# rt1060.net
KiCad netlist of a schematic drawn in EAGLE
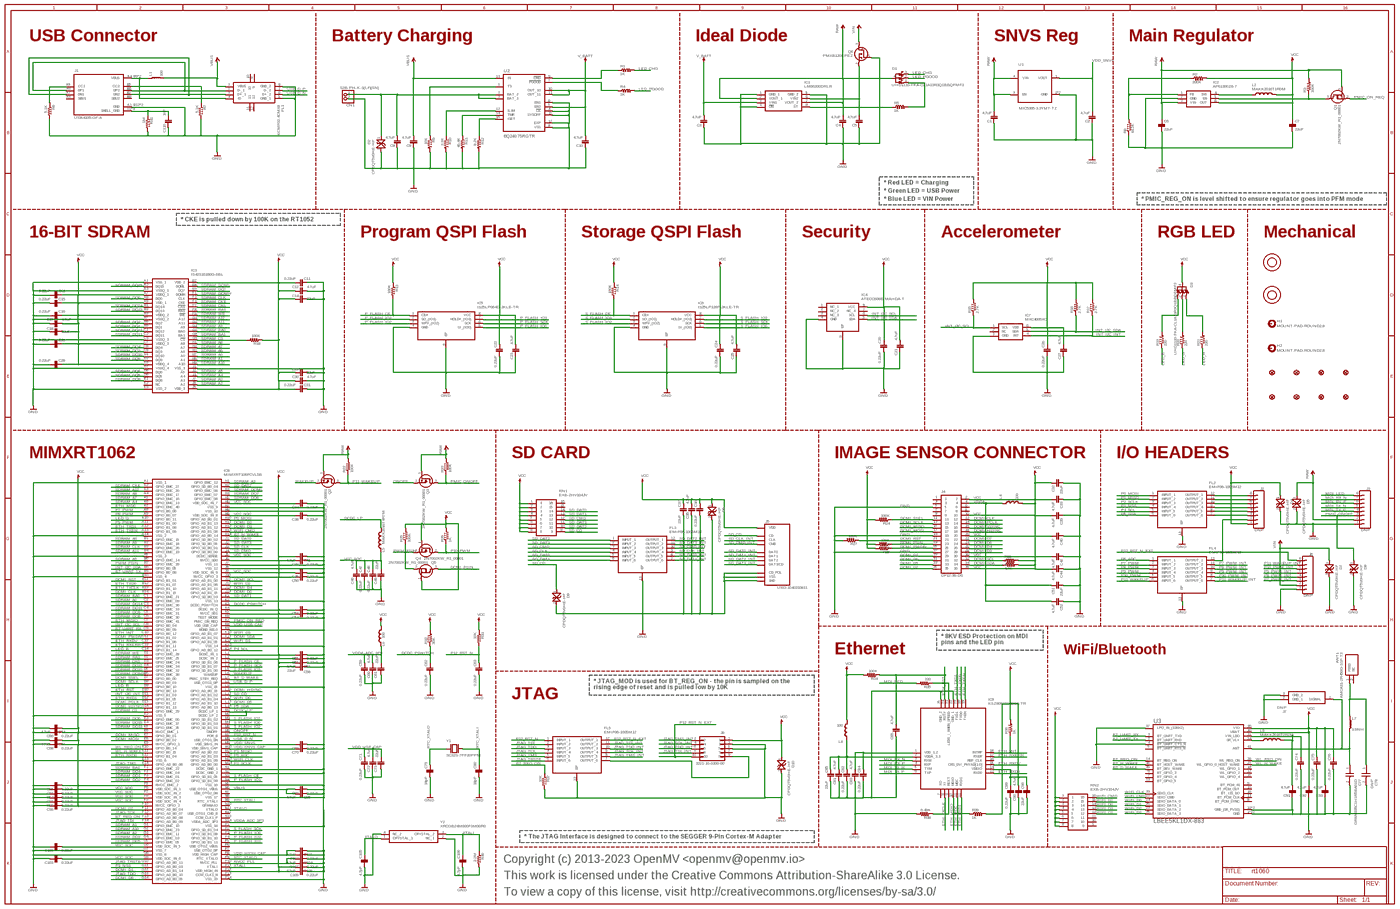
[diagram p0: schematic, sheet 1, overview]
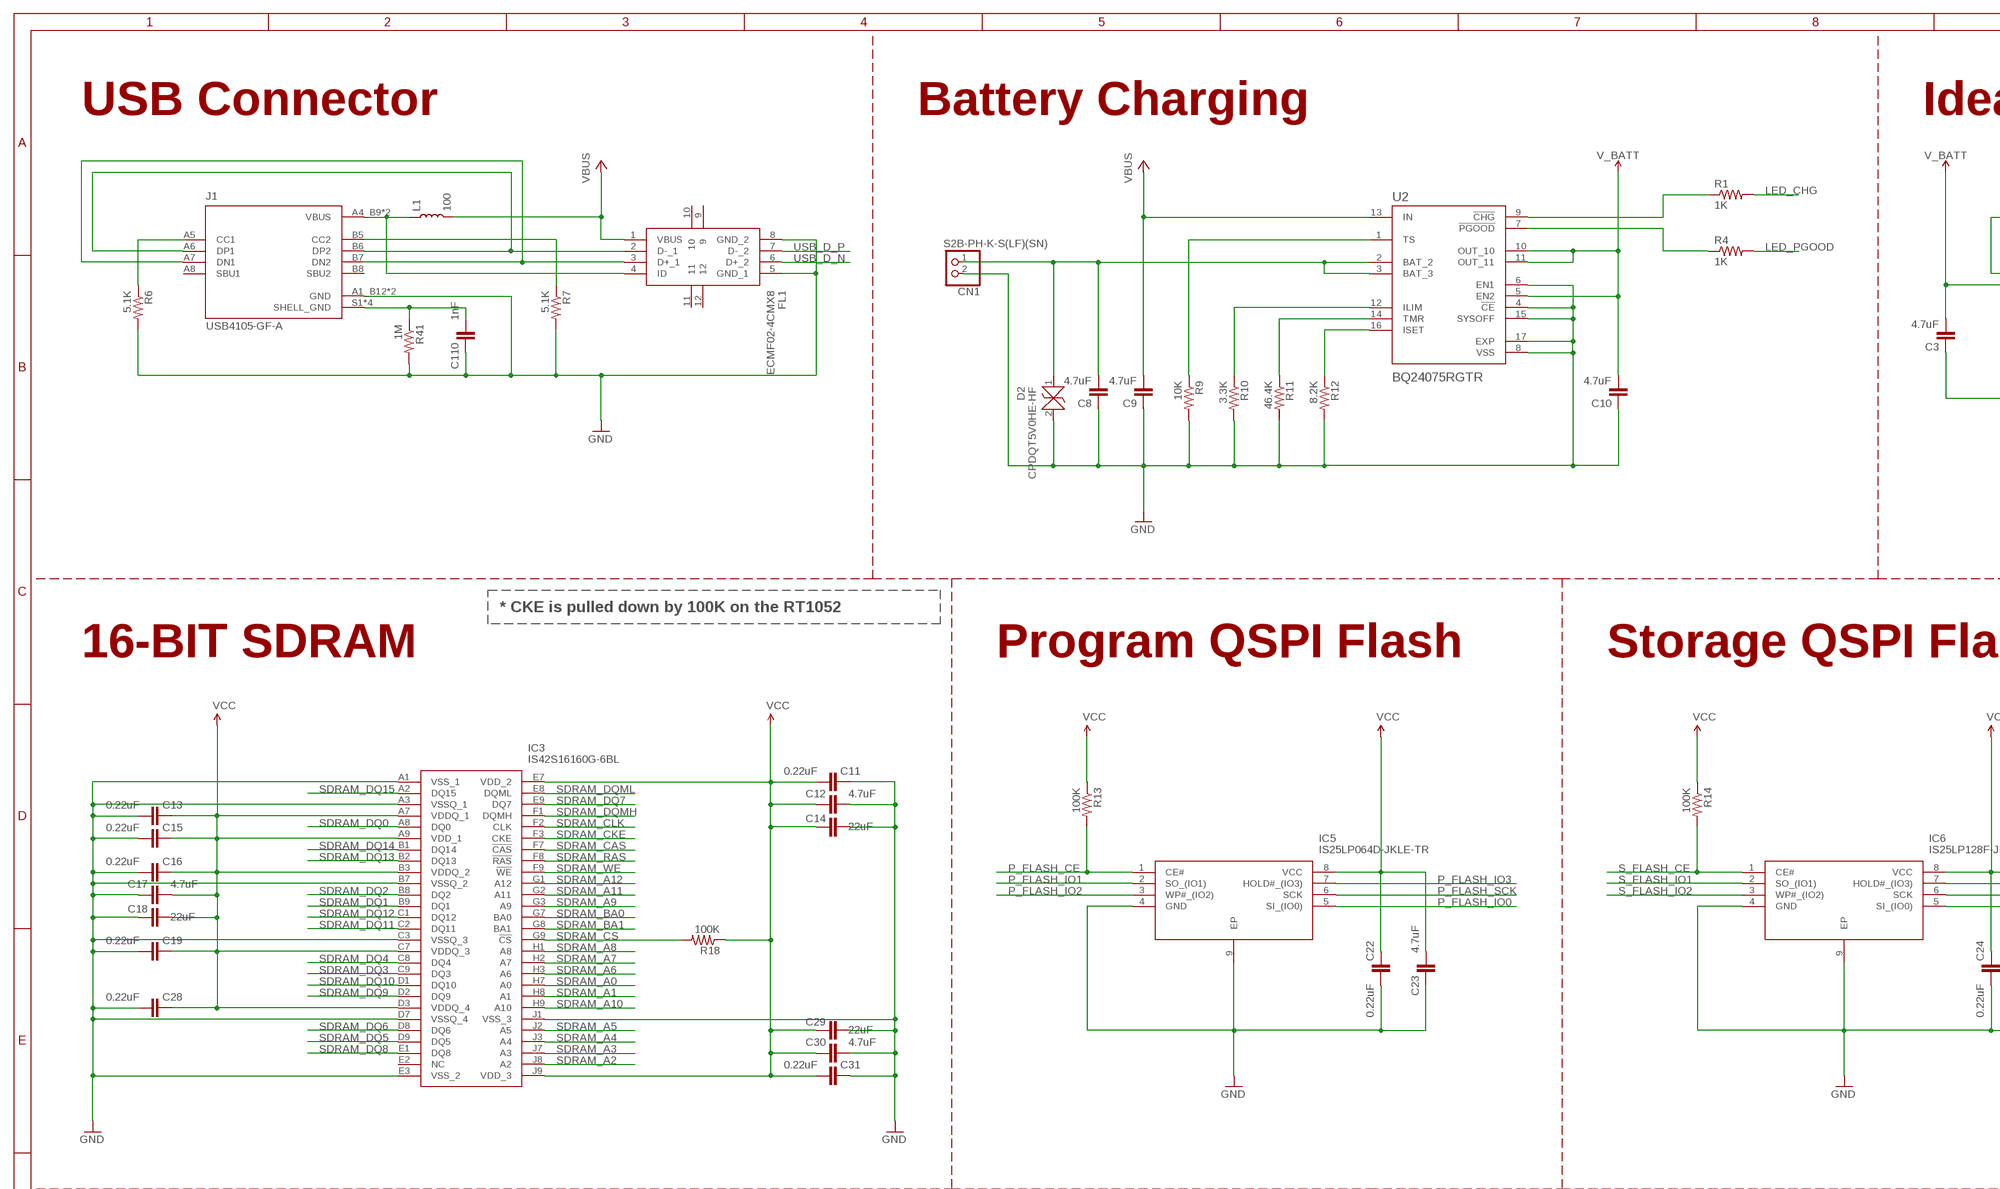
[diagram p1: schematic, sheet 1, part 1 of 4]
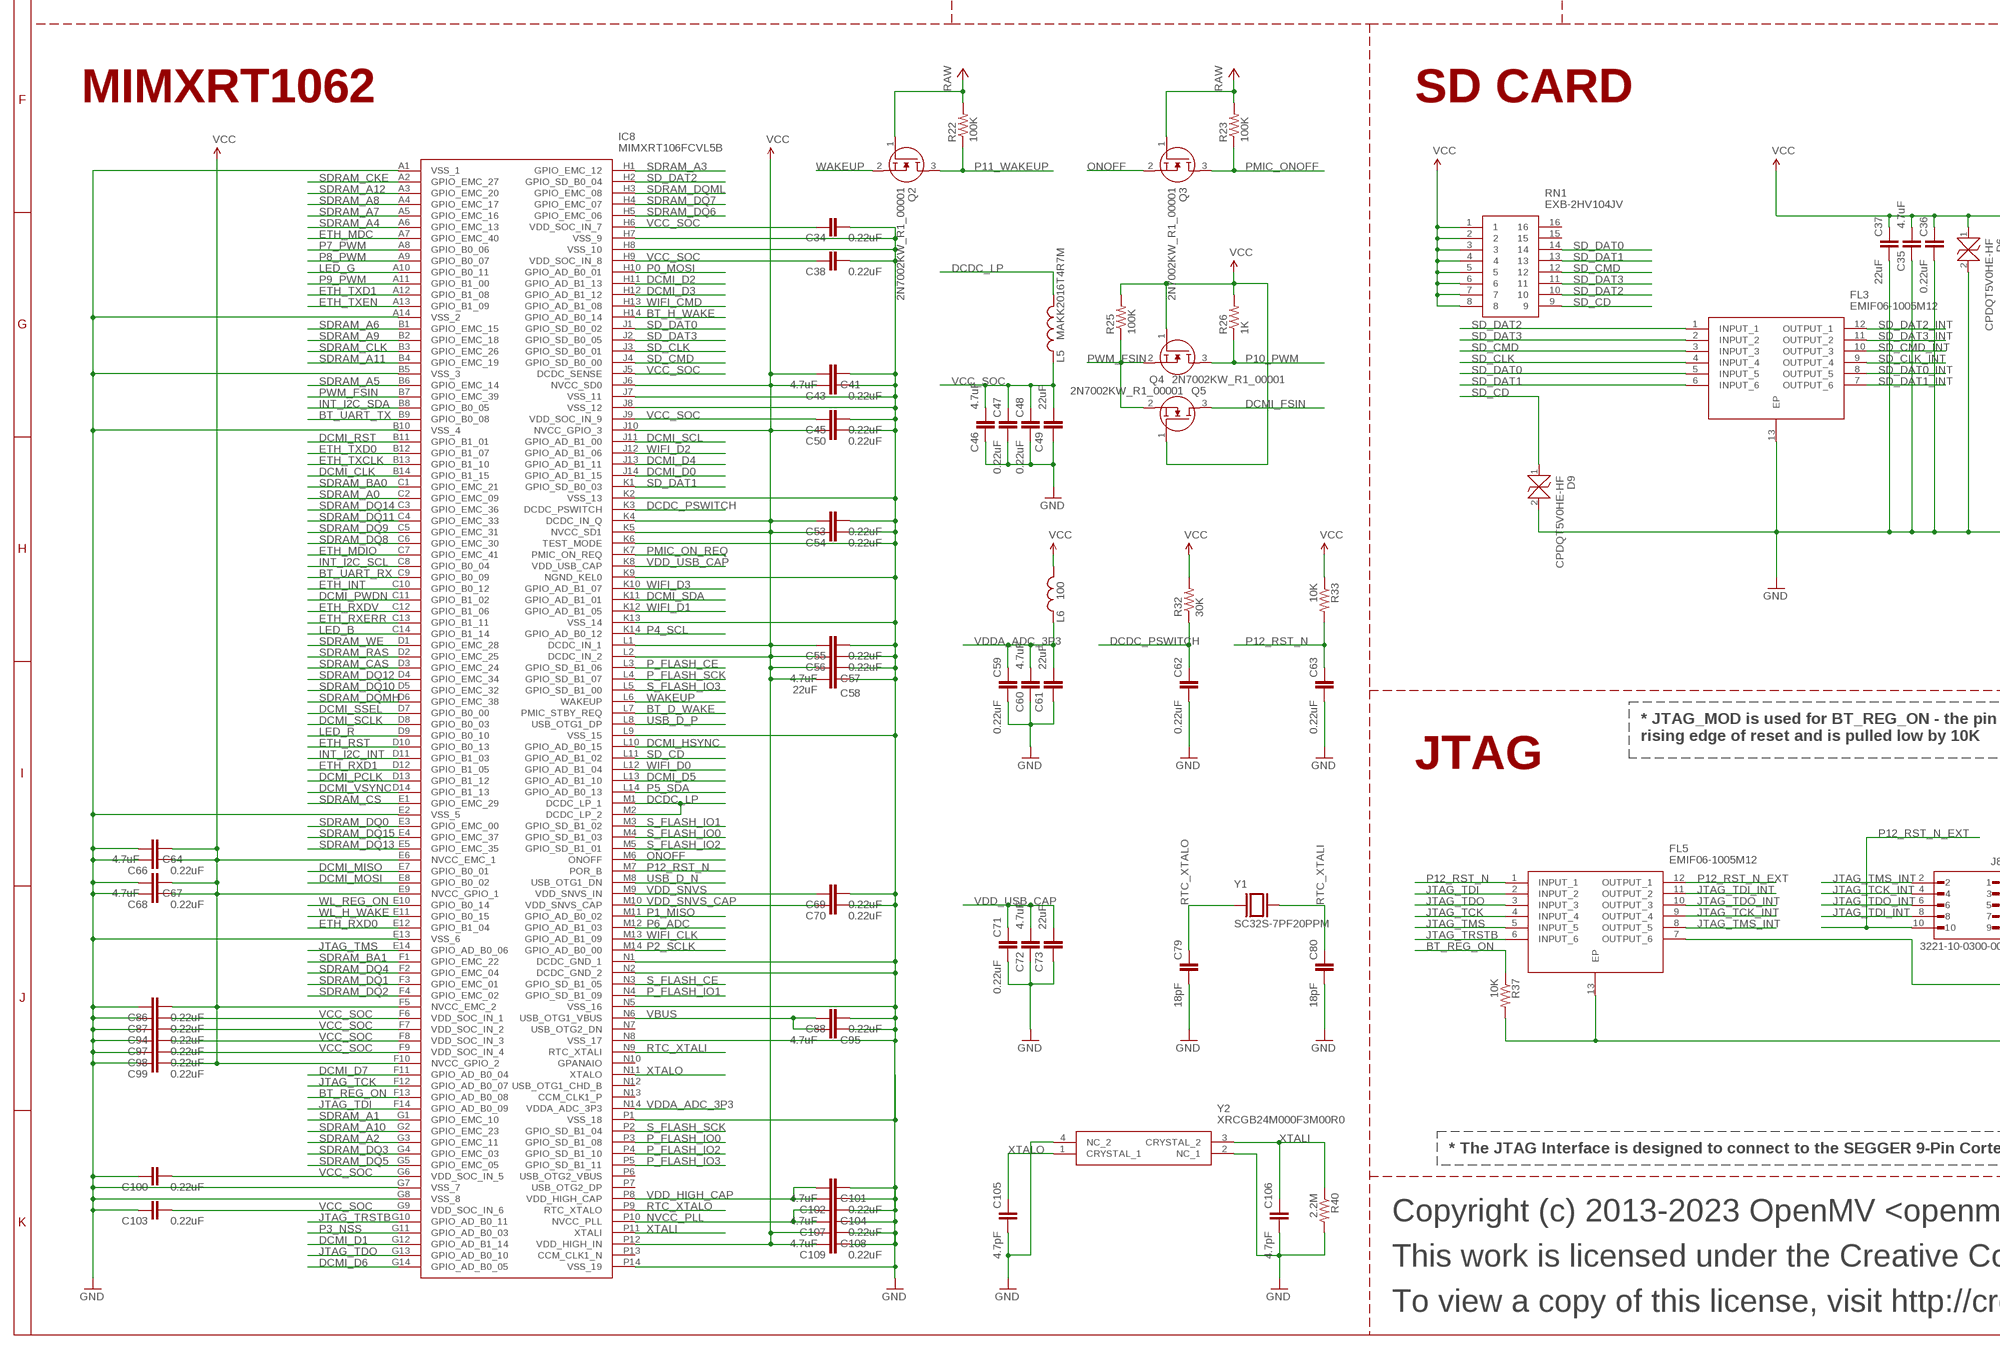
[diagram p2: schematic, sheet 1, part 2 of 4]
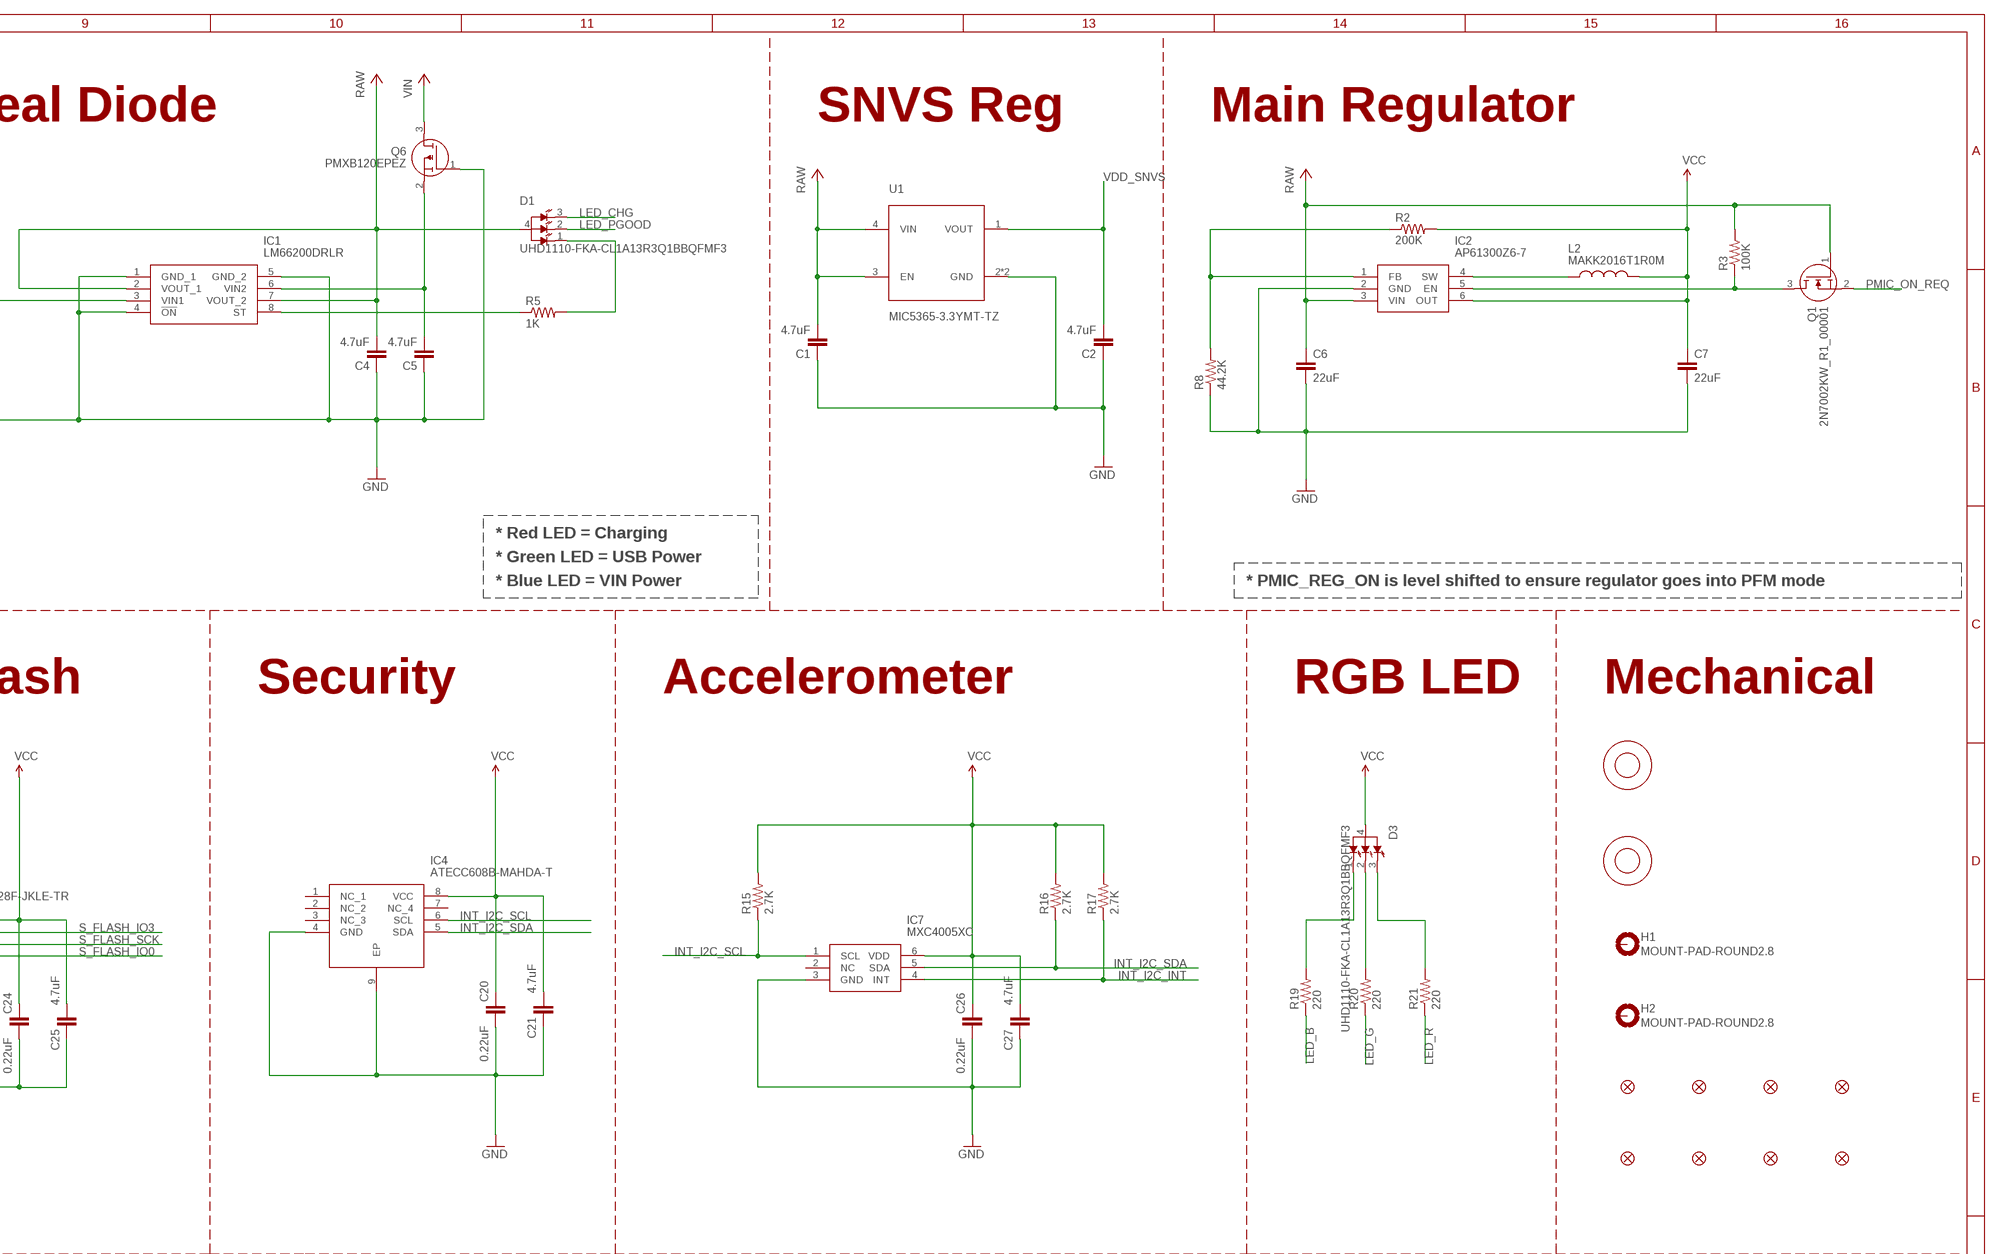
[diagram p3: schematic, sheet 1, part 3 of 4]
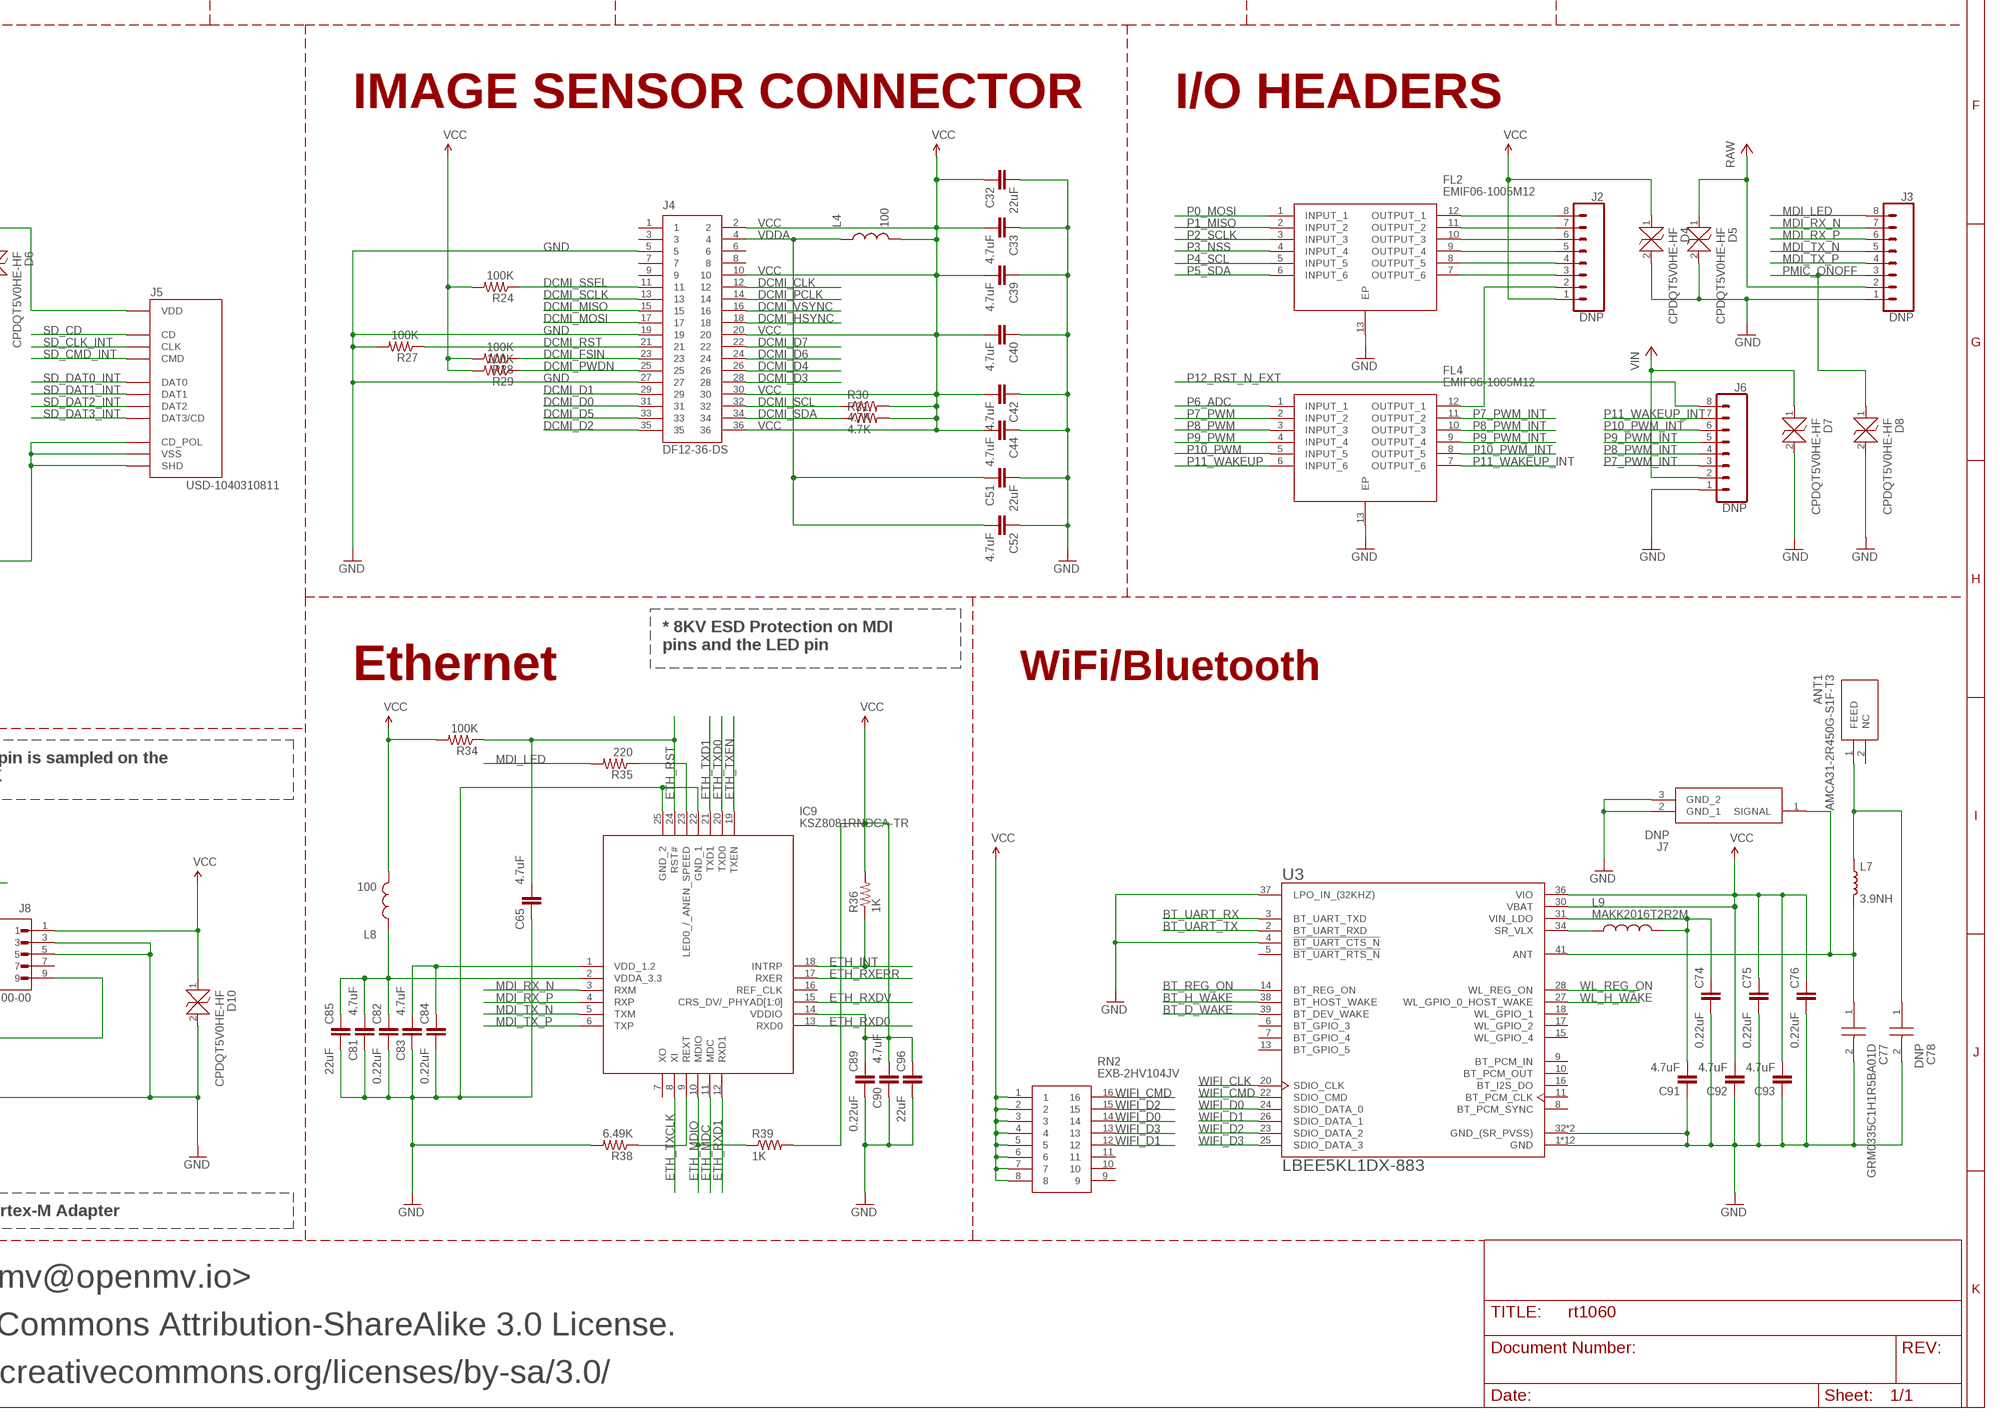
[diagram p4: schematic, sheet 1, part 4 of 4]

(export (version "E")
  (design (tool "Eeschema 10.0.6"))
  (components
    (comp (ref "ANT1")
      (value "AMCA31-2R450G-S1F-T3")
      (footprint "eagle-import:ANTC3216X140N")
      (fields (field (name "MOUSER_PART_NUMBER") "815-CA312R450GS1FT3"))
      (libsource (lib "eagle-import") (part "AMCA31-2R450G-S1F-T3"))
    )
    (comp (ref "C1")
      (value "4.7uF")
      (footprint "eagle-import:0402-CAP")
      (fields (field (name "MPN") "JMK105BBJ475MV-F"))
      (libsource (lib "eagle-import") (part "CAP0402-CAP"))
    )
    (comp (ref "C2")
      (value "4.7uF")
      (footprint "eagle-import:0402-CAP")
      (fields (field (name "MPN") "JMK105BBJ475MV-F"))
      (libsource (lib "eagle-import") (part "CAP0402-CAP"))
    )
    (comp (ref "C3")
      (value "4.7uF")
      (footprint "eagle-import:0402-CAP")
      (fields (field (name "MPN") "JMK105BBJ475MV-F"))
      (libsource (lib "eagle-import") (part "CAP0402-CAP"))
    )
    (comp (ref "C4")
      (value "4.7uF")
      (footprint "eagle-import:0402-CAP")
      (fields (field (name "MPN") "JMK105BBJ475MV-F"))
      (libsource (lib "eagle-import") (part "CAP0402-CAP"))
    )
    (comp (ref "C5")
      (value "4.7uF")
      (footprint "eagle-import:0402-CAP")
      (fields (field (name "MPN") "JMK105BBJ475MV-F"))
      (libsource (lib "eagle-import") (part "CAP0402-CAP"))
    )
    (comp (ref "C6")
      (value "22uF")
      (footprint "eagle-import:0805")
      (fields (field (name "MPN") "CL21A226MQQNNNE"))
      (libsource (lib "eagle-import") (part "22UF-0805-6.3V-20%"))
    )
    (comp (ref "C7")
      (value "22uF")
      (footprint "eagle-import:0805")
      (fields (field (name "MPN") "CL21A226MQQNNNE"))
      (libsource (lib "eagle-import") (part "22UF-0805-6.3V-20%"))
    )
    (comp (ref "C8")
      (value "4.7uF")
      (footprint "eagle-import:0402-CAP")
      (fields (field (name "MPN") "JMK105BBJ475MV-F"))
      (libsource (lib "eagle-import") (part "CAP0402-CAP"))
    )
    (comp (ref "C9")
      (value "4.7uF")
      (footprint "eagle-import:0402-CAP")
      (fields (field (name "MPN") "JMK105BBJ475MV-F"))
      (libsource (lib "eagle-import") (part "CAP0402-CAP"))
    )
    (comp (ref "C10")
      (value "4.7uF")
      (footprint "eagle-import:0402-CAP")
      (fields (field (name "MPN") "JMK105BBJ475MV-F"))
      (libsource (lib "eagle-import") (part "CAP0402-CAP"))
    )
    (comp (ref "C11")
      (value "0.22uF")
      (footprint "eagle-import:C0201")
      (fields (field (name "MPN") "GRM033R60J224ME15D"))
      (libsource (lib "eagle-import") (part "C-EUC0201"))
    )
    (comp (ref "C12")
      (value "4.7uF")
      (footprint "eagle-import:0402-CAP")
      (fields (field (name "MPN") "JMK105BBJ475MV-F"))
      (libsource (lib "eagle-import") (part "CAP0402-CAP"))
    )
    (comp (ref "C13")
      (value "0.22uF")
      (footprint "eagle-import:C0201")
      (fields (field (name "MPN") "GRM033R60J224ME15D"))
      (libsource (lib "eagle-import") (part "C-EUC0201"))
    )
    (comp (ref "C14")
      (value "22uF")
      (footprint "eagle-import:0805")
      (fields (field (name "MPN") "CL21A226MQQNNNE"))
      (libsource (lib "eagle-import") (part "22UF-0805-6.3V-20%"))
    )
    (comp (ref "C15")
      (value "0.22uF")
      (footprint "eagle-import:C0201")
      (fields (field (name "MPN") "GRM033R60J224ME15D"))
      (libsource (lib "eagle-import") (part "C-EUC0201"))
    )
    (comp (ref "C16")
      (value "0.22uF")
      (footprint "eagle-import:C0201")
      (fields (field (name "MPN") "GRM033R60J224ME15D"))
      (libsource (lib "eagle-import") (part "C-EUC0201"))
    )
    (comp (ref "C17")
      (value "4.7uF")
      (footprint "eagle-import:0402-CAP")
      (fields (field (name "MPN") "JMK105BBJ475MV-F"))
      (libsource (lib "eagle-import") (part "CAP0402-CAP"))
    )
    (comp (ref "C18")
      (value "22uF")
      (footprint "eagle-import:0805")
      (fields (field (name "MPN") "CL21A226MQQNNNE"))
      (libsource (lib "eagle-import") (part "22UF-0805-6.3V-20%"))
    )
    (comp (ref "C19")
      (value "0.22uF")
      (footprint "eagle-import:C0201")
      (fields (field (name "MPN") "GRM033R60J224ME15D"))
      (libsource (lib "eagle-import") (part "C-EUC0201"))
    )
    (comp (ref "C20")
      (value "0.22uF")
      (footprint "eagle-import:C0201")
      (fields (field (name "MPN") "GRM033R60J224ME15D"))
      (libsource (lib "eagle-import") (part "C-EUC0201"))
    )
    (comp (ref "C21")
      (value "4.7uF")
      (footprint "eagle-import:0402-CAP")
      (fields (field (name "MPN") "JMK105BBJ475MV-F"))
      (libsource (lib "eagle-import") (part "CAP0402-CAP"))
    )
    (comp (ref "C22")
      (value "0.22uF")
      (footprint "eagle-import:C0201")
      (fields (field (name "MPN") "GRM033R60J224ME15D"))
      (libsource (lib "eagle-import") (part "C-EUC0201"))
    )
    (comp (ref "C23")
      (value "4.7uF")
      (footprint "eagle-import:0402-CAP")
      (fields (field (name "MPN") "JMK105BBJ475MV-F"))
      (libsource (lib "eagle-import") (part "CAP0402-CAP"))
    )
    (comp (ref "C24")
      (value "0.22uF")
      (footprint "eagle-import:C0201")
      (fields (field (name "MPN") "GRM033R60J224ME15D"))
      (libsource (lib "eagle-import") (part "C-EUC0201"))
    )
    (comp (ref "C25")
      (value "4.7uF")
      (footprint "eagle-import:0402-CAP")
      (fields (field (name "MPN") "JMK105BBJ475MV-F"))
      (libsource (lib "eagle-import") (part "CAP0402-CAP"))
    )
    (comp (ref "C26")
      (value "0.22uF")
      (footprint "eagle-import:C0201")
      (fields (field (name "MPN") "GRM033R60J224ME15D"))
      (libsource (lib "eagle-import") (part "C-EUC0201"))
    )
    (comp (ref "C27")
      (value "4.7uF")
      (footprint "eagle-import:0402-CAP")
      (fields (field (name "MPN") "JMK105BBJ475MV-F"))
      (libsource (lib "eagle-import") (part "CAP0402-CAP"))
    )
    (comp (ref "C28")
      (value "0.22uF")
      (footprint "eagle-import:C0201")
      (fields (field (name "MPN") "GRM033R60J224ME15D"))
      (libsource (lib "eagle-import") (part "C-EUC0201"))
    )
    (comp (ref "C29")
      (value "22uF")
      (footprint "eagle-import:0805")
      (fields (field (name "MPN") "CL21A226MQQNNNE"))
      (libsource (lib "eagle-import") (part "22UF-0805-6.3V-20%"))
    )
    (comp (ref "C30")
      (value "4.7uF")
      (footprint "eagle-import:0402-CAP")
      (fields (field (name "MPN") "JMK105BBJ475MV-F"))
      (libsource (lib "eagle-import") (part "CAP0402-CAP"))
    )
    (comp (ref "C31")
      (value "0.22uF")
      (footprint "eagle-import:C0201")
      (fields (field (name "MPN") "GRM033R60J224ME15D"))
      (libsource (lib "eagle-import") (part "C-EUC0201"))
    )
    (comp (ref "C32")
      (value "22uF")
      (footprint "eagle-import:0805")
      (fields (field (name "MPN") "CL21A226MQQNNNE"))
      (libsource (lib "eagle-import") (part "22UF-0805-6.3V-20%"))
    )
    (comp (ref "C33")
      (value "4.7uF")
      (footprint "eagle-import:0402-CAP")
      (fields (field (name "MPN") "JMK105BBJ475MV-F"))
      (libsource (lib "eagle-import") (part "CAP0402-CAP"))
    )
    (comp (ref "C34")
      (value "0.22uF")
      (footprint "eagle-import:C0201")
      (fields (field (name "MPN") "GRM033R60J224ME15D"))
      (libsource (lib "eagle-import") (part "C-EUC0201"))
    )
    (comp (ref "C35")
      (value "4.7uF")
      (footprint "eagle-import:0402-CAP")
      (fields (field (name "MPN") "JMK105BBJ475MV-F"))
      (libsource (lib "eagle-import") (part "CAP0402-CAP"))
    )
    (comp (ref "C36")
      (value "0.22uF")
      (footprint "eagle-import:C0201")
      (fields (field (name "MPN") "GRM033R60J224ME15D"))
      (libsource (lib "eagle-import") (part "C-EUC0201"))
    )
    (comp (ref "C37")
      (value "22uF")
      (footprint "eagle-import:0805")
      (fields (field (name "MPN") "CL21A226MQQNNNE"))
      (libsource (lib "eagle-import") (part "22UF-0805-6.3V-20%"))
    )
    (comp (ref "C38")
      (value "0.22uF")
      (footprint "eagle-import:C0201")
      (fields (field (name "MPN") "GRM033R60J224ME15D"))
      (libsource (lib "eagle-import") (part "C-EUC0201"))
    )
    (comp (ref "C39")
      (value "4.7uF")
      (footprint "eagle-import:0402-CAP")
      (fields (field (name "MPN") "JMK105BBJ475MV-F"))
      (libsource (lib "eagle-import") (part "CAP0402-CAP"))
    )
    (comp (ref "C40")
      (value "4.7uF")
      (footprint "eagle-import:0402-CAP")
      (fields (field (name "MPN") "JMK105BBJ475MV-F"))
      (libsource (lib "eagle-import") (part "CAP0402-CAP"))
    )
    (comp (ref "C41")
      (value "4.7uF")
      (footprint "eagle-import:0402-CAP")
      (fields (field (name "MPN") "JMK105BBJ475MV-F"))
      (libsource (lib "eagle-import") (part "CAP0402-CAP"))
    )
    (comp (ref "C42")
      (value "4.7uF")
      (footprint "eagle-import:0402-CAP")
      (fields (field (name "MPN") "JMK105BBJ475MV-F"))
      (libsource (lib "eagle-import") (part "CAP0402-CAP"))
    )
    (comp (ref "C43")
      (value "0.22uF")
      (footprint "eagle-import:C0201")
      (fields (field (name "MPN") "GRM033R60J224ME15D"))
      (libsource (lib "eagle-import") (part "C-EUC0201"))
    )
    (comp (ref "C44")
      (value "4.7uF")
      (footprint "eagle-import:0402-CAP")
      (fields (field (name "MPN") "JMK105BBJ475MV-F"))
      (libsource (lib "eagle-import") (part "CAP0402-CAP"))
    )
    (comp (ref "C45")
      (value "0.22uF")
      (footprint "eagle-import:C0201")
      (fields (field (name "MPN") "GRM033R60J224ME15D"))
      (libsource (lib "eagle-import") (part "C-EUC0201"))
    )
    (comp (ref "C46")
      (value "4.7uF")
      (footprint "eagle-import:0402-CAP")
      (fields (field (name "MPN") "JMK105BBJ475MV-F"))
      (libsource (lib "eagle-import") (part "CAP0402-CAP"))
    )
    (comp (ref "C47")
      (value "0.22uF")
      (footprint "eagle-import:C0201")
      (fields (field (name "MPN") "GRM033R60J224ME15D"))
      (libsource (lib "eagle-import") (part "C-EUC0201"))
    )
    (comp (ref "C48")
      (value "0.22uF")
      (footprint "eagle-import:C0201")
      (fields (field (name "MPN") "GRM033R60J224ME15D"))
      (libsource (lib "eagle-import") (part "C-EUC0201"))
    )
    (comp (ref "C49")
      (value "22uF")
      (footprint "eagle-import:0805")
      (fields (field (name "MPN") "CL21A226MQQNNNE"))
      (libsource (lib "eagle-import") (part "22UF-0805-6.3V-20%"))
    )
    (comp (ref "C50")
      (value "0.22uF")
      (footprint "eagle-import:C0201")
      (fields (field (name "MPN") "GRM033R60J224ME15D"))
      (libsource (lib "eagle-import") (part "C-EUC0201"))
    )
    (comp (ref "C51")
      (value "22uF")
      (footprint "eagle-import:0805")
      (fields (field (name "MPN") "CL21A226MQQNNNE"))
      (libsource (lib "eagle-import") (part "22UF-0805-6.3V-20%"))
    )
    (comp (ref "C52")
      (value "4.7uF")
      (footprint "eagle-import:0402-CAP")
      (fields (field (name "MPN") "JMK105BBJ475MV-F"))
      (libsource (lib "eagle-import") (part "CAP0402-CAP"))
    )
    (comp (ref "C53")
      (value "0.22uF")
      (footprint "eagle-import:C0201")
      (fields (field (name "MPN") "GRM033R60J224ME15D"))
      (libsource (lib "eagle-import") (part "C-EUC0201"))
    )
    (comp (ref "C54")
      (value "0.22uF")
      (footprint "eagle-import:C0201")
      (fields (field (name "MPN") "GRM033R60J224ME15D"))
      (libsource (lib "eagle-import") (part "C-EUC0201"))
    )
    (comp (ref "C55")
      (value "0.22uF")
      (footprint "eagle-import:C0201")
      (fields (field (name "MPN") "GRM033R60J224ME15D"))
      (libsource (lib "eagle-import") (part "C-EUC0201"))
    )
    (comp (ref "C56")
      (value "0.22uF")
      (footprint "eagle-import:C0201")
      (fields (field (name "MPN") "GRM033R60J224ME15D"))
      (libsource (lib "eagle-import") (part "C-EUC0201"))
    )
    (comp (ref "C57")
      (value "4.7uF")
      (footprint "eagle-import:0402-CAP")
      (fields (field (name "MPN") "JMK105BBJ475MV-F"))
      (libsource (lib "eagle-import") (part "CAP0402-CAP"))
    )
    (comp (ref "C58")
      (value "22uF")
      (footprint "eagle-import:0805")
      (fields (field (name "MPN") "CL21A226MQQNNNE"))
      (libsource (lib "eagle-import") (part "22UF-0805-6.3V-20%"))
    )
    (comp (ref "C59")
      (value "0.22uF")
      (footprint "eagle-import:C0201")
      (fields (field (name "MPN") "GRM033R60J224ME15D"))
      (libsource (lib "eagle-import") (part "C-EUC0201"))
    )
    (comp (ref "C60")
      (value "4.7uF")
      (footprint "eagle-import:0402-CAP")
      (fields (field (name "MPN") "JMK105BBJ475MV-F"))
      (libsource (lib "eagle-import") (part "CAP0402-CAP"))
    )
    (comp (ref "C61")
      (value "22uF")
      (footprint "eagle-import:0805")
      (fields (field (name "MPN") "CL21A226MQQNNNE"))
      (libsource (lib "eagle-import") (part "22UF-0805-6.3V-20%"))
    )
    (comp (ref "C62")
      (value "0.22uF")
      (footprint "eagle-import:C0201")
      (fields (field (name "MPN") "GRM033R60J224ME15D"))
      (libsource (lib "eagle-import") (part "C-EUC0201"))
    )
    (comp (ref "C63")
      (value "0.22uF")
      (footprint "eagle-import:C0201")
      (fields (field (name "MPN") "GRM033R60J224ME15D"))
      (libsource (lib "eagle-import") (part "C-EUC0201"))
    )
    (comp (ref "C64")
      (value "4.7uF")
      (footprint "eagle-import:0402-CAP")
      (fields (field (name "MPN") "JMK105BBJ475MV-F"))
      (libsource (lib "eagle-import") (part "CAP0402-CAP"))
    )
    (comp (ref "C65")
      (value "4.7uF")
      (footprint "eagle-import:0402-CAP")
      (fields (field (name "MPN") "JMK105BBJ475MV-F"))
      (libsource (lib "eagle-import") (part "CAP0402-CAP"))
    )
    (comp (ref "C66")
      (value "0.22uF")
      (footprint "eagle-import:C0201")
      (fields (field (name "MPN") "GRM033R60J224ME15D"))
      (libsource (lib "eagle-import") (part "C-EUC0201"))
    )
    (comp (ref "C67")
      (value "4.7uF")
      (footprint "eagle-import:0402-CAP")
      (fields (field (name "MPN") "JMK105BBJ475MV-F"))
      (libsource (lib "eagle-import") (part "CAP0402-CAP"))
    )
    (comp (ref "C68")
      (value "0.22uF")
      (footprint "eagle-import:C0201")
      (fields (field (name "MPN") "GRM033R60J224ME15D"))
      (libsource (lib "eagle-import") (part "C-EUC0201"))
    )
    (comp (ref "C69")
      (value "0.22uF")
      (footprint "eagle-import:C0201")
      (fields (field (name "MPN") "GRM033R60J224ME15D"))
      (libsource (lib "eagle-import") (part "C-EUC0201"))
    )
    (comp (ref "C70")
      (value "0.22uF")
      (footprint "eagle-import:C0201")
      (fields (field (name "MPN") "GRM033R60J224ME15D"))
      (libsource (lib "eagle-import") (part "C-EUC0201"))
    )
    (comp (ref "C71")
      (value "0.22uF")
      (footprint "eagle-import:C0201")
      (fields (field (name "MPN") "GRM033R60J224ME15D"))
      (libsource (lib "eagle-import") (part "C-EUC0201"))
    )
    (comp (ref "C72")
      (value "4.7uF")
      (footprint "eagle-import:0402-CAP")
      (fields (field (name "MPN") "JMK105BBJ475MV-F"))
      (libsource (lib "eagle-import") (part "CAP0402-CAP"))
    )
    (comp (ref "C73")
      (value "22uF")
      (footprint "eagle-import:0805")
      (fields (field (name "MPN") "CL21A226MQQNNNE"))
      (libsource (lib "eagle-import") (part "22UF-0805-6.3V-20%"))
    )
    (comp (ref "C74")
      (value "0.22uF")
      (footprint "eagle-import:C0201")
      (fields (field (name "MPN") "GRM033R60J224ME15D"))
      (libsource (lib "eagle-import") (part "C-EUC0201"))
    )
    (comp (ref "C75")
      (value "0.22uF")
      (footprint "eagle-import:C0201")
      (fields (field (name "MPN") "GRM033R60J224ME15D"))
      (libsource (lib "eagle-import") (part "C-EUC0201"))
    )
    (comp (ref "C76")
      (value "0.22uF")
      (footprint "eagle-import:C0201")
      (fields (field (name "MPN") "GRM033R60J224ME15D"))
      (libsource (lib "eagle-import") (part "C-EUC0201"))
    )
    (comp (ref "C77")
      (value "GRM0335C1H1R5BA01D")
      (footprint "eagle-import:CAPC0603X33N")
      (fields (field (name "MOUSER_PART_NUMBER") "81-GRM0335C1H1R5BA1D"))
      (libsource (lib "eagle-import") (part "GRM0335C1H1R5BA01D"))
    )
    (comp (ref "C78")
      (value "DNP")
      (footprint "eagle-import:CAPC0603X33N")
      (fields
        (field (name "MANUFACTURER_PART_NUMBER") "GRM0335C1H1R5BA01D")
        (field (name "MOUSER_PART_NUMBER") "81-GRM0335C1H1R5BA1D")
      )
      (libsource (lib "eagle-import") (part "GRM0335C1H1R5BA01D"))
    )
    (comp (ref "C79")
      (value "18pF")
      (footprint "eagle-import:C0201")
      (fields (field (name "MPN") "GRM0335C1E180JA01D"))
      (libsource (lib "eagle-import") (part "C-EUC0201"))
    )
    (comp (ref "C80")
      (value "18pF")
      (footprint "eagle-import:C0201")
      (fields (field (name "MPN") "GRM0335C1E180JA01D"))
      (libsource (lib "eagle-import") (part "C-EUC0201"))
    )
    (comp (ref "C81")
      (value "4.7uF")
      (footprint "eagle-import:0402-CAP")
      (fields (field (name "MPN") "JMK105BBJ475MV-F"))
      (libsource (lib "eagle-import") (part "CAP0402-CAP"))
    )
    (comp (ref "C82")
      (value "0.22uF")
      (footprint "eagle-import:C0201")
      (fields (field (name "MPN") "GRM033R60J224ME15D"))
      (libsource (lib "eagle-import") (part "C-EUC0201"))
    )
    (comp (ref "C83")
      (value "4.7uF")
      (footprint "eagle-import:0402-CAP")
      (fields (field (name "MPN") "JMK105BBJ475MV-F"))
      (libsource (lib "eagle-import") (part "CAP0402-CAP"))
    )
    (comp (ref "C84")
      (value "0.22uF")
      (footprint "eagle-import:C0201")
      (fields (field (name "MPN") "GRM033R60J224ME15D"))
      (libsource (lib "eagle-import") (part "C-EUC0201"))
    )
    (comp (ref "C85")
      (value "22uF")
      (footprint "eagle-import:0805")
      (fields (field (name "MPN") "CL21A226MQQNNNE"))
      (libsource (lib "eagle-import") (part "22UF-0805-6.3V-20%"))
    )
    (comp (ref "C86")
      (value "0.22uF")
      (footprint "eagle-import:C0201")
      (fields (field (name "MPN") "GRM033R60J224ME15D"))
      (libsource (lib "eagle-import") (part "C-EUC0201"))
    )
    (comp (ref "C87")
      (value "0.22uF")
      (footprint "eagle-import:C0201")
      (fields (field (name "MPN") "GRM033R60J224ME15D"))
      (libsource (lib "eagle-import") (part "C-EUC0201"))
    )
    (comp (ref "C88")
      (value "0.22uF")
      (footprint "eagle-import:C0201")
      (fields (field (name "MPN") "GRM033R60J224ME15D"))
      (libsource (lib "eagle-import") (part "C-EUC0201"))
    )
    (comp (ref "C89")
      (value "0.22uF")
      (footprint "eagle-import:C0201")
      (fields (field (name "MPN") "GRM033R60J224ME15D"))
      (libsource (lib "eagle-import") (part "C-EUC0201"))
    )
    (comp (ref "C90")
      (value "4.7uF")
      (footprint "eagle-import:0402-CAP")
      (fields (field (name "MPN") "JMK105BBJ475MV-F"))
      (libsource (lib "eagle-import") (part "CAP0402-CAP"))
    )
    (comp (ref "C91")
      (value "4.7uF")
      (footprint "eagle-import:0402-CAP")
      (fields (field (name "MPN") "JMK105BBJ475MV-F"))
      (libsource (lib "eagle-import") (part "CAP0402-CAP"))
    )
    (comp (ref "C92")
      (value "4.7uF")
      (footprint "eagle-import:0402-CAP")
      (fields (field (name "MPN") "JMK105BBJ475MV-F"))
      (libsource (lib "eagle-import") (part "CAP0402-CAP"))
    )
    (comp (ref "C93")
      (value "4.7uF")
      (footprint "eagle-import:0402-CAP")
      (fields (field (name "MPN") "JMK105BBJ475MV-F"))
      (libsource (lib "eagle-import") (part "CAP0402-CAP"))
    )
    (comp (ref "C94")
      (value "0.22uF")
      (footprint "eagle-import:C0201")
      (fields (field (name "MPN") "GRM033R60J224ME15D"))
      (libsource (lib "eagle-import") (part "C-EUC0201"))
    )
    (comp (ref "C95")
      (value "4.7uF")
      (footprint "eagle-import:0402-CAP")
      (fields (field (name "MPN") "JMK105BBJ475MV-F"))
      (libsource (lib "eagle-import") (part "CAP0402-CAP"))
    )
    (comp (ref "C96")
      (value "22uF")
      (footprint "eagle-import:0805")
      (fields (field (name "MPN") "CL21A226MQQNNNE"))
      (libsource (lib "eagle-import") (part "22UF-0805-6.3V-20%"))
    )
    (comp (ref "C97")
      (value "0.22uF")
      (footprint "eagle-import:C0201")
      (fields (field (name "MPN") "GRM033R60J224ME15D"))
      (libsource (lib "eagle-import") (part "C-EUC0201"))
    )
    (comp (ref "C98")
      (value "0.22uF")
      (footprint "eagle-import:C0201")
      (fields (field (name "MPN") "GRM033R60J224ME15D"))
      (libsource (lib "eagle-import") (part "C-EUC0201"))
    )
    (comp (ref "C99")
      (value "0.22uF")
      (footprint "eagle-import:C0201")
      (fields (field (name "MPN") "GRM033R60J224ME15D"))
      (libsource (lib "eagle-import") (part "C-EUC0201"))
    )
    (comp (ref "C100")
      (value "0.22uF")
      (footprint "eagle-import:C0201")
      (fields (field (name "MPN") "GRM033R60J224ME15D"))
      (libsource (lib "eagle-import") (part "C-EUC0201"))
    )
    (comp (ref "C101")
      (value "4.7uF")
      (footprint "eagle-import:0402-CAP")
      (fields (field (name "MPN") "JMK105BBJ475MV-F"))
      (libsource (lib "eagle-import") (part "CAP0402-CAP"))
    )
    (comp (ref "C102")
      (value "0.22uF")
      (footprint "eagle-import:C0201")
      (fields (field (name "MPN") "GRM033R60J224ME15D"))
      (libsource (lib "eagle-import") (part "C-EUC0201"))
    )
    (comp (ref "C103")
      (value "0.22uF")
      (footprint "eagle-import:C0201")
      (fields (field (name "MPN") "GRM033R60J224ME15D"))
      (libsource (lib "eagle-import") (part "C-EUC0201"))
    )
    (comp (ref "C104")
      (value "4.7uF")
      (footprint "eagle-import:0402-CAP")
      (fields (field (name "MPN") "JMK105BBJ475MV-F"))
      (libsource (lib "eagle-import") (part "CAP0402-CAP"))
    )
    (comp (ref "C105")
      (value "4.7pF")
      (footprint "eagle-import:C0201")
      (fields (field (name "MPN") "GRM0335C1E4R7CA01D"))
      (libsource (lib "eagle-import") (part "C-EUC0201"))
    )
    (comp (ref "C106")
      (value "4.7pF")
      (footprint "eagle-import:C0201")
      (fields (field (name "MPN") "GRM0335C1E4R7CA01D"))
      (libsource (lib "eagle-import") (part "C-EUC0201"))
    )
    (comp (ref "C107")
      (value "0.22uF")
      (footprint "eagle-import:C0201")
      (fields (field (name "MPN") "GRM033R60J224ME15D"))
      (libsource (lib "eagle-import") (part "C-EUC0201"))
    )
    (comp (ref "C108")
      (value "4.7uF")
      (footprint "eagle-import:0402-CAP")
      (fields (field (name "MPN") "JMK105BBJ475MV-F"))
      (libsource (lib "eagle-import") (part "CAP0402-CAP"))
    )
    (comp (ref "C109")
      (value "0.22uF")
      (footprint "eagle-import:C0201")
      (fields (field (name "MPN") "GRM033R60J224ME15D"))
      (libsource (lib "eagle-import") (part "C-EUC0201"))
    )
    (comp (ref "C110")
      (value "1nF")
      (footprint "eagle-import:0402-CAP")
      (fields (field (name "MPN") "VJ0402Y102JXACW1BC"))
      (libsource (lib "eagle-import") (part "CAP0402-CAP"))
    )
    (comp (ref "CN1")
      (value "S2B-PH-K-S(LF)(SN)")
      (footprint "eagle-import:JST-PH-2-THM-RA")
      (libsource (lib "eagle-import") (part "JST_2PIN-THM-RA"))
    )
    (comp (ref "D1")
      (value "UHD1110-FKA-CL1A13R3Q1BBQFMF3")
      (footprint "eagle-import:LED_UHD1110-FKA-CL1A13R3Q1BBQFMF3")
      (fields (field (name "MF") "Cree Inc.") (field (name "MPN") "UHD1110-FKA-CL1A13r3q1BBQFMF3"))
      (libsource (lib "eagle-import") (part "UHD1110-FKA-CL1A13R3Q1BBQFMF3"))
    )
    (comp (ref "D2")
      (value "CPDQT5V0HE-HF")
      (footprint "eagle-import:CPDQT5V0HEHF")
      (libsource (lib "eagle-import") (part "CPDQT5V0HE-HF"))
    )
    (comp (ref "D3")
      (value "UHD1110-FKA-CL1A13R3Q1BBQFMF3")
      (footprint "eagle-import:LED_UHD1110-FKA-CL1A13R3Q1BBQFMF3")
      (fields (field (name "MF") "Cree Inc.") (field (name "MPN") "UHD1110-FKA-CL1A13r3q1BBQFMF3"))
      (libsource (lib "eagle-import") (part "UHD1110-FKA-CL1A13R3Q1BBQFMF3"))
    )
    (comp (ref "D4")
      (value "CPDQT5V0HE-HF")
      (footprint "eagle-import:CPDQT5V0HEHF")
      (libsource (lib "eagle-import") (part "CPDQT5V0HE-HF"))
    )
    (comp (ref "D5")
      (value "CPDQT5V0HE-HF")
      (footprint "eagle-import:CPDQT5V0HEHF")
      (libsource (lib "eagle-import") (part "CPDQT5V0HE-HF"))
    )
    (comp (ref "D6")
      (value "CPDQT5V0HE-HF")
      (footprint "eagle-import:CPDQT5V0HEHF")
      (libsource (lib "eagle-import") (part "CPDQT5V0HE-HF"))
    )
    (comp (ref "D7")
      (value "CPDQT5V0HE-HF")
      (footprint "eagle-import:CPDQT5V0HEHF")
      (libsource (lib "eagle-import") (part "CPDQT5V0HE-HF"))
    )
    (comp (ref "D8")
      (value "CPDQT5V0HE-HF")
      (footprint "eagle-import:CPDQT5V0HEHF")
      (libsource (lib "eagle-import") (part "CPDQT5V0HE-HF"))
    )
    (comp (ref "D9")
      (value "CPDQT5V0HE-HF")
      (footprint "eagle-import:CPDQT5V0HEHF")
      (libsource (lib "eagle-import") (part "CPDQT5V0HE-HF"))
    )
    (comp (ref "D10")
      (value "CPDQT5V0HE-HF")
      (footprint "eagle-import:CPDQT5V0HEHF")
      (libsource (lib "eagle-import") (part "CPDQT5V0HE-HF"))
    )
    (comp (ref "FD1")
      (value "FIDUCIAL1X2")
      (footprint "eagle-import:FIDUCIAL-1X2")
      (libsource (lib "eagle-import") (part "FIDUCIAL1X2"))
    )
    (comp (ref "FD2")
      (value "FIDUCIAL1X2")
      (footprint "eagle-import:FIDUCIAL-1X2")
      (libsource (lib "eagle-import") (part "FIDUCIAL1X2"))
    )
    (comp (ref "FD3")
      (value "FIDUCIAL1X2")
      (footprint "eagle-import:FIDUCIAL-1X2")
      (libsource (lib "eagle-import") (part "FIDUCIAL1X2"))
    )
    (comp (ref "FD4")
      (value "FIDUCIAL1X2")
      (footprint "eagle-import:FIDUCIAL-1X2")
      (libsource (lib "eagle-import") (part "FIDUCIAL1X2"))
    )
    (comp (ref "FD5")
      (value "FIDUCIAL1X2")
      (footprint "eagle-import:FIDUCIAL-1X2")
      (libsource (lib "eagle-import") (part "FIDUCIAL1X2"))
    )
    (comp (ref "FD6")
      (value "FIDUCIAL1X2")
      (footprint "eagle-import:FIDUCIAL-1X2")
      (libsource (lib "eagle-import") (part "FIDUCIAL1X2"))
    )
    (comp (ref "FD7")
      (value "FIDUCIAL1X2")
      (footprint "eagle-import:FIDUCIAL-1X2")
      (libsource (lib "eagle-import") (part "FIDUCIAL1X2"))
    )
    (comp (ref "FD8")
      (value "FIDUCIAL1X2")
      (footprint "eagle-import:FIDUCIAL-1X2")
      (libsource (lib "eagle-import") (part "FIDUCIAL1X2"))
    )
    (comp (ref "FL1")
      (value "ECMF02-4CMX8")
      (footprint "eagle-import:ECMF024CMX8")
      (fields (field (name "MOUSER_PART_NUMBER") "511-ECMF02-4CMX8"))
      (libsource (lib "eagle-import") (part "ECMF02-4CMX8"))
    )
    (comp (ref "FL2")
      (value "EMIF06-1005M12")
      (footprint "eagle-import:SON40P150X250X65-13N")
      (fields (field (name "MOUSER_PART_NUMBER") "511-EMIF06-1005M12"))
      (libsource (lib "eagle-import") (part "EMIF06-1005M12"))
    )
    (comp (ref "FL3")
      (value "EMIF06-1005M12")
      (footprint "eagle-import:SON40P150X250X65-13N")
      (fields (field (name "MOUSER_PART_NUMBER") "511-EMIF06-1005M12"))
      (libsource (lib "eagle-import") (part "EMIF06-1005M12"))
    )
    (comp (ref "FL4")
      (value "EMIF06-1005M12")
      (footprint "eagle-import:SON40P150X250X65-13N")
      (fields (field (name "MOUSER_PART_NUMBER") "511-EMIF06-1005M12"))
      (libsource (lib "eagle-import") (part "EMIF06-1005M12"))
    )
    (comp (ref "FL5")
      (value "EMIF06-1005M12")
      (footprint "eagle-import:SON40P150X250X65-13N")
      (fields (field (name "MOUSER_PART_NUMBER") "511-EMIF06-1005M12"))
      (libsource (lib "eagle-import") (part "EMIF06-1005M12"))
    )
    (comp (ref "H1")
      (value "MOUNT-PAD-ROUND2.8")
      (footprint "eagle-import:2,8-PAD")
      (libsource (lib "eagle-import") (part "MOUNT-PAD-ROUND2.8"))
    )
    (comp (ref "H2")
      (value "MOUNT-PAD-ROUND2.8")
      (footprint "eagle-import:2,8-PAD")
      (libsource (lib "eagle-import") (part "MOUNT-PAD-ROUND2.8"))
    )
    (comp (ref "IC1")
      (value "LM66200DRLR")
      (footprint "eagle-import:SOTFL50P160X60-8N")
      (fields (field (name "MOUSER_PART_NUMBER") "595-LM66200DRLR"))
      (libsource (lib "eagle-import") (part "LM66200DRLR"))
    )
    (comp (ref "IC2")
      (value "AP61300Z6-7")
      (footprint "eagle-import:SOTFL50P162X60-6N")
      (fields (field (name "MOUSER_PART_NUMBER") "621-AP61300Z6-7"))
      (libsource (lib "eagle-import") (part "AP61300Z6-7"))
    )
    (comp (ref "IC3")
      (value "IS42S16160G-6BL")
      (footprint "eagle-import:BGA54C80P9X9_800X800X120")
      (fields (field (name "MOUSER_PART_NUMBER") "870-IS42S16160G-6BL"))
      (libsource (lib "eagle-import") (part "IS42S16160G-6BL"))
    )
    (comp (ref "IC4")
      (value "ATECC608B-MAHDA-T")
      (footprint "eagle-import:SON50P300X200X60-9N")
      (fields (field (name "MOUSER_PART_NUMBER") "579-TECC608B-MAHDA-T"))
      (libsource (lib "eagle-import") (part "ATECC608B-MAHDA-T"))
    )
    (comp (ref "IC5")
      (value "IS25LP064D-JKLE-TR")
      (footprint "eagle-import:SON127P500X595X80-9N")
      (fields (field (name "MOUSER_PART_NUMBER") "870-5LP064D-JKLE-TR"))
      (libsource (lib "eagle-import") (part "IS25LP064D-JKLE-TR"))
    )
    (comp (ref "IC6")
      (value "IS25LP128F-JKLE-TR")
      (footprint "eagle-import:SON127P500X595X80-9N")
      (fields (field (name "MOUSER_PART_NUMBER") "870-IS25LP128FJKLETR"))
      (libsource (lib "eagle-import") (part "IS25LP128F-JKLE-TR"))
    )
    (comp (ref "IC7")
      (value "MXC4005XC")
      (footprint "eagle-import:MXC4005XC")
      (fields (field (name "MOUSER_PART_NUMBER") "438-MXC4005XC"))
      (libsource (lib "eagle-import") (part "MXC4005XC"))
    )
    (comp (ref "IC8")
      (value "MIMXRT106FCVL5B")
      (footprint "eagle-import:BGA196C65P14X14_1000X1000X143")
      (fields
        (field (name "MANUFACTURER_PART_NUMBER") "MIMXRT1052DVL6B")
        (field (name "MOUSER_PART_NUMBER") "771-MIMXRT1052DVL6B")
      )
      (libsource (lib "eagle-import") (part "MIMXRT1052DVL6B"))
    )
    (comp (ref "IC9")
      (value "KSZ8081RNDCA-TR")
      (footprint "eagle-import:QFN50P400X400X90-25N")
      (fields (field (name "MOUSER_PART_NUMBER") "998-KSZ8081RNDCATR"))
      (libsource (lib "eagle-import") (part "KSZ8081RNDCA-TR"))
    )
    (comp (ref "J1")
      (value "USB4105-GF-A")
      (footprint "eagle-import:GCT_USB4105-GF-A")
      (fields (field (name "MF") "GCT"))
      (libsource (lib "eagle-import") (part "USB4105-GF-A"))
    )
    (comp (ref "J2")
      (value "DNP")
      (footprint "eagle-import:1X08")
      (libsource (lib "eagle-import") (part "CONN_08{dblquote}"))
    )
    (comp (ref "J3")
      (value "DNP")
      (footprint "eagle-import:1X08")
      (libsource (lib "eagle-import") (part "CONN_08{dblquote}"))
    )
    (comp (ref "J4")
      (value "DF12-36-DS")
      (footprint "eagle-import:DF12-36-DS")
      (fields (field (name "MPN") "DF12NB-36DS-0.5V(51)"))
      (libsource (lib "eagle-import") (part "DF12-36-DS"))
    )
    (comp (ref "J5")
      (value "USD-1040310811")
      (footprint "eagle-import:1040310811")
      (fields (field (name "MPN") "104031-0811"))
      (libsource (lib "eagle-import") (part "USD-1040310811"))
    )
    (comp (ref "J6")
      (value "DNP")
      (footprint "eagle-import:1X08")
      (libsource (lib "eagle-import") (part "CONN_08{dblquote}"))
    )
    (comp (ref "J7")
      (value "DNP")
      (footprint "eagle-import:23370191")
      (fields
        (field (name "MANUFACTURER_PART_NUMBER") "2337019-1")
        (field (name "MOUSER_PART_NUMBER") "571-2337019-1")
      )
      (libsource (lib "eagle-import") (part "2337019-1"))
    )
    (comp (ref "J8")
      (value "3221-10-0300-00")
      (footprint "eagle-import:CNC_3221-10-0300-00")
      (fields (field (name "MF") "CNC Tech"))
      (libsource (lib "eagle-import") (part "3221-10-0300-00"))
    )
    (comp (ref "L1")
      (value "100")
      (footprint "eagle-import:0603")
      (fields (field (name "MPN") "MFBM1V1608-101-R"))
      (libsource (lib "eagle-import") (part "INDUCTOR-0603-33NH"))
    )
    (comp (ref "L2")
      (value "MAKK2016T1R0M")
      (footprint "eagle-import:INDC2016X100N")
      (fields (field (name "MF") "Taiyo Yuden"))
      (libsource (lib "eagle-import") (part "MAKK2016T1R0M"))
    )
    (comp (ref "L4")
      (value "100")
      (footprint "eagle-import:C0402")
      (fields (field (name "MPN") "MFBM1V1005-101-R"))
      (libsource (lib "eagle-import") (part "INDUCTOR0402"))
    )
    (comp (ref "L5")
      (value "MAKK2016T4R7M")
      (footprint "eagle-import:INDC2016X100N")
      (fields (field (name "MF") "Taiyo Yuden"))
      (libsource (lib "eagle-import") (part "MAKK2016T4R7M"))
    )
    (comp (ref "L6")
      (value "100")
      (footprint "eagle-import:C0402")
      (fields (field (name "MPN") "MFBM1V1005-101-R"))
      (libsource (lib "eagle-import") (part "INDUCTOR0402"))
    )
    (comp (ref "L7")
      (value "3.9NH")
      (footprint "eagle-import:0402")
      (fields (field (name "MPN") "L-07C3N9SV6T"))
      (libsource (lib "eagle-import") (part "INDUCTOR-0402-3.9NH"))
    )
    (comp (ref "L8")
      (value "100")
      (footprint "eagle-import:C0402")
      (fields (field (name "MPN") "MFBM1V1005-101-R"))
      (libsource (lib "eagle-import") (part "INDUCTOR0402"))
    )
    (comp (ref "L9")
      (value "MAKK2016T2R2M")
      (footprint "eagle-import:INDC2016X100N")
      (fields (field (name "MF") "Taiyo Yuden"))
      (libsource (lib "eagle-import") (part "MAKK2016T2R2M"))
    )
    (comp (ref "M1")
      (value "9774030151R")
      (footprint "eagle-import:9774030151R")
      (libsource (lib "eagle-import") (part "9774030151R"))
    )
    (comp (ref "M2")
      (value "9774030151R")
      (footprint "eagle-import:9774030151R")
      (libsource (lib "eagle-import") (part "9774030151R"))
    )
    (comp (ref "Q1")
      (value "2N7002KW_R1_00001")
      (footprint "eagle-import:SOT65P210X110-3N")
      (fields (field (name "MOUSER_PART_NUMBER") "241-2N7002KWR100001"))
      (libsource (lib "eagle-import") (part "2N7002KW_R1_00001"))
    )
    (comp (ref "Q2")
      (value "2N7002KW_R1_00001")
      (footprint "eagle-import:SOT65P210X110-3N")
      (fields (field (name "MOUSER_PART_NUMBER") "241-2N7002KWR100001"))
      (libsource (lib "eagle-import") (part "2N7002KW_R1_00001"))
    )
    (comp (ref "Q3")
      (value "2N7002KW_R1_00001")
      (footprint "eagle-import:SOT65P210X110-3N")
      (fields (field (name "MOUSER_PART_NUMBER") "241-2N7002KWR100001"))
      (libsource (lib "eagle-import") (part "2N7002KW_R1_00001"))
    )
    (comp (ref "Q4")
      (value "2N7002KW_R1_00001")
      (footprint "eagle-import:SOT65P210X110-3N")
      (fields (field (name "MOUSER_PART_NUMBER") "241-2N7002KWR100001"))
      (libsource (lib "eagle-import") (part "2N7002KW_R1_00001"))
    )
    (comp (ref "Q5")
      (value "2N7002KW_R1_00001")
      (footprint "eagle-import:SOT65P210X110-3N")
      (fields (field (name "MOUSER_PART_NUMBER") "241-2N7002KWR100001"))
      (libsource (lib "eagle-import") (part "2N7002KW_R1_00001"))
    )
    (comp (ref "Q6")
      (value "PMXB120EPEZ")
      (footprint "eagle-import:PMXB120EPEZ")
      (fields (field (name "MOUSER_PART_NUMBER") "771-PMXB120EPEZ"))
      (libsource (lib "eagle-import") (part "PMXB120EPEZ"))
    )
    (comp (ref "R1")
      (value "1K")
      (footprint "eagle-import:0402-RES")
      (fields (field (name "MPN") "CRCW04021K00FKEDC"))
      (libsource (lib "eagle-import") (part "RESISTOR0402-RES"))
    )
    (comp (ref "R2")
      (value "200K")
      (footprint "eagle-import:0402-RES")
      (fields (field (name "MPN") "CRCW0402200KFKEDC"))
      (libsource (lib "eagle-import") (part "RESISTOR0402-RES"))
    )
    (comp (ref "R3")
      (value "100K")
      (footprint "eagle-import:0402-RES")
      (fields (field (name "MPN") "AC0402FR-07100KL"))
      (libsource (lib "eagle-import") (part "RESISTOR0402-RES"))
    )
    (comp (ref "R4")
      (value "1K")
      (footprint "eagle-import:0402-RES")
      (fields (field (name "MPN") "CRCW04021K00FKEDC"))
      (libsource (lib "eagle-import") (part "RESISTOR0402-RES"))
    )
    (comp (ref "R5")
      (value "1K")
      (footprint "eagle-import:0402-RES")
      (fields (field (name "MPN") "CRCW04021K00FKEDC"))
      (libsource (lib "eagle-import") (part "RESISTOR0402-RES"))
    )
    (comp (ref "R6")
      (value "5.1K")
      (footprint "eagle-import:0402-RES")
      (fields (field (name "MPN") "RC0402JR-075K1L"))
      (libsource (lib "eagle-import") (part "RESISTOR0402-RES"))
    )
    (comp (ref "R7")
      (value "5.1K")
      (footprint "eagle-import:0402-RES")
      (fields (field (name "MPN") "RC0402JR-075K1L"))
      (libsource (lib "eagle-import") (part "RESISTOR0402-RES"))
    )
    (comp (ref "R8")
      (value "44.2K")
      (footprint "eagle-import:0402-RES")
      (fields (field (name "MPN") "AC0402FR-0744K2L"))
      (libsource (lib "eagle-import") (part "RESISTOR0402-RES"))
    )
    (comp (ref "R9")
      (value "10K")
      (footprint "eagle-import:0402-RES")
      (fields (field (name "MPN") "AC0402FR-1310KL"))
      (libsource (lib "eagle-import") (part "RESISTOR0402-RES"))
    )
    (comp (ref "R10")
      (value "3.3K")
      (footprint "eagle-import:0402-RES")
      (fields (field (name "MPN") "CRCW04023K30FKEDC"))
      (libsource (lib "eagle-import") (part "RESISTOR0402-RES"))
    )
    (comp (ref "R11")
      (value "46.4K")
      (footprint "eagle-import:0402-RES")
      (fields (field (name "MPN") "WR04X4642FTL"))
      (libsource (lib "eagle-import") (part "RESISTOR0402-RES"))
    )
    (comp (ref "R12")
      (value "8.2K")
      (footprint "eagle-import:0402-RES")
      (fields (field (name "MPN") "RC0402JR-078K2L"))
      (libsource (lib "eagle-import") (part "RESISTOR0402-RES"))
    )
    (comp (ref "R13")
      (value "100K")
      (footprint "eagle-import:0402-RES")
      (fields (field (name "MPN") "AC0402FR-07100KL"))
      (libsource (lib "eagle-import") (part "RESISTOR0402-RES"))
    )
    (comp (ref "R14")
      (value "100K")
      (footprint "eagle-import:0402-RES")
      (fields (field (name "MPN") "AC0402FR-07100KL"))
      (libsource (lib "eagle-import") (part "RESISTOR0402-RES"))
    )
    (comp (ref "R15")
      (value "2.7K")
      (footprint "eagle-import:0402-RES")
      (fields (field (name "MPN") "AC0402JR-072K7L"))
      (libsource (lib "eagle-import") (part "RESISTOR0402-RES"))
    )
    (comp (ref "R16")
      (value "2.7K")
      (footprint "eagle-import:0402-RES")
      (fields (field (name "MPN") "AC0402JR-072K7L"))
      (libsource (lib "eagle-import") (part "RESISTOR0402-RES"))
    )
    (comp (ref "R17")
      (value "2.7K")
      (footprint "eagle-import:0402-RES")
      (fields (field (name "MPN") "AC0402JR-072K7L"))
      (libsource (lib "eagle-import") (part "RESISTOR0402-RES"))
    )
    (comp (ref "R18")
      (value "100K")
      (footprint "eagle-import:0402-RES")
      (fields (field (name "MPN") "AC0402FR-07100KL"))
      (libsource (lib "eagle-import") (part "RESISTOR0402-RES"))
    )
    (comp (ref "R19")
      (value "220")
      (footprint "eagle-import:0402-RES")
      (fields (field (name "MPN") "CRGCQ0402F220R"))
      (libsource (lib "eagle-import") (part "RESISTOR0402-RES"))
    )
    (comp (ref "R20")
      (value "220")
      (footprint "eagle-import:0402-RES")
      (fields (field (name "MPN") "CRGCQ0402F220R"))
      (libsource (lib "eagle-import") (part "RESISTOR0402-RES"))
    )
    (comp (ref "R21")
      (value "220")
      (footprint "eagle-import:0402-RES")
      (fields (field (name "MPN") "CRGCQ0402F220R"))
      (libsource (lib "eagle-import") (part "RESISTOR0402-RES"))
    )
    (comp (ref "R22")
      (value "100K")
      (footprint "eagle-import:0402-RES")
      (fields (field (name "MPN") "AC0402FR-07100KL"))
      (libsource (lib "eagle-import") (part "RESISTOR0402-RES"))
    )
    (comp (ref "R23")
      (value "100K")
      (footprint "eagle-import:0402-RES")
      (fields (field (name "MPN") "AC0402FR-07100KL"))
      (libsource (lib "eagle-import") (part "RESISTOR0402-RES"))
    )
    (comp (ref "R24")
      (value "100K")
      (footprint "eagle-import:0402-RES")
      (fields (field (name "MPN") "AC0402FR-07100KL"))
      (libsource (lib "eagle-import") (part "RESISTOR0402-RES"))
    )
    (comp (ref "R25")
      (value "100K")
      (footprint "eagle-import:0402-RES")
      (fields (field (name "MPN") "AC0402FR-07100KL"))
      (libsource (lib "eagle-import") (part "RESISTOR0402-RES"))
    )
    (comp (ref "R26")
      (value "1K")
      (footprint "eagle-import:0402-RES")
      (fields (field (name "MPN") "CRCW04021K00FKEDC"))
      (libsource (lib "eagle-import") (part "RESISTOR0402-RES"))
    )
    (comp (ref "R27")
      (value "100K")
      (footprint "eagle-import:0402-RES")
      (fields (field (name "MPN") "AC0402FR-07100KL"))
      (libsource (lib "eagle-import") (part "RESISTOR0402-RES"))
    )
    (comp (ref "R28")
      (value "100K")
      (footprint "eagle-import:0402-RES")
      (fields (field (name "MPN") "AC0402FR-07100KL"))
      (libsource (lib "eagle-import") (part "RESISTOR0402-RES"))
    )
    (comp (ref "R29")
      (value "100K")
      (footprint "eagle-import:0402-RES")
      (fields (field (name "MPN") "AC0402FR-07100KL"))
      (libsource (lib "eagle-import") (part "RESISTOR0402-RES"))
    )
    (comp (ref "R30")
      (value "4.7K")
      (footprint "eagle-import:0402-RES")
      (fields (field (name "MPN") "AC0402FR-074K7L"))
      (libsource (lib "eagle-import") (part "RESISTOR0402-RES"))
    )
    (comp (ref "R31")
      (value "4.7K")
      (footprint "eagle-import:0402-RES")
      (fields (field (name "MPN") "AC0402FR-074K7L"))
      (libsource (lib "eagle-import") (part "RESISTOR0402-RES"))
    )
    (comp (ref "R32")
      (value "30K")
      (footprint "eagle-import:0402-RES")
      (fields (field (name "MPN") "0402WGF3002TCE"))
      (libsource (lib "eagle-import") (part "RESISTOR0402-RES"))
    )
    (comp (ref "R33")
      (value "10K")
      (footprint "eagle-import:0402-RES")
      (fields (field (name "MPN") "AC0402FR-1310KL"))
      (libsource (lib "eagle-import") (part "RESISTOR0402-RES"))
    )
    (comp (ref "R34")
      (value "100K")
      (footprint "eagle-import:0402-RES")
      (fields (field (name "MPN") "AC0402FR-07100KL"))
      (libsource (lib "eagle-import") (part "RESISTOR0402-RES"))
    )
    (comp (ref "R35")
      (value "220")
      (footprint "eagle-import:0402-RES")
      (fields (field (name "MPN") "CRGCQ0402F220R"))
      (libsource (lib "eagle-import") (part "RESISTOR0402-RES"))
    )
    (comp (ref "R36")
      (value "1K")
      (footprint "eagle-import:0402-RES")
      (fields (field (name "MPN") "CRCW04021K00FKEDC"))
      (libsource (lib "eagle-import") (part "RESISTOR0402-RES"))
    )
    (comp (ref "R37")
      (value "10K")
      (footprint "eagle-import:0402-RES")
      (fields (field (name "MPN") "AC0402FR-1310KL"))
      (libsource (lib "eagle-import") (part "RESISTOR0402-RES"))
    )
    (comp (ref "R38")
      (value "6.49K")
      (footprint "eagle-import:0402-RES")
      (fields (field (name "MPN") "CR0402-FX-6491GLF"))
      (libsource (lib "eagle-import") (part "RESISTOR0402-RES"))
    )
    (comp (ref "R39")
      (value "1K")
      (footprint "eagle-import:0402-RES")
      (fields (field (name "MPN") "CRCW04021K00FKEDC"))
      (libsource (lib "eagle-import") (part "RESISTOR0402-RES"))
    )
    (comp (ref "R40")
      (value "2.2M")
      (footprint "eagle-import:0402-RES")
      (fields (field (name "MPN") "RC0402FR-072M2L"))
      (libsource (lib "eagle-import") (part "RESISTOR0402-RES"))
    )
    (comp (ref "R41")
      (value "1M")
      (footprint "eagle-import:0402-RES")
      (fields (field (name "MPN") "CRCW04021M00FKEDC"))
      (libsource (lib "eagle-import") (part "RESISTOR0402-RES"))
    )
    (comp (ref "RN1")
      (value "EXB-2HV104JV")
      (footprint "eagle-import:EXB2HV104JV")
      (fields (field (name "MOUSER_PART_NUMBER") "667-EXB-2HV104JV"))
      (libsource (lib "eagle-import") (part "EXB-2HV104JV"))
    )
    (comp (ref "RN2")
      (value "EXB-2HV104JV")
      (footprint "eagle-import:EXB2HV104JV")
      (fields (field (name "MOUSER_PART_NUMBER") "667-EXB-2HV104JV"))
      (libsource (lib "eagle-import") (part "EXB-2HV104JV"))
    )
    (comp (ref "U1")
      (value "MIC5365-3.3YMT-TZ")
      (footprint "eagle-import:VREG_MIC5365-3.3YMT-TZ")
      (libsource (lib "eagle-import") (part "MIC5365-3.3YMT-TZ"))
    )
    (comp (ref "U2")
      (value "BQ24075RGTR")
      (footprint "eagle-import:QFN50P300X300X100-17N")
      (fields (field (name "MF") "Texas Instruments"))
      (libsource (lib "eagle-import") (part "BQ24075RGTR"))
    )
    (comp (ref "U3")
      (value "LBEE5KL1DX-883")
      (footprint "eagle-import:XCVR_LBEE5KL1DX-TEMP")
      (fields (field (name "MF") "Murata Electronics") (field (name "MP") "LBEE5KL1DX-TEMP"))
      (libsource (lib "eagle-import") (part "LBEE5KL1DX-TEMP"))
    )
    (comp (ref "Y1")
      (value "SC32S-7PF20PPM")
      (footprint "eagle-import:XTAL_ABS07-32.768KHZ-7-T")
      (fields (field (name "MF") "Abracon") (field (name "MP") "ABS07-32.768KHZ-7-T"))
      (libsource (lib "eagle-import") (part "ABS07-32.768KHZ-7-T"))
    )
    (comp (ref "Y2")
      (value "XRCGB24M000F3M00R0")
      (footprint "eagle-import:XRCGB24M000F3M00R0")
      (fields (field (name "MOUSER_PART_NUMBER") "81-XRCGB24M000F3M0R0"))
      (libsource (lib "eagle-import") (part "XRCGB24M000F3M00R0"))
    )
  )
  (nets
    (net (code "1") (name "/BT_D_WAKE") (class "Default")
      (node (ref "IC8") (pin "L7") (pinfunction "PMIC_STBY_REQ_L7") (pintype "bidirectional"))
      (node (ref "U3") (pin "39") (pinfunction "BT_DEV_WAKE_39") (pintype "bidirectional"))
    )
    (net (code "2") (name "/BT_H_WAKE") (class "Default")
      (node (ref "IC8") (pin "H14") (pinfunction "GPIO_AD_B0_14_H14") (pintype "bidirectional"))
      (node (ref "U3") (pin "38") (pinfunction "BT_HOST_WAKE_38") (pintype "bidirectional"))
    )
    (net (code "3") (name "/BT_REG_ON") (class "Default")
      (node (ref "IC8") (pin "F13") (pinfunction "GPIO_AD_B0_08_F13") (pintype "bidirectional"))
      (node (ref "R37") (pin "1") (pinfunction "1_1") (pintype "passive"))
      (node (ref "U3") (pin "14") (pinfunction "BT_REG_ON_14") (pintype "input"))
    )
    (net (code "4") (name "/BT_UART_RX") (class "Default")
      (node (ref "IC8") (pin "C9") (pinfunction "GPIO_B0_09_C9") (pintype "bidirectional"))
      (node (ref "U3") (pin "3") (pinfunction "BT_UART_TXD_3") (pintype "output"))
    )
    (net (code "5") (name "/BT_UART_TX") (class "Default")
      (node (ref "IC8") (pin "B9") (pinfunction "GPIO_B0_08_B9") (pintype "bidirectional"))
      (node (ref "U3") (pin "2") (pinfunction "BT_UART_RXD_2") (pintype "input"))
    )
    (net (code "6") (name "/DCDC_LP") (class "Default")
      (node (ref "IC8") (pin "M1") (pinfunction "DCDC_LP_1_M1") (pintype "bidirectional"))
      (node (ref "IC8") (pin "M2") (pinfunction "DCDC_LP_2_M2") (pintype "bidirectional"))
      (node (ref "L5") (pin "2") (pinfunction "2_2") (pintype "passive"))
    )
    (net (code "7") (name "/DCDC_PSWITCH") (class "Default")
      (node (ref "C62") (pin "1") (pinfunction "1_1") (pintype "passive"))
      (node (ref "IC8") (pin "K3") (pinfunction "DCDC_PSWITCH_K3") (pintype "bidirectional"))
      (node (ref "R32") (pin "1") (pinfunction "1_1") (pintype "passive"))
    )
    (net (code "8") (name "/DCMI_CLK") (class "Default")
      (node (ref "IC8") (pin "B14") (pinfunction "GPIO_B1_15_B14") (pintype "bidirectional"))
      (node (ref "J4") (pin "12") (pinfunction "12_12") (pintype "bidirectional"))
    )
    (net (code "9") (name "/DCMI_D0") (class "Default")
      (node (ref "IC8") (pin "J14") (pinfunction "GPIO_AD_B1_15_J14") (pintype "bidirectional"))
      (node (ref "J4") (pin "31") (pinfunction "31_31") (pintype "bidirectional"))
    )
    (net (code "10") (name "/DCMI_D1") (class "Default")
      (node (ref "IC8") (pin "G12") (pinfunction "GPIO_AD_B1_14_G12") (pintype "bidirectional"))
      (node (ref "J4") (pin "29") (pinfunction "29_29") (pintype "bidirectional"))
    )
    (net (code "11") (name "/DCMI_D2") (class "Default")
      (node (ref "IC8") (pin "H11") (pinfunction "GPIO_AD_B1_13_H11") (pintype "bidirectional"))
      (node (ref "J4") (pin "35") (pinfunction "35_35") (pintype "bidirectional"))
    )
    (net (code "12") (name "/DCMI_D3") (class "Default")
      (node (ref "IC8") (pin "H12") (pinfunction "GPIO_AD_B1_12_H12") (pintype "bidirectional"))
      (node (ref "J4") (pin "28") (pinfunction "28_28") (pintype "bidirectional"))
    )
    (net (code "13") (name "/DCMI_D4") (class "Default")
      (node (ref "IC8") (pin "J13") (pinfunction "GPIO_AD_B1_11_J13") (pintype "bidirectional"))
      (node (ref "J4") (pin "26") (pinfunction "26_26") (pintype "bidirectional"))
    )
    (net (code "14") (name "/DCMI_D5") (class "Default")
      (node (ref "IC8") (pin "L13") (pinfunction "GPIO_AD_B1_10_L13") (pintype "bidirectional"))
      (node (ref "J4") (pin "33") (pinfunction "33_33") (pintype "bidirectional"))
    )
    (net (code "15") (name "/DCMI_D6") (class "Default")
      (node (ref "IC8") (pin "G14") (pinfunction "GPIO_AD_B0_05_G14") (pintype "bidirectional"))
      (node (ref "J4") (pin "24") (pinfunction "24_24") (pintype "bidirectional"))
    )
    (net (code "16") (name "/DCMI_D7") (class "Default")
      (node (ref "IC8") (pin "F11") (pinfunction "GPIO_AD_B0_04_F11") (pintype "bidirectional"))
      (node (ref "J4") (pin "22") (pinfunction "22_22") (pintype "bidirectional"))
    )
    (net (code "17") (name "/DCMI_FSIN") (class "Default")
      (node (ref "J4") (pin "23") (pinfunction "23_23") (pintype "bidirectional"))
      (node (ref "Q5") (pin "3") (pinfunction "D_3") (pintype "bidirectional"))
      (node (ref "R28") (pin "1") (pinfunction "1_1") (pintype "passive"))
    )
    (net (code "18") (name "/DCMI_HSYNC") (class "Default")
      (node (ref "IC8") (pin "L10") (pinfunction "GPIO_AD_B0_15_L10") (pintype "bidirectional"))
      (node (ref "J4") (pin "18") (pinfunction "18_18") (pintype "bidirectional"))
    )
    (net (code "19") (name "/DCMI_MISO") (class "Default")
      (node (ref "IC8") (pin "E7") (pinfunction "GPIO_B0_01_E7") (pintype "bidirectional"))
      (node (ref "J4") (pin "15") (pinfunction "15_15") (pintype "bidirectional"))
    )
    (net (code "20") (name "/DCMI_MOSI") (class "Default")
      (node (ref "IC8") (pin "E8") (pinfunction "GPIO_B0_02_E8") (pintype "bidirectional"))
      (node (ref "J4") (pin "17") (pinfunction "17_17") (pintype "bidirectional"))
    )
    (net (code "21") (name "/DCMI_PCLK") (class "Default")
      (node (ref "IC8") (pin "D13") (pinfunction "GPIO_B1_12_D13") (pintype "bidirectional"))
      (node (ref "J4") (pin "14") (pinfunction "14_14") (pintype "bidirectional"))
    )
    (net (code "22") (name "/DCMI_PWDN") (class "Default")
      (node (ref "IC8") (pin "C11") (pinfunction "GPIO_B1_02_C11") (pintype "bidirectional"))
      (node (ref "J4") (pin "25") (pinfunction "25_25") (pintype "bidirectional"))
      (node (ref "R29") (pin "1") (pinfunction "1_1") (pintype "passive"))
    )
    (net (code "23") (name "/DCMI_RST") (class "Default")
      (node (ref "IC8") (pin "B11") (pinfunction "GPIO_B1_01_B11") (pintype "bidirectional"))
      (node (ref "J4") (pin "21") (pinfunction "21_21") (pintype "bidirectional"))
      (node (ref "R27") (pin "1") (pinfunction "1_1") (pintype "passive"))
    )
    (net (code "24") (name "/DCMI_SCL") (class "Default")
      (node (ref "IC8") (pin "J11") (pinfunction "GPIO_AD_B1_00_J11") (pintype "bidirectional"))
      (node (ref "J4") (pin "32") (pinfunction "32_32") (pintype "bidirectional"))
      (node (ref "R30") (pin "1") (pinfunction "1_1") (pintype "passive"))
    )
    (net (code "25") (name "/DCMI_SCLK") (class "Default")
      (node (ref "IC8") (pin "D8") (pinfunction "GPIO_B0_03_D8") (pintype "bidirectional"))
      (node (ref "J4") (pin "13") (pinfunction "13_13") (pintype "bidirectional"))
    )
    (net (code "26") (name "/DCMI_SDA") (class "Default")
      (node (ref "IC8") (pin "K11") (pinfunction "GPIO_AD_B1_01_K11") (pintype "bidirectional"))
      (node (ref "J4") (pin "34") (pinfunction "34_34") (pintype "bidirectional"))
      (node (ref "R31") (pin "1") (pinfunction "1_1") (pintype "passive"))
    )
    (net (code "27") (name "/DCMI_SSEL") (class "Default")
      (node (ref "IC8") (pin "D7") (pinfunction "GPIO_B0_00_D7") (pintype "bidirectional"))
      (node (ref "J4") (pin "11") (pinfunction "11_11") (pintype "bidirectional"))
      (node (ref "R24") (pin "1") (pinfunction "1_1") (pintype "passive"))
    )
    (net (code "28") (name "/DCMI_VSYNC") (class "Default")
      (node (ref "IC8") (pin "D14") (pinfunction "GPIO_B1_13_D14") (pintype "bidirectional"))
      (node (ref "J4") (pin "16") (pinfunction "16_16") (pintype "bidirectional"))
    )
    (net (code "29") (name "/ETH_INT") (class "Default")
      (node (ref "IC8") (pin "C10") (pinfunction "GPIO_B0_12_C10") (pintype "bidirectional"))
      (node (ref "IC9") (pin "18") (pinfunction "INTRP_18") (pintype "bidirectional"))
      (node (ref "R36") (pin "1") (pinfunction "1_1") (pintype "passive"))
    )
    (net (code "30") (name "/ETH_MDC") (class "Default")
      (node (ref "IC8") (pin "A7") (pinfunction "GPIO_EMC_40_A7") (pintype "bidirectional"))
      (node (ref "IC9") (pin "11") (pinfunction "MDC_11") (pintype "bidirectional"))
    )
    (net (code "31") (name "/ETH_MDIO") (class "Default")
      (node (ref "IC8") (pin "C7") (pinfunction "GPIO_EMC_41_C7") (pintype "bidirectional"))
      (node (ref "IC9") (pin "10") (pinfunction "MDIO_10") (pintype "bidirectional"))
      (node (ref "R39") (pin "1") (pinfunction "1_1") (pintype "passive"))
    )
    (net (code "32") (name "/ETH_RST") (class "Default")
      (node (ref "C65") (pin "2") (pinfunction "2_2") (pintype "passive"))
      (node (ref "IC8") (pin "D10") (pinfunction "GPIO_B0_13_D10") (pintype "bidirectional"))
      (node (ref "IC9") (pin "24") (pinfunction "RST#_24") (pintype "bidirectional"))
      (node (ref "R34") (pin "1") (pinfunction "1_1") (pintype "passive"))
    )
    (net (code "33") (name "/ETH_RXD0") (class "Default")
      (node (ref "IC8") (pin "E12") (pinfunction "GPIO_B1_04_E12") (pintype "bidirectional"))
      (node (ref "IC9") (pin "13") (pinfunction "RXD0_13") (pintype "bidirectional"))
    )
    (net (code "34") (name "/ETH_RXD1") (class "Default")
      (node (ref "IC8") (pin "D12") (pinfunction "GPIO_B1_05_D12") (pintype "bidirectional"))
      (node (ref "IC9") (pin "12") (pinfunction "RXD1_12") (pintype "bidirectional"))
    )
    (net (code "35") (name "/ETH_RXDV") (class "Default")
      (node (ref "IC8") (pin "C12") (pinfunction "GPIO_B1_06_C12") (pintype "bidirectional"))
      (node (ref "IC9") (pin "15") (pinfunction "CRS_DV/_PHYAD[1:0]_15") (pintype "bidirectional"))
    )
    (net (code "36") (name "/ETH_RXERR") (class "Default")
      (node (ref "IC8") (pin "C13") (pinfunction "GPIO_B1_11_C13") (pintype "bidirectional"))
      (node (ref "IC9") (pin "17") (pinfunction "RXER_17") (pintype "bidirectional"))
    )
    (net (code "37") (name "/ETH_TXCLK") (class "Default")
      (node (ref "IC8") (pin "B13") (pinfunction "GPIO_B1_10_B13") (pintype "bidirectional"))
      (node (ref "IC9") (pin "8") (pinfunction "XI_8") (pintype "bidirectional"))
    )
    (net (code "38") (name "/ETH_TXD0") (class "Default")
      (node (ref "IC8") (pin "B12") (pinfunction "GPIO_B1_07_B12") (pintype "bidirectional"))
      (node (ref "IC9") (pin "20") (pinfunction "TXD0_20") (pintype "bidirectional"))
    )
    (net (code "39") (name "/ETH_TXD1") (class "Default")
      (node (ref "IC8") (pin "A12") (pinfunction "GPIO_B1_08_A12") (pintype "bidirectional"))
      (node (ref "IC9") (pin "21") (pinfunction "TXD1_21") (pintype "bidirectional"))
    )
    (net (code "40") (name "/ETH_TXEN") (class "Default")
      (node (ref "IC8") (pin "A13") (pinfunction "GPIO_B1_09_A13") (pintype "bidirectional"))
      (node (ref "IC9") (pin "19") (pinfunction "TXEN_19") (pintype "bidirectional"))
    )
    (net (code "41") (name "/INT_I2C_INT") (class "Default")
      (node (ref "IC7") (pin "4") (pinfunction "INT_4") (pintype "bidirectional"))
      (node (ref "IC8") (pin "D11") (pinfunction "GPIO_B1_03_D11") (pintype "bidirectional"))
      (node (ref "R17") (pin "1") (pinfunction "1_1") (pintype "passive"))
    )
    (net (code "42") (name "/INT_I2C_SCL") (class "Default")
      (node (ref "IC4") (pin "6") (pinfunction "SCL_6") (pintype "bidirectional"))
      (node (ref "IC7") (pin "1") (pinfunction "SCL_1") (pintype "bidirectional"))
      (node (ref "IC8") (pin "C8") (pinfunction "GPIO_B0_04_C8") (pintype "bidirectional"))
      (node (ref "R15") (pin "1") (pinfunction "1_1") (pintype "passive"))
    )
    (net (code "43") (name "/INT_I2C_SDA") (class "Default")
      (node (ref "IC4") (pin "5") (pinfunction "SDA_5") (pintype "bidirectional"))
      (node (ref "IC7") (pin "5") (pinfunction "SDA_5") (pintype "bidirectional"))
      (node (ref "IC8") (pin "B8") (pinfunction "GPIO_B0_05_B8") (pintype "bidirectional"))
      (node (ref "R16") (pin "1") (pinfunction "1_1") (pintype "passive"))
    )
    (net (code "44") (name "/JTAG_TCK") (class "Default")
      (node (ref "FL5") (pin "4") (pinfunction "INPUT_4_4") (pintype "bidirectional"))
      (node (ref "IC8") (pin "F12") (pinfunction "GPIO_AD_B0_07_F12") (pintype "bidirectional"))
    )
    (net (code "45") (name "/JTAG_TCK_INT") (class "Default")
      (node (ref "FL5") (pin "9") (pinfunction "OUTPUT_4_9") (pintype "bidirectional"))
      (node (ref "J8") (pin "4") (pinfunction "4_4") (pintype "passive"))
    )
    (net (code "46") (name "/JTAG_TDI") (class "Default")
      (node (ref "FL5") (pin "2") (pinfunction "INPUT_2_2") (pintype "bidirectional"))
      (node (ref "IC8") (pin "F14") (pinfunction "GPIO_AD_B0_09_F14") (pintype "bidirectional"))
    )
    (net (code "47") (name "/JTAG_TDI_INT") (class "Default")
      (node (ref "FL5") (pin "11") (pinfunction "OUTPUT_2_11") (pintype "bidirectional"))
      (node (ref "J8") (pin "8") (pinfunction "8_8") (pintype "passive"))
    )
    (net (code "48") (name "/JTAG_TDO") (class "Default")
      (node (ref "FL5") (pin "3") (pinfunction "INPUT_3_3") (pintype "bidirectional"))
      (node (ref "IC8") (pin "G13") (pinfunction "GPIO_AD_B0_10_G13") (pintype "bidirectional"))
    )
    (net (code "49") (name "/JTAG_TDO_INT") (class "Default")
      (node (ref "FL5") (pin "10") (pinfunction "OUTPUT_3_10") (pintype "bidirectional"))
      (node (ref "J8") (pin "6") (pinfunction "6_6") (pintype "passive"))
    )
    (net (code "50") (name "/JTAG_TMS") (class "Default")
      (node (ref "FL5") (pin "5") (pinfunction "INPUT_5_5") (pintype "bidirectional"))
      (node (ref "IC8") (pin "E14") (pinfunction "GPIO_AD_B0_06_E14") (pintype "bidirectional"))
    )
    (net (code "51") (name "/JTAG_TMS_INT") (class "Default")
      (node (ref "FL5") (pin "8") (pinfunction "OUTPUT_5_8") (pintype "bidirectional"))
      (node (ref "J8") (pin "2") (pinfunction "2_2") (pintype "passive"))
    )
    (net (code "52") (name "/JTAG_TRSTB") (class "Default")
      (node (ref "FL5") (pin "6") (pinfunction "INPUT_6_6") (pintype "bidirectional"))
      (node (ref "IC8") (pin "G10") (pinfunction "GPIO_AD_B0_11_G10") (pintype "bidirectional"))
    )
    (net (code "53") (name "/LED_B") (class "Default")
      (node (ref "IC8") (pin "C14") (pinfunction "GPIO_B1_14_C14") (pintype "bidirectional"))
      (node (ref "R19") (pin "1") (pinfunction "1_1") (pintype "passive"))
    )
    (net (code "54") (name "/LED_CHG") (class "Default")
      (node (ref "D1") (pin "3") (pinfunction "RED_3") (pintype "passive"))
      (node (ref "R1") (pin "2") (pinfunction "2_2") (pintype "passive"))
    )
    (net (code "55") (name "/LED_G") (class "Default")
      (node (ref "IC8") (pin "A10") (pinfunction "GPIO_B0_11_A10") (pintype "bidirectional"))
      (node (ref "R20") (pin "1") (pinfunction "1_1") (pintype "passive"))
    )
    (net (code "56") (name "/LED_PGOOD") (class "Default")
      (node (ref "D1") (pin "2") (pinfunction "GREEN_2") (pintype "passive"))
      (node (ref "R4") (pin "2") (pinfunction "2_2") (pintype "passive"))
    )
    (net (code "57") (name "/LED_R") (class "Default")
      (node (ref "IC8") (pin "D9") (pinfunction "GPIO_B0_10_D9") (pintype "bidirectional"))
      (node (ref "R21") (pin "1") (pinfunction "1_1") (pintype "passive"))
    )
    (net (code "58") (name "/MDI_LED") (class "Default")
      (node (ref "J3") (pin "8") (pinfunction "8_8") (pintype "passive"))
      (node (ref "R35") (pin "2") (pinfunction "2_2") (pintype "passive"))
    )
    (net (code "59") (name "/MDI_RX_N") (class "Default")
      (node (ref "IC9") (pin "3") (pinfunction "RXM_3") (pintype "bidirectional"))
      (node (ref "J3") (pin "7") (pinfunction "7_7") (pintype "passive"))
    )
    (net (code "60") (name "/MDI_RX_P") (class "Default")
      (node (ref "IC9") (pin "4") (pinfunction "RXP_4") (pintype "bidirectional"))
      (node (ref "J3") (pin "6") (pinfunction "6_6") (pintype "passive"))
    )
    (net (code "61") (name "/MDI_TX_N") (class "Default")
      (node (ref "IC9") (pin "5") (pinfunction "TXM_5") (pintype "bidirectional"))
      (node (ref "J3") (pin "5") (pinfunction "5_5") (pintype "passive"))
    )
    (net (code "62") (name "/MDI_TX_P") (class "Default")
      (node (ref "IC9") (pin "6") (pinfunction "TXP_6") (pintype "bidirectional"))
      (node (ref "J3") (pin "4") (pinfunction "4_4") (pintype "passive"))
    )
    (net (code "63") (name "/NVCC_PLL") (class "Default")
      (node (ref "C104") (pin "2") (pinfunction "2_2") (pintype "passive"))
      (node (ref "C107") (pin "1") (pinfunction "1_1") (pintype "passive"))
      (node (ref "IC8") (pin "P10") (pinfunction "NVCC_PLL_P10") (pintype "bidirectional"))
    )
    (net (code "64") (name "/ONOFF") (class "Default")
      (node (ref "IC8") (pin "M6") (pinfunction "ONOFF_M6") (pintype "bidirectional"))
      (node (ref "Q3") (pin "2") (pinfunction "S_2") (pintype "bidirectional"))
    )
    (net (code "65") (name "/P0_MOSI") (class "Default")
      (node (ref "FL2") (pin "1") (pinfunction "INPUT_1_1") (pintype "bidirectional"))
      (node (ref "IC8") (pin "H10") (pinfunction "GPIO_AD_B0_01_H10") (pintype "bidirectional"))
    )
    (net (code "66") (name "/P1_MISO") (class "Default")
      (node (ref "FL2") (pin "2") (pinfunction "INPUT_2_2") (pintype "bidirectional"))
      (node (ref "IC8") (pin "M11") (pinfunction "GPIO_AD_B0_02_M11") (pintype "bidirectional"))
    )
    (net (code "67") (name "/P2_SCLK") (class "Default")
      (node (ref "FL2") (pin "3") (pinfunction "INPUT_3_3") (pintype "bidirectional"))
      (node (ref "IC8") (pin "M14") (pinfunction "GPIO_AD_B0_00_M14") (pintype "bidirectional"))
    )
    (net (code "68") (name "/P3_NSS") (class "Default")
      (node (ref "FL2") (pin "4") (pinfunction "INPUT_4_4") (pintype "bidirectional"))
      (node (ref "IC8") (pin "G11") (pinfunction "GPIO_AD_B0_03_G11") (pintype "bidirectional"))
    )
    (net (code "69") (name "/P4_SCL") (class "Default")
      (node (ref "FL2") (pin "5") (pinfunction "INPUT_5_5") (pintype "bidirectional"))
      (node (ref "IC8") (pin "K14") (pinfunction "GPIO_AD_B0_12_K14") (pintype "bidirectional"))
    )
    (net (code "70") (name "/P5_SDA") (class "Default")
      (node (ref "FL2") (pin "6") (pinfunction "INPUT_6_6") (pintype "bidirectional"))
      (node (ref "IC8") (pin "L14") (pinfunction "GPIO_AD_B0_13_L14") (pintype "bidirectional"))
    )
    (net (code "71") (name "/P6_ADC") (class "Default")
      (node (ref "FL4") (pin "1") (pinfunction "INPUT_1_1") (pintype "bidirectional"))
      (node (ref "IC8") (pin "M12") (pinfunction "GPIO_AD_B1_03_M12") (pintype "bidirectional"))
    )
    (net (code "72") (name "/P7_PWM") (class "Default")
      (node (ref "FL4") (pin "2") (pinfunction "INPUT_2_2") (pintype "bidirectional"))
      (node (ref "IC8") (pin "A8") (pinfunction "GPIO_B0_06_A8") (pintype "bidirectional"))
    )
    (net (code "73") (name "/P7_PWM_INT") (class "Default")
      (node (ref "FL4") (pin "11") (pinfunction "OUTPUT_2_11") (pintype "bidirectional"))
      (node (ref "J6") (pin "3") (pinfunction "3_3") (pintype "passive"))
    )
    (net (code "74") (name "/P8_PWM") (class "Default")
      (node (ref "FL4") (pin "3") (pinfunction "INPUT_3_3") (pintype "bidirectional"))
      (node (ref "IC8") (pin "A9") (pinfunction "GPIO_B0_07_A9") (pintype "bidirectional"))
    )
    (net (code "75") (name "/P8_PWM_INT") (class "Default")
      (node (ref "FL4") (pin "10") (pinfunction "OUTPUT_3_10") (pintype "bidirectional"))
      (node (ref "J6") (pin "4") (pinfunction "4_4") (pintype "passive"))
    )
    (net (code "76") (name "/P9_PWM") (class "Default")
      (node (ref "FL4") (pin "4") (pinfunction "INPUT_4_4") (pintype "bidirectional"))
      (node (ref "IC8") (pin "A11") (pinfunction "GPIO_B1_00_A11") (pintype "bidirectional"))
    )
    (net (code "77") (name "/P9_PWM_INT") (class "Default")
      (node (ref "FL4") (pin "9") (pinfunction "OUTPUT_4_9") (pintype "bidirectional"))
      (node (ref "J6") (pin "5") (pinfunction "5_5") (pintype "passive"))
    )
    (net (code "78") (name "/P10_PWM") (class "Default")
      (node (ref "FL4") (pin "5") (pinfunction "INPUT_5_5") (pintype "bidirectional"))
      (node (ref "Q4") (pin "3") (pinfunction "D_3") (pintype "bidirectional"))
      (node (ref "R26") (pin "1") (pinfunction "1_1") (pintype "passive"))
    )
    (net (code "79") (name "/P10_PWM_INT") (class "Default")
      (node (ref "FL4") (pin "8") (pinfunction "OUTPUT_5_8") (pintype "bidirectional"))
      (node (ref "J6") (pin "6") (pinfunction "6_6") (pintype "passive"))
    )
    (net (code "80") (name "/P11_WAKEUP") (class "Default")
      (node (ref "FL4") (pin "6") (pinfunction "INPUT_6_6") (pintype "bidirectional"))
      (node (ref "Q2") (pin "3") (pinfunction "D_3") (pintype "bidirectional"))
      (node (ref "R22") (pin "1") (pinfunction "1_1") (pintype "passive"))
    )
    (net (code "81") (name "/P11_WAKEUP_INT") (class "Default")
      (node (ref "FL4") (pin "7") (pinfunction "OUTPUT_6_7") (pintype "bidirectional"))
      (node (ref "J6") (pin "7") (pinfunction "7_7") (pintype "passive"))
    )
    (net (code "82") (name "/P12_RST_N") (class "Default")
      (node (ref "C63") (pin "1") (pinfunction "1_1") (pintype "passive"))
      (node (ref "FL5") (pin "1") (pinfunction "INPUT_1_1") (pintype "bidirectional"))
      (node (ref "IC8") (pin "M7") (pinfunction "POR_B_M7") (pintype "bidirectional"))
      (node (ref "R33") (pin "2") (pinfunction "2_2") (pintype "passive"))
    )
    (net (code "83") (name "/P12_RST_N_EXT") (class "Default")
      (node (ref "FL5") (pin "12") (pinfunction "OUTPUT_1_12") (pintype "bidirectional"))
      (node (ref "J6") (pin "8") (pinfunction "8_8") (pintype "passive"))
      (node (ref "J8") (pin "10") (pinfunction "10_10") (pintype "passive"))
    )
    (net (code "84") (name "/PMIC_ONOFF") (class "Default")
      (node (ref "D8") (pin "1") (pinfunction "1_1") (pintype "bidirectional"))
      (node (ref "J3") (pin "3") (pinfunction "3_3") (pintype "passive"))
      (node (ref "Q3") (pin "3") (pinfunction "D_3") (pintype "bidirectional"))
      (node (ref "R23") (pin "1") (pinfunction "1_1") (pintype "passive"))
    )
    (net (code "85") (name "/PMIC_ON_REQ") (class "Default")
      (node (ref "IC8") (pin "K7") (pinfunction "PMIC_ON_REQ_K7") (pintype "bidirectional"))
      (node (ref "Q1") (pin "2") (pinfunction "S_2") (pintype "bidirectional"))
    )
    (net (code "86") (name "/PWM_FSIN") (class "Default")
      (node (ref "IC8") (pin "B7") (pinfunction "GPIO_EMC_39_B7") (pintype "bidirectional"))
      (node (ref "Q4") (pin "2") (pinfunction "S_2") (pintype "bidirectional"))
      (node (ref "Q5") (pin "2") (pinfunction "S_2") (pintype "bidirectional"))
      (node (ref "R25") (pin "1") (pinfunction "1_1") (pintype "passive"))
    )
    (net (code "87") (name "/P_FLASH_CE") (class "Default")
      (node (ref "IC5") (pin "1") (pinfunction "CE#_1") (pintype "bidirectional"))
      (node (ref "IC8") (pin "L3") (pinfunction "GPIO_SD_B1_06_L3") (pintype "bidirectional"))
      (node (ref "R13") (pin "2") (pinfunction "2_2") (pintype "passive"))
    )
    (net (code "88") (name "/P_FLASH_IO0") (class "Default")
      (node (ref "IC5") (pin "5") (pinfunction "SI_(IO0)_5") (pintype "bidirectional"))
      (node (ref "IC8") (pin "P3") (pinfunction "GPIO_SD_B1_08_P3") (pintype "bidirectional"))
    )
    (net (code "89") (name "/P_FLASH_IO1") (class "Default")
      (node (ref "IC5") (pin "2") (pinfunction "SO_(IO1)_2") (pintype "bidirectional"))
      (node (ref "IC8") (pin "N4") (pinfunction "GPIO_SD_B1_09_N4") (pintype "bidirectional"))
    )
    (net (code "90") (name "/P_FLASH_IO2") (class "Default")
      (node (ref "IC5") (pin "3") (pinfunction "WP#_(IO2)_3") (pintype "bidirectional"))
      (node (ref "IC8") (pin "P4") (pinfunction "GPIO_SD_B1_10_P4") (pintype "bidirectional"))
    )
    (net (code "91") (name "/P_FLASH_IO3") (class "Default")
      (node (ref "IC5") (pin "7") (pinfunction "HOLD#_(IO3)_7") (pintype "bidirectional"))
      (node (ref "IC8") (pin "P5") (pinfunction "GPIO_SD_B1_11_P5") (pintype "bidirectional"))
    )
    (net (code "92") (name "/P_FLASH_SCK") (class "Default")
      (node (ref "IC5") (pin "6") (pinfunction "SCK_6") (pintype "bidirectional"))
      (node (ref "IC8") (pin "L4") (pinfunction "GPIO_SD_B1_07_L4") (pintype "bidirectional"))
    )
    (net (code "93") (name "/RTC_XTALI") (class "Default")
      (node (ref "C80") (pin "1") (pinfunction "1_1") (pintype "passive"))
      (node (ref "IC8") (pin "N9") (pinfunction "RTC_XTALI_N9") (pintype "bidirectional"))
      (node (ref "Y1") (pin "2") (pinfunction "2_2") (pintype "passive"))
    )
    (net (code "94") (name "/RTC_XTALO") (class "Default")
      (node (ref "C79") (pin "1") (pinfunction "1_1") (pintype "passive"))
      (node (ref "IC8") (pin "P9") (pinfunction "RTC_XTALO_P9") (pintype "bidirectional"))
      (node (ref "Y1") (pin "1") (pinfunction "1_1") (pintype "passive"))
    )
    (net (code "95") (name "/SDRAM_A0") (class "Default")
      (node (ref "IC3") (pin "H7") (pinfunction "A0_H7") (pintype "bidirectional"))
      (node (ref "IC8") (pin "C2") (pinfunction "GPIO_EMC_09_C2") (pintype "bidirectional"))
    )
    (net (code "96") (name "/SDRAM_A1") (class "Default")
      (node (ref "IC3") (pin "H8") (pinfunction "A1_H8") (pintype "bidirectional"))
      (node (ref "IC8") (pin "G1") (pinfunction "GPIO_EMC_10_G1") (pintype "bidirectional"))
    )
    (net (code "97") (name "/SDRAM_A2") (class "Default")
      (node (ref "IC3") (pin "J8") (pinfunction "A2_J8") (pintype "bidirectional"))
      (node (ref "IC8") (pin "G3") (pinfunction "GPIO_EMC_11_G3") (pintype "bidirectional"))
    )
    (net (code "98") (name "/SDRAM_A3") (class "Default")
      (node (ref "IC3") (pin "J7") (pinfunction "A3_J7") (pintype "bidirectional"))
      (node (ref "IC8") (pin "H1") (pinfunction "GPIO_EMC_12_H1") (pintype "bidirectional"))
    )
    (net (code "99") (name "/SDRAM_A4") (class "Default")
      (node (ref "IC3") (pin "J3") (pinfunction "A4_J3") (pintype "bidirectional"))
      (node (ref "IC8") (pin "A6") (pinfunction "GPIO_EMC_13_A6") (pintype "bidirectional"))
    )
    (net (code "100") (name "/SDRAM_A5") (class "Default")
      (node (ref "IC3") (pin "J2") (pinfunction "A5_J2") (pintype "bidirectional"))
      (node (ref "IC8") (pin "B6") (pinfunction "GPIO_EMC_14_B6") (pintype "bidirectional"))
    )
    (net (code "101") (name "/SDRAM_A6") (class "Default")
      (node (ref "IC3") (pin "H3") (pinfunction "A6_H3") (pintype "bidirectional"))
      (node (ref "IC8") (pin "B1") (pinfunction "GPIO_EMC_15_B1") (pintype "bidirectional"))
    )
    (net (code "102") (name "/SDRAM_A7") (class "Default")
      (node (ref "IC3") (pin "H2") (pinfunction "A7_H2") (pintype "bidirectional"))
      (node (ref "IC8") (pin "A5") (pinfunction "GPIO_EMC_16_A5") (pintype "bidirectional"))
    )
    (net (code "103") (name "/SDRAM_A8") (class "Default")
      (node (ref "IC3") (pin "H1") (pinfunction "A8_H1") (pintype "bidirectional"))
      (node (ref "IC8") (pin "A4") (pinfunction "GPIO_EMC_17_A4") (pintype "bidirectional"))
    )
    (net (code "104") (name "/SDRAM_A9") (class "Default")
      (node (ref "IC3") (pin "G3") (pinfunction "A9_G3") (pintype "bidirectional"))
      (node (ref "IC8") (pin "B2") (pinfunction "GPIO_EMC_18_B2") (pintype "bidirectional"))
    )
    (net (code "105") (name "/SDRAM_A10") (class "Default")
      (node (ref "IC3") (pin "H9") (pinfunction "A10_H9") (pintype "bidirectional"))
      (node (ref "IC8") (pin "G2") (pinfunction "GPIO_EMC_23_G2") (pintype "bidirectional"))
    )
    (net (code "106") (name "/SDRAM_A11") (class "Default")
      (node (ref "IC3") (pin "G2") (pinfunction "A11_G2") (pintype "bidirectional"))
      (node (ref "IC8") (pin "B4") (pinfunction "GPIO_EMC_19_B4") (pintype "bidirectional"))
    )
    (net (code "107") (name "/SDRAM_A12") (class "Default")
      (node (ref "IC3") (pin "G1") (pinfunction "A12_G1") (pintype "bidirectional"))
      (node (ref "IC8") (pin "A3") (pinfunction "GPIO_EMC_20_A3") (pintype "bidirectional"))
    )
    (net (code "108") (name "/SDRAM_BA0") (class "Default")
      (node (ref "IC3") (pin "G7") (pinfunction "BA0_G7") (pintype "bidirectional"))
      (node (ref "IC8") (pin "C1") (pinfunction "GPIO_EMC_21_C1") (pintype "bidirectional"))
    )
    (net (code "109") (name "/SDRAM_BA1") (class "Default")
      (node (ref "IC3") (pin "G8") (pinfunction "BA1_G8") (pintype "bidirectional"))
      (node (ref "IC8") (pin "F1") (pinfunction "GPIO_EMC_22_F1") (pintype "bidirectional"))
    )
    (net (code "110") (name "/SDRAM_CAS") (class "Default")
      (node (ref "IC3") (pin "F7") (pinfunction "~{CAS}_F7") (pintype "bidirectional"))
      (node (ref "IC8") (pin "D3") (pinfunction "GPIO_EMC_24_D3") (pintype "bidirectional"))
    )
    (net (code "111") (name "/SDRAM_CKE") (class "Default")
      (node (ref "IC3") (pin "F3") (pinfunction "CKE_F3") (pintype "bidirectional"))
      (node (ref "IC8") (pin "A2") (pinfunction "GPIO_EMC_27_A2") (pintype "bidirectional"))
    )
    (net (code "112") (name "/SDRAM_CLK") (class "Default")
      (node (ref "IC3") (pin "F2") (pinfunction "CLK_F2") (pintype "bidirectional"))
      (node (ref "IC8") (pin "B3") (pinfunction "GPIO_EMC_26_B3") (pintype "bidirectional"))
    )
    (net (code "113") (name "/SDRAM_CS") (class "Default")
      (node (ref "IC3") (pin "G9") (pinfunction "~{CS}_G9") (pintype "bidirectional"))
      (node (ref "IC8") (pin "E1") (pinfunction "GPIO_EMC_29_E1") (pintype "bidirectional"))
      (node (ref "R18") (pin "2") (pinfunction "2_2") (pintype "passive"))
    )
    (net (code "114") (name "/SDRAM_DQ0") (class "Default")
      (node (ref "IC3") (pin "A8") (pinfunction "DQ0_A8") (pintype "bidirectional"))
      (node (ref "IC8") (pin "E3") (pinfunction "GPIO_EMC_00_E3") (pintype "bidirectional"))
    )
    (net (code "115") (name "/SDRAM_DQ1") (class "Default")
      (node (ref "IC3") (pin "B9") (pinfunction "DQ1_B9") (pintype "bidirectional"))
      (node (ref "IC8") (pin "F3") (pinfunction "GPIO_EMC_01_F3") (pintype "bidirectional"))
    )
    (net (code "116") (name "/SDRAM_DQ2") (class "Default")
      (node (ref "IC3") (pin "B8") (pinfunction "DQ2_B8") (pintype "bidirectional"))
      (node (ref "IC8") (pin "F4") (pinfunction "GPIO_EMC_02_F4") (pintype "bidirectional"))
    )
    (net (code "117") (name "/SDRAM_DQ3") (class "Default")
      (node (ref "IC3") (pin "C9") (pinfunction "DQ3_C9") (pintype "bidirectional"))
      (node (ref "IC8") (pin "G4") (pinfunction "GPIO_EMC_03_G4") (pintype "bidirectional"))
    )
    (net (code "118") (name "/SDRAM_DQ4") (class "Default")
      (node (ref "IC3") (pin "C8") (pinfunction "DQ4_C8") (pintype "bidirectional"))
      (node (ref "IC8") (pin "F2") (pinfunction "GPIO_EMC_04_F2") (pintype "bidirectional"))
    )
    (net (code "119") (name "/SDRAM_DQ5") (class "Default")
      (node (ref "IC3") (pin "D9") (pinfunction "DQ5_D9") (pintype "bidirectional"))
      (node (ref "IC8") (pin "G5") (pinfunction "GPIO_EMC_05_G5") (pintype "bidirectional"))
    )
    (net (code "120") (name "/SDRAM_DQ6") (class "Default")
      (node (ref "IC3") (pin "D8") (pinfunction "DQ6_D8") (pintype "bidirectional"))
      (node (ref "IC8") (pin "H5") (pinfunction "GPIO_EMC_06_H5") (pintype "bidirectional"))
    )
    (net (code "121") (name "/SDRAM_DQ7") (class "Default")
      (node (ref "IC3") (pin "E9") (pinfunction "DQ7_E9") (pintype "bidirectional"))
      (node (ref "IC8") (pin "H4") (pinfunction "GPIO_EMC_07_H4") (pintype "bidirectional"))
    )
    (net (code "122") (name "/SDRAM_DQ8") (class "Default")
      (node (ref "IC3") (pin "E1") (pinfunction "DQ8_E1") (pintype "bidirectional"))
      (node (ref "IC8") (pin "C6") (pinfunction "GPIO_EMC_30_C6") (pintype "bidirectional"))
    )
    (net (code "123") (name "/SDRAM_DQ9") (class "Default")
      (node (ref "IC3") (pin "D2") (pinfunction "DQ9_D2") (pintype "bidirectional"))
      (node (ref "IC8") (pin "C5") (pinfunction "GPIO_EMC_31_C5") (pintype "bidirectional"))
    )
    (net (code "124") (name "/SDRAM_DQ10") (class "Default")
      (node (ref "IC3") (pin "D1") (pinfunction "DQ10_D1") (pintype "bidirectional"))
      (node (ref "IC8") (pin "D5") (pinfunction "GPIO_EMC_32_D5") (pintype "bidirectional"))
    )
    (net (code "125") (name "/SDRAM_DQ11") (class "Default")
      (node (ref "IC3") (pin "C2") (pinfunction "DQ11_C2") (pintype "bidirectional"))
      (node (ref "IC8") (pin "C4") (pinfunction "GPIO_EMC_33_C4") (pintype "bidirectional"))
    )
    (net (code "126") (name "/SDRAM_DQ12") (class "Default")
      (node (ref "IC3") (pin "C1") (pinfunction "DQ12_C1") (pintype "bidirectional"))
      (node (ref "IC8") (pin "D4") (pinfunction "GPIO_EMC_34_D4") (pintype "bidirectional"))
    )
    (net (code "127") (name "/SDRAM_DQ13") (class "Default")
      (node (ref "IC3") (pin "B2") (pinfunction "DQ13_B2") (pintype "bidirectional"))
      (node (ref "IC8") (pin "E5") (pinfunction "GPIO_EMC_35_E5") (pintype "bidirectional"))
    )
    (net (code "128") (name "/SDRAM_DQ14") (class "Default")
      (node (ref "IC3") (pin "B1") (pinfunction "DQ14_B1") (pintype "bidirectional"))
      (node (ref "IC8") (pin "C3") (pinfunction "GPIO_EMC_36_C3") (pintype "bidirectional"))
    )
    (net (code "129") (name "/SDRAM_DQ15") (class "Default")
      (node (ref "IC3") (pin "A2") (pinfunction "DQ15_A2") (pintype "bidirectional"))
      (node (ref "IC8") (pin "E4") (pinfunction "GPIO_EMC_37_E4") (pintype "bidirectional"))
    )
    (net (code "130") (name "/SDRAM_DQMH") (class "Default")
      (node (ref "IC3") (pin "F1") (pinfunction "DQMH_F1") (pintype "bidirectional"))
      (node (ref "IC8") (pin "D6") (pinfunction "GPIO_EMC_38_D6") (pintype "bidirectional"))
    )
    (net (code "131") (name "/SDRAM_DQML") (class "Default")
      (node (ref "IC3") (pin "E8") (pinfunction "DQML_E8") (pintype "bidirectional"))
      (node (ref "IC8") (pin "H3") (pinfunction "GPIO_EMC_08_H3") (pintype "bidirectional"))
    )
    (net (code "132") (name "/SDRAM_RAS") (class "Default")
      (node (ref "IC3") (pin "F8") (pinfunction "~{RAS}_F8") (pintype "bidirectional"))
      (node (ref "IC8") (pin "D2") (pinfunction "GPIO_EMC_25_D2") (pintype "bidirectional"))
    )
    (net (code "133") (name "/SDRAM_WE") (class "Default")
      (node (ref "IC3") (pin "F9") (pinfunction "~{WE}_F9") (pintype "bidirectional"))
      (node (ref "IC8") (pin "D1") (pinfunction "GPIO_EMC_28_D1") (pintype "bidirectional"))
    )
    (net (code "134") (name "/SD_CD") (class "Default")
      (node (ref "D9") (pin "1") (pinfunction "1_1") (pintype "bidirectional"))
      (node (ref "IC8") (pin "L11") (pinfunction "GPIO_AD_B1_02_L11") (pintype "bidirectional"))
      (node (ref "J5") (pin "CD$1") (pinfunction "CD_CD$1") (pintype "power_in"))
      (node (ref "RN1") (pin "9") (pinfunction "9_9") (pintype "bidirectional"))
    )
    (net (code "135") (name "/SD_CLK") (class "Default")
      (node (ref "FL3") (pin "4") (pinfunction "INPUT_4_4") (pintype "bidirectional"))
      (node (ref "IC8") (pin "J3") (pinfunction "GPIO_SD_B0_01_J3") (pintype "bidirectional"))
    )
    (net (code "136") (name "/SD_CLK_INT") (class "Default")
      (node (ref "FL3") (pin "9") (pinfunction "OUTPUT_4_9") (pintype "bidirectional"))
      (node (ref "J5") (pin "P$5") (pinfunction "CLK_P$5") (pintype "bidirectional"))
    )
    (net (code "137") (name "/SD_CMD") (class "Default")
      (node (ref "FL3") (pin "3") (pinfunction "INPUT_3_3") (pintype "bidirectional"))
      (node (ref "IC8") (pin "J4") (pinfunction "GPIO_SD_B0_00_J4") (pintype "bidirectional"))
      (node (ref "RN1") (pin "12") (pinfunction "12_12") (pintype "bidirectional"))
    )
    (net (code "138") (name "/SD_CMD_INT") (class "Default")
      (node (ref "FL3") (pin "10") (pinfunction "OUTPUT_3_10") (pintype "bidirectional"))
      (node (ref "J5") (pin "P$3") (pinfunction "CMD_P$3") (pintype "bidirectional"))
    )
    (net (code "139") (name "/SD_DAT0") (class "Default")
      (node (ref "FL3") (pin "5") (pinfunction "INPUT_5_5") (pintype "bidirectional"))
      (node (ref "IC8") (pin "J1") (pinfunction "GPIO_SD_B0_02_J1") (pintype "bidirectional"))
      (node (ref "RN1") (pin "14") (pinfunction "14_14") (pintype "bidirectional"))
    )
    (net (code "140") (name "/SD_DAT0_INT") (class "Default")
      (node (ref "FL3") (pin "8") (pinfunction "OUTPUT_5_8") (pintype "bidirectional"))
      (node (ref "J5") (pin "P$7") (pinfunction "DAT0_P$7") (pintype "bidirectional"))
    )
    (net (code "141") (name "/SD_DAT1") (class "Default")
      (node (ref "FL3") (pin "6") (pinfunction "INPUT_6_6") (pintype "bidirectional"))
      (node (ref "IC8") (pin "K1") (pinfunction "GPIO_SD_B0_03_K1") (pintype "bidirectional"))
      (node (ref "RN1") (pin "13") (pinfunction "13_13") (pintype "bidirectional"))
    )
    (net (code "142") (name "/SD_DAT1_INT") (class "Default")
      (node (ref "FL3") (pin "7") (pinfunction "OUTPUT_6_7") (pintype "bidirectional"))
      (node (ref "J5") (pin "P$8") (pinfunction "DAT1_P$8") (pintype "bidirectional"))
    )
    (net (code "143") (name "/SD_DAT2") (class "Default")
      (node (ref "FL3") (pin "1") (pinfunction "INPUT_1_1") (pintype "bidirectional"))
      (node (ref "IC8") (pin "H2") (pinfunction "GPIO_SD_B0_04_H2") (pintype "bidirectional"))
      (node (ref "RN1") (pin "10") (pinfunction "10_10") (pintype "bidirectional"))
    )
    (net (code "144") (name "/SD_DAT2_INT") (class "Default")
      (node (ref "FL3") (pin "12") (pinfunction "OUTPUT_1_12") (pintype "bidirectional"))
      (node (ref "J5") (pin "P$1") (pinfunction "DAT2_P$1") (pintype "bidirectional"))
    )
    (net (code "145") (name "/SD_DAT3") (class "Default")
      (node (ref "FL3") (pin "2") (pinfunction "INPUT_2_2") (pintype "bidirectional"))
      (node (ref "IC8") (pin "J2") (pinfunction "GPIO_SD_B0_05_J2") (pintype "bidirectional"))
      (node (ref "RN1") (pin "11") (pinfunction "11_11") (pintype "bidirectional"))
    )
    (net (code "146") (name "/SD_DAT3_INT") (class "Default")
      (node (ref "FL3") (pin "11") (pinfunction "OUTPUT_2_11") (pintype "bidirectional"))
      (node (ref "J5") (pin "P$2") (pinfunction "DAT3/CD_P$2") (pintype "bidirectional"))
    )
    (net (code "147") (name "/S_FLASH_CE") (class "Default")
      (node (ref "IC6") (pin "1") (pinfunction "CE#_1") (pintype "bidirectional"))
      (node (ref "IC8") (pin "N3") (pinfunction "GPIO_SD_B1_05_N3") (pintype "bidirectional"))
      (node (ref "R14") (pin "2") (pinfunction "2_2") (pintype "passive"))
    )
    (net (code "148") (name "/S_FLASH_IO0") (class "Default")
      (node (ref "IC6") (pin "5") (pinfunction "SI_(IO0)_5") (pintype "bidirectional"))
      (node (ref "IC8") (pin "M4") (pinfunction "GPIO_SD_B1_03_M4") (pintype "bidirectional"))
    )
    (net (code "149") (name "/S_FLASH_IO1") (class "Default")
      (node (ref "IC6") (pin "2") (pinfunction "SO_(IO1)_2") (pintype "bidirectional"))
      (node (ref "IC8") (pin "M3") (pinfunction "GPIO_SD_B1_02_M3") (pintype "bidirectional"))
    )
    (net (code "150") (name "/S_FLASH_IO2") (class "Default")
      (node (ref "IC6") (pin "3") (pinfunction "WP#_(IO2)_3") (pintype "bidirectional"))
      (node (ref "IC8") (pin "M5") (pinfunction "GPIO_SD_B1_01_M5") (pintype "bidirectional"))
    )
    (net (code "151") (name "/S_FLASH_IO3") (class "Default")
      (node (ref "IC6") (pin "7") (pinfunction "HOLD#_(IO3)_7") (pintype "bidirectional"))
      (node (ref "IC8") (pin "L5") (pinfunction "GPIO_SD_B1_00_L5") (pintype "bidirectional"))
    )
    (net (code "152") (name "/S_FLASH_SCK") (class "Default")
      (node (ref "IC6") (pin "6") (pinfunction "SCK_6") (pintype "bidirectional"))
      (node (ref "IC8") (pin "P2") (pinfunction "GPIO_SD_B1_04_P2") (pintype "bidirectional"))
    )
    (net (code "153") (name "/USB_D_N") (class "Default")
      (node (ref "FL1") (pin "6") (pinfunction "D+_2_6") (pintype "bidirectional"))
      (node (ref "IC8") (pin "M8") (pinfunction "USB_OTG1_DN_M8") (pintype "bidirectional"))
    )
    (net (code "154") (name "/USB_D_P") (class "Default")
      (node (ref "FL1") (pin "7") (pinfunction "D-_2_7") (pintype "bidirectional"))
      (node (ref "IC8") (pin "L8") (pinfunction "USB_OTG1_DP_L8") (pintype "bidirectional"))
    )
    (net (code "155") (name "/VCC_SOC") (class "Default")
      (node (ref "C100") (pin "2") (pinfunction "2_2") (pintype "passive"))
      (node (ref "C103") (pin "2") (pinfunction "2_2") (pintype "passive"))
      (node (ref "C34") (pin "1") (pinfunction "1_1") (pintype "passive"))
      (node (ref "C38") (pin "1") (pinfunction "1_1") (pintype "passive"))
      (node (ref "C45") (pin "1") (pinfunction "1_1") (pintype "passive"))
      (node (ref "C46") (pin "2") (pinfunction "2_2") (pintype "passive"))
      (node (ref "C47") (pin "1") (pinfunction "1_1") (pintype "passive"))
      (node (ref "C48") (pin "1") (pinfunction "1_1") (pintype "passive"))
      (node (ref "C49") (pin "2") (pinfunction "2_2") (pintype "passive"))
      (node (ref "C87") (pin "2") (pinfunction "2_2") (pintype "passive"))
      (node (ref "C94") (pin "2") (pinfunction "2_2") (pintype "passive"))
      (node (ref "C97") (pin "2") (pinfunction "2_2") (pintype "passive"))
      (node (ref "C98") (pin "2") (pinfunction "2_2") (pintype "passive"))
      (node (ref "IC8") (pin "F6") (pinfunction "VDD_SOC_IN_1_F6") (pintype "bidirectional"))
      (node (ref "IC8") (pin "F7") (pinfunction "VDD_SOC_IN_2_F7") (pintype "bidirectional"))
      (node (ref "IC8") (pin "F8") (pinfunction "VDD_SOC_IN_3_F8") (pintype "bidirectional"))
      (node (ref "IC8") (pin "F9") (pinfunction "VDD_SOC_IN_4_F9") (pintype "bidirectional"))
      (node (ref "IC8") (pin "G6") (pinfunction "VDD_SOC_IN_5_G6") (pintype "bidirectional"))
      (node (ref "IC8") (pin "G9") (pinfunction "VDD_SOC_IN_6_G9") (pintype "bidirectional"))
      (node (ref "IC8") (pin "H6") (pinfunction "VDD_SOC_IN_7_H6") (pintype "bidirectional"))
      (node (ref "IC8") (pin "H9") (pinfunction "VDD_SOC_IN_8_H9") (pintype "bidirectional"))
      (node (ref "IC8") (pin "J5") (pinfunction "DCDC_SENSE_J5") (pintype "bidirectional"))
      (node (ref "IC8") (pin "J9") (pinfunction "VDD_SOC_IN_9_J9") (pintype "bidirectional"))
      (node (ref "L5") (pin "1") (pinfunction "1_1") (pintype "passive"))
    )
    (net (code "156") (name "/VDDA") (class "Default")
      (node (ref "C51") (pin "1") (pinfunction "1_1") (pintype "passive"))
      (node (ref "C52") (pin "2") (pinfunction "2_2") (pintype "passive"))
      (node (ref "J4") (pin "4") (pinfunction "4_4") (pintype "bidirectional"))
      (node (ref "L4") (pin "1") (pinfunction "1_1") (pintype "passive"))
    )
    (net (code "157") (name "/VDDA_ADC_3P3") (class "Default")
      (node (ref "C59") (pin "1") (pinfunction "1_1") (pintype "passive"))
      (node (ref "C60") (pin "2") (pinfunction "2_2") (pintype "passive"))
      (node (ref "C61") (pin "2") (pinfunction "2_2") (pintype "passive"))
      (node (ref "IC8") (pin "N14") (pinfunction "VDDA_ADC_3P3_N14") (pintype "bidirectional"))
      (node (ref "L6") (pin "1") (pinfunction "1_1") (pintype "passive"))
    )
    (net (code "158") (name "/VDD_HIGH_CAP") (class "Default")
      (node (ref "C101") (pin "2") (pinfunction "2_2") (pintype "passive"))
      (node (ref "C102") (pin "1") (pinfunction "1_1") (pintype "passive"))
      (node (ref "IC8") (pin "P8") (pinfunction "VDD_HIGH_CAP_P8") (pintype "bidirectional"))
    )
    (net (code "159") (name "/VDD_SNVS") (class "Default")
      (node (ref "C2") (pin "2") (pinfunction "2_2") (pintype "passive"))
      (node (ref "C69") (pin "1") (pinfunction "1_1") (pintype "passive"))
      (node (ref "IC8") (pin "M9") (pinfunction "VDD_SNVS_IN_M9") (pintype "bidirectional"))
      (node (ref "U1") (pin "1") (pinfunction "VOUT_1") (pintype "bidirectional"))
    )
    (net (code "160") (name "/VDD_SNVS_CAP") (class "Default")
      (node (ref "C70") (pin "1") (pinfunction "1_1") (pintype "passive"))
      (node (ref "IC8") (pin "M10") (pinfunction "VDD_SNVS_CAP_M10") (pintype "bidirectional"))
    )
    (net (code "161") (name "/VDD_USB_CAP") (class "Default")
      (node (ref "C71") (pin "1") (pinfunction "1_1") (pintype "passive"))
      (node (ref "C72") (pin "2") (pinfunction "2_2") (pintype "passive"))
      (node (ref "C73") (pin "2") (pinfunction "2_2") (pintype "passive"))
      (node (ref "IC8") (pin "K8") (pinfunction "VDD_USB_CAP_K8") (pintype "bidirectional"))
    )
    (net (code "162") (name "/WAKEUP") (class "Default")
      (node (ref "IC8") (pin "L6") (pinfunction "WAKEUP_L6") (pintype "bidirectional"))
      (node (ref "Q2") (pin "2") (pinfunction "S_2") (pintype "bidirectional"))
    )
    (net (code "163") (name "/WIFI_CLK") (class "Default")
      (node (ref "IC8") (pin "M13") (pinfunction "GPIO_AD_B1_09_M13") (pintype "bidirectional"))
      (node (ref "U3") (pin "20") (pinfunction "SDIO_CLK_20") (pintype "input"))
    )
    (net (code "164") (name "/WIFI_CMD") (class "Default")
      (node (ref "IC8") (pin "H13") (pinfunction "GPIO_AD_B1_08_H13") (pintype "bidirectional"))
      (node (ref "RN2") (pin "16") (pinfunction "16_16") (pintype "bidirectional"))
      (node (ref "U3") (pin "22") (pinfunction "SDIO_CMD_22") (pintype "bidirectional"))
    )
    (net (code "165") (name "/WIFI_D0") (class "Default")
      (node (ref "IC8") (pin "L12") (pinfunction "GPIO_AD_B1_04_L12") (pintype "bidirectional"))
      (node (ref "RN2") (pin "14") (pinfunction "14_14") (pintype "bidirectional"))
      (node (ref "U3") (pin "24") (pinfunction "SDIO_DATA_0_24") (pintype "bidirectional"))
    )
    (net (code "166") (name "/WIFI_D1") (class "Default")
      (node (ref "IC8") (pin "K12") (pinfunction "GPIO_AD_B1_05_K12") (pintype "bidirectional"))
      (node (ref "RN2") (pin "12") (pinfunction "12_12") (pintype "bidirectional"))
      (node (ref "U3") (pin "26") (pinfunction "SDIO_DATA_1_26") (pintype "bidirectional"))
    )
    (net (code "167") (name "/WIFI_D2") (class "Default")
      (node (ref "IC8") (pin "J12") (pinfunction "GPIO_AD_B1_06_J12") (pintype "bidirectional"))
      (node (ref "RN2") (pin "15") (pinfunction "15_15") (pintype "bidirectional"))
      (node (ref "U3") (pin "23") (pinfunction "SDIO_DATA_2_23") (pintype "bidirectional"))
    )
    (net (code "168") (name "/WIFI_D3") (class "Default")
      (node (ref "IC8") (pin "K10") (pinfunction "GPIO_AD_B1_07_K10") (pintype "bidirectional"))
      (node (ref "RN2") (pin "13") (pinfunction "13_13") (pintype "bidirectional"))
      (node (ref "U3") (pin "25") (pinfunction "SDIO_DATA_3_25") (pintype "bidirectional"))
    )
    (net (code "169") (name "/WL_H_WAKE") (class "Default")
      (node (ref "IC8") (pin "E11") (pinfunction "GPIO_B0_15_E11") (pintype "bidirectional"))
      (node (ref "U3") (pin "27") (pinfunction "WL_GPIO_0_HOST_WAKE_27") (pintype "bidirectional"))
    )
    (net (code "170") (name "/WL_REG_ON") (class "Default")
      (node (ref "IC8") (pin "E10") (pinfunction "GPIO_B0_14_E10") (pintype "bidirectional"))
      (node (ref "U3") (pin "28") (pinfunction "WL_REG_ON_28") (pintype "input"))
    )
    (net (code "171") (name "/XTALI") (class "Default")
      (node (ref "C106") (pin "1") (pinfunction "1_1") (pintype "passive"))
      (node (ref "IC8") (pin "P11") (pinfunction "XTALI_P11") (pintype "bidirectional"))
      (node (ref "R40") (pin "1") (pinfunction "1_1") (pintype "passive"))
      (node (ref "Y2") (pin "3") (pinfunction "CRYSTAL_2_3") (pintype "bidirectional"))
    )
    (net (code "172") (name "/XTALO") (class "Default")
      (node (ref "C105") (pin "1") (pinfunction "1_1") (pintype "passive"))
      (node (ref "IC8") (pin "N11") (pinfunction "XTALO_N11") (pintype "bidirectional"))
      (node (ref "Y2") (pin "1") (pinfunction "CRYSTAL_1_1") (pintype "bidirectional"))
    )
    (net (code "173") (name "GND") (class "Default")
      (node (ref "C1") (pin "1") (pinfunction "1_1") (pintype "passive"))
      (node (ref "C10") (pin "1") (pinfunction "1_1") (pintype "passive"))
      (node (ref "C100") (pin "1") (pinfunction "1_1") (pintype "passive"))
      (node (ref "C101") (pin "1") (pinfunction "1_1") (pintype "passive"))
      (node (ref "C102") (pin "2") (pinfunction "2_2") (pintype "passive"))
      (node (ref "C103") (pin "1") (pinfunction "1_1") (pintype "passive"))
      (node (ref "C104") (pin "1") (pinfunction "1_1") (pintype "passive"))
      (node (ref "C105") (pin "2") (pinfunction "2_2") (pintype "passive"))
      (node (ref "C106") (pin "2") (pinfunction "2_2") (pintype "passive"))
      (node (ref "C107") (pin "2") (pinfunction "2_2") (pintype "passive"))
      (node (ref "C108") (pin "1") (pinfunction "1_1") (pintype "passive"))
      (node (ref "C109") (pin "2") (pinfunction "2_2") (pintype "passive"))
      (node (ref "C11") (pin "1") (pinfunction "1_1") (pintype "passive"))
      (node (ref "C110") (pin "1") (pinfunction "1_1") (pintype "passive"))
      (node (ref "C12") (pin "2") (pinfunction "2_2") (pintype "passive"))
      (node (ref "C13") (pin "2") (pinfunction "2_2") (pintype "passive"))
      (node (ref "C14") (pin "2") (pinfunction "2_2") (pintype "passive"))
      (node (ref "C15") (pin "2") (pinfunction "2_2") (pintype "passive"))
      (node (ref "C16") (pin "2") (pinfunction "2_2") (pintype "passive"))
      (node (ref "C17") (pin "1") (pinfunction "1_1") (pintype "passive"))
      (node (ref "C18") (pin "1") (pinfunction "1_1") (pintype "passive"))
      (node (ref "C19") (pin "2") (pinfunction "2_2") (pintype "passive"))
      (node (ref "C2") (pin "1") (pinfunction "1_1") (pintype "passive"))
      (node (ref "C20") (pin "2") (pinfunction "2_2") (pintype "passive"))
      (node (ref "C21") (pin "1") (pinfunction "1_1") (pintype "passive"))
      (node (ref "C22") (pin "2") (pinfunction "2_2") (pintype "passive"))
      (node (ref "C23") (pin "1") (pinfunction "1_1") (pintype "passive"))
      (node (ref "C24") (pin "2") (pinfunction "2_2") (pintype "passive"))
      (node (ref "C25") (pin "1") (pinfunction "1_1") (pintype "passive"))
      (node (ref "C26") (pin "2") (pinfunction "2_2") (pintype "passive"))
      (node (ref "C27") (pin "1") (pinfunction "1_1") (pintype "passive"))
      (node (ref "C28") (pin "2") (pinfunction "2_2") (pintype "passive"))
      (node (ref "C29") (pin "2") (pinfunction "2_2") (pintype "passive"))
      (node (ref "C3") (pin "1") (pinfunction "1_1") (pintype "passive"))
      (node (ref "C30") (pin "2") (pinfunction "2_2") (pintype "passive"))
      (node (ref "C31") (pin "1") (pinfunction "1_1") (pintype "passive"))
      (node (ref "C32") (pin "2") (pinfunction "2_2") (pintype "passive"))
      (node (ref "C33") (pin "1") (pinfunction "1_1") (pintype "passive"))
      (node (ref "C34") (pin "2") (pinfunction "2_2") (pintype "passive"))
      (node (ref "C35") (pin "1") (pinfunction "1_1") (pintype "passive"))
      (node (ref "C36") (pin "2") (pinfunction "2_2") (pintype "passive"))
      (node (ref "C37") (pin "2") (pinfunction "2_2") (pintype "passive"))
      (node (ref "C38") (pin "2") (pinfunction "2_2") (pintype "passive"))
      (node (ref "C39") (pin "1") (pinfunction "1_1") (pintype "passive"))
      (node (ref "C4") (pin "1") (pinfunction "1_1") (pintype "passive"))
      (node (ref "C40") (pin "1") (pinfunction "1_1") (pintype "passive"))
      (node (ref "C41") (pin "1") (pinfunction "1_1") (pintype "passive"))
      (node (ref "C42") (pin "1") (pinfunction "1_1") (pintype "passive"))
      (node (ref "C43") (pin "2") (pinfunction "2_2") (pintype "passive"))
      (node (ref "C44") (pin "1") (pinfunction "1_1") (pintype "passive"))
      (node (ref "C45") (pin "2") (pinfunction "2_2") (pintype "passive"))
      (node (ref "C46") (pin "1") (pinfunction "1_1") (pintype "passive"))
      (node (ref "C47") (pin "2") (pinfunction "2_2") (pintype "passive"))
      (node (ref "C48") (pin "2") (pinfunction "2_2") (pintype "passive"))
      (node (ref "C49") (pin "1") (pinfunction "1_1") (pintype "passive"))
      (node (ref "C5") (pin "1") (pinfunction "1_1") (pintype "passive"))
      (node (ref "C50") (pin "2") (pinfunction "2_2") (pintype "passive"))
      (node (ref "C51") (pin "2") (pinfunction "2_2") (pintype "passive"))
      (node (ref "C52") (pin "1") (pinfunction "1_1") (pintype "passive"))
      (node (ref "C53") (pin "2") (pinfunction "2_2") (pintype "passive"))
      (node (ref "C54") (pin "2") (pinfunction "2_2") (pintype "passive"))
      (node (ref "C55") (pin "2") (pinfunction "2_2") (pintype "passive"))
      (node (ref "C56") (pin "2") (pinfunction "2_2") (pintype "passive"))
      (node (ref "C57") (pin "1") (pinfunction "1_1") (pintype "passive"))
      (node (ref "C58") (pin "1") (pinfunction "1_1") (pintype "passive"))
      (node (ref "C59") (pin "2") (pinfunction "2_2") (pintype "passive"))
      (node (ref "C6") (pin "2") (pinfunction "2_2") (pintype "passive"))
      (node (ref "C60") (pin "1") (pinfunction "1_1") (pintype "passive"))
      (node (ref "C61") (pin "1") (pinfunction "1_1") (pintype "passive"))
      (node (ref "C62") (pin "2") (pinfunction "2_2") (pintype "passive"))
      (node (ref "C63") (pin "2") (pinfunction "2_2") (pintype "passive"))
      (node (ref "C64") (pin "2") (pinfunction "2_2") (pintype "passive"))
      (node (ref "C65") (pin "1") (pinfunction "1_1") (pintype "passive"))
      (node (ref "C66") (pin "1") (pinfunction "1_1") (pintype "passive"))
      (node (ref "C67") (pin "2") (pinfunction "2_2") (pintype "passive"))
      (node (ref "C68") (pin "1") (pinfunction "1_1") (pintype "passive"))
      (node (ref "C69") (pin "2") (pinfunction "2_2") (pintype "passive"))
      (node (ref "C7") (pin "2") (pinfunction "2_2") (pintype "passive"))
      (node (ref "C70") (pin "2") (pinfunction "2_2") (pintype "passive"))
      (node (ref "C71") (pin "2") (pinfunction "2_2") (pintype "passive"))
      (node (ref "C72") (pin "1") (pinfunction "1_1") (pintype "passive"))
      (node (ref "C73") (pin "1") (pinfunction "1_1") (pintype "passive"))
      (node (ref "C74") (pin "2") (pinfunction "2_2") (pintype "passive"))
      (node (ref "C75") (pin "2") (pinfunction "2_2") (pintype "passive"))
      (node (ref "C76") (pin "2") (pinfunction "2_2") (pintype "passive"))
      (node (ref "C77") (pin "2") (pinfunction "2_2") (pintype "bidirectional"))
      (node (ref "C78") (pin "2") (pinfunction "2_2") (pintype "bidirectional"))
      (node (ref "C79") (pin "2") (pinfunction "2_2") (pintype "passive"))
      (node (ref "C8") (pin "1") (pinfunction "1_1") (pintype "passive"))
      (node (ref "C80") (pin "2") (pinfunction "2_2") (pintype "passive"))
      (node (ref "C81") (pin "1") (pinfunction "1_1") (pintype "passive"))
      (node (ref "C82") (pin "2") (pinfunction "2_2") (pintype "passive"))
      (node (ref "C83") (pin "1") (pinfunction "1_1") (pintype "passive"))
      (node (ref "C84") (pin "2") (pinfunction "2_2") (pintype "passive"))
      (node (ref "C85") (pin "2") (pinfunction "2_2") (pintype "passive"))
      (node (ref "C86") (pin "1") (pinfunction "1_1") (pintype "passive"))
      (node (ref "C87") (pin "1") (pinfunction "1_1") (pintype "passive"))
      (node (ref "C88") (pin "2") (pinfunction "2_2") (pintype "passive"))
      (node (ref "C89") (pin "2") (pinfunction "2_2") (pintype "passive"))
      (node (ref "C9") (pin "1") (pinfunction "1_1") (pintype "passive"))
      (node (ref "C90") (pin "1") (pinfunction "1_1") (pintype "passive"))
      (node (ref "C91") (pin "1") (pinfunction "1_1") (pintype "passive"))
      (node (ref "C92") (pin "1") (pinfunction "1_1") (pintype "passive"))
      (node (ref "C93") (pin "1") (pinfunction "1_1") (pintype "passive"))
      (node (ref "C94") (pin "1") (pinfunction "1_1") (pintype "passive"))
      (node (ref "C95") (pin "1") (pinfunction "1_1") (pintype "passive"))
      (node (ref "C96") (pin "2") (pinfunction "2_2") (pintype "passive"))
      (node (ref "C97") (pin "1") (pinfunction "1_1") (pintype "passive"))
      (node (ref "C98") (pin "1") (pinfunction "1_1") (pintype "passive"))
      (node (ref "C99") (pin "1") (pinfunction "1_1") (pintype "passive"))
      (node (ref "CN1") (pin "2") (pinfunction "1_2") (pintype "passive"))
      (node (ref "D10") (pin "2") (pinfunction "2_2") (pintype "bidirectional"))
      (node (ref "D2") (pin "2") (pinfunction "2_2") (pintype "bidirectional"))
      (node (ref "D4") (pin "2") (pinfunction "2_2") (pintype "bidirectional"))
      (node (ref "D5") (pin "2") (pinfunction "2_2") (pintype "bidirectional"))
      (node (ref "D6") (pin "2") (pinfunction "2_2") (pintype "bidirectional"))
      (node (ref "D7") (pin "2") (pinfunction "2_2") (pintype "bidirectional"))
      (node (ref "D8") (pin "2") (pinfunction "2_2") (pintype "bidirectional"))
      (node (ref "D9") (pin "2") (pinfunction "2_2") (pintype "bidirectional"))
      (node (ref "FL1") (pin "5") (pinfunction "GND_1_5") (pintype "bidirectional"))
      (node (ref "FL1") (pin "8") (pinfunction "GND_2_8") (pintype "bidirectional"))
      (node (ref "FL2") (pin "13") (pinfunction "EP_13") (pintype "bidirectional"))
      (node (ref "FL3") (pin "13") (pinfunction "EP_13") (pintype "bidirectional"))
      (node (ref "FL4") (pin "13") (pinfunction "EP_13") (pintype "bidirectional"))
      (node (ref "FL5") (pin "13") (pinfunction "EP_13") (pintype "bidirectional"))
      (node (ref "IC1") (pin "1") (pinfunction "GND_1_1") (pintype "bidirectional"))
      (node (ref "IC1") (pin "4") (pinfunction "~{ON}_4") (pintype "bidirectional"))
      (node (ref "IC1") (pin "5") (pinfunction "GND_2_5") (pintype "bidirectional"))
      (node (ref "IC2") (pin "2") (pinfunction "GND_2") (pintype "bidirectional"))
      (node (ref "IC3") (pin "A1") (pinfunction "VSS_1_A1") (pintype "bidirectional"))
      (node (ref "IC3") (pin "A3") (pinfunction "VSSQ_1_A3") (pintype "bidirectional"))
      (node (ref "IC3") (pin "B7") (pinfunction "VSSQ_2_B7") (pintype "bidirectional"))
      (node (ref "IC3") (pin "C3") (pinfunction "VSSQ_3_C3") (pintype "bidirectional"))
      (node (ref "IC3") (pin "D7") (pinfunction "VSSQ_4_D7") (pintype "bidirectional"))
      (node (ref "IC3") (pin "E3") (pinfunction "VSS_2_E3") (pintype "bidirectional"))
      (node (ref "IC3") (pin "J1") (pinfunction "VSS_3_J1") (pintype "bidirectional"))
      (node (ref "IC4") (pin "4") (pinfunction "GND_4") (pintype "bidirectional"))
      (node (ref "IC4") (pin "9") (pinfunction "EP_9") (pintype "bidirectional"))
      (node (ref "IC5") (pin "4") (pinfunction "GND_4") (pintype "bidirectional"))
      (node (ref "IC5") (pin "9") (pinfunction "EP_9") (pintype "bidirectional"))
      (node (ref "IC6") (pin "4") (pinfunction "GND_4") (pintype "bidirectional"))
      (node (ref "IC6") (pin "9") (pinfunction "EP_9") (pintype "bidirectional"))
      (node (ref "IC7") (pin "3") (pinfunction "GND_3") (pintype "bidirectional"))
      (node (ref "IC8") (pin "A1") (pinfunction "VSS_1_A1") (pintype "bidirectional"))
      (node (ref "IC8") (pin "A14") (pinfunction "VSS_2_A14") (pintype "bidirectional"))
      (node (ref "IC8") (pin "B10") (pinfunction "VSS_4_B10") (pintype "bidirectional"))
      (node (ref "IC8") (pin "B5") (pinfunction "VSS_3_B5") (pintype "bidirectional"))
      (node (ref "IC8") (pin "E13") (pinfunction "VSS_6_E13") (pintype "bidirectional"))
      (node (ref "IC8") (pin "E2") (pinfunction "VSS_5_E2") (pintype "bidirectional"))
      (node (ref "IC8") (pin "G7") (pinfunction "VSS_7_G7") (pintype "bidirectional"))
      (node (ref "IC8") (pin "G8") (pinfunction "VSS_8_G8") (pintype "bidirectional"))
      (node (ref "IC8") (pin "H7") (pinfunction "VSS_9_H7") (pintype "bidirectional"))
      (node (ref "IC8") (pin "H8") (pinfunction "VSS_10_H8") (pintype "bidirectional"))
      (node (ref "IC8") (pin "J7") (pinfunction "VSS_11_J7") (pintype "bidirectional"))
      (node (ref "IC8") (pin "J8") (pinfunction "VSS_12_J8") (pintype "bidirectional"))
      (node (ref "IC8") (pin "K13") (pinfunction "VSS_14_K13") (pintype "bidirectional"))
      (node (ref "IC8") (pin "K2") (pinfunction "VSS_13_K2") (pintype "bidirectional"))
      (node (ref "IC8") (pin "K6") (pinfunction "TEST_MODE_K6") (pintype "bidirectional"))
      (node (ref "IC8") (pin "K9") (pinfunction "NGND_KEL0_K9") (pintype "bidirectional"))
      (node (ref "IC8") (pin "L9") (pinfunction "VSS_15_L9") (pintype "bidirectional"))
      (node (ref "IC8") (pin "N1") (pinfunction "DCDC_GND_1_N1") (pintype "bidirectional"))
      (node (ref "IC8") (pin "N2") (pinfunction "DCDC_GND_2_N2") (pintype "bidirectional"))
      (node (ref "IC8") (pin "N5") (pinfunction "VSS_16_N5") (pintype "bidirectional"))
      (node (ref "IC8") (pin "N8") (pinfunction "VSS_17_N8") (pintype "bidirectional"))
      (node (ref "IC8") (pin "P1") (pinfunction "VSS_18_P1") (pintype "bidirectional"))
      (node (ref "IC8") (pin "P14") (pinfunction "VSS_19_P14") (pintype "bidirectional"))
      (node (ref "IC9") (pin "22") (pinfunction "GND_1_22") (pintype "bidirectional"))
      (node (ref "IC9") (pin "25") (pinfunction "GND_2_25") (pintype "bidirectional"))
      (node (ref "J1") (pin "A1_B12") (pinfunction "GND_A1_B12") (pintype "power_in"))
      (node (ref "J1") (pin "B1_A12") (pinfunction "GND_B1_A12") (pintype "power_in"))
      (node (ref "J3") (pin "1") (pinfunction "1_1") (pintype "passive"))
      (node (ref "J4") (pin "19") (pinfunction "19_19") (pintype "bidirectional"))
      (node (ref "J4") (pin "27") (pinfunction "27_27") (pintype "bidirectional"))
      (node (ref "J4") (pin "5") (pinfunction "5_5") (pintype "bidirectional"))
      (node (ref "J5") (pin "CD$2") (pinfunction "CD_POL_CD$2") (pintype "power_in"))
      (node (ref "J5") (pin "G$1") (pinfunction "SHD_G$1") (pintype "power_in"))
      (node (ref "J5") (pin "G$2") (pinfunction "SHD_G$2") (pintype "power_in"))
      (node (ref "J5") (pin "G$3") (pinfunction "SHD_G$3") (pintype "power_in"))
      (node (ref "J5") (pin "G$4") (pinfunction "SHD_G$4") (pintype "power_in"))
      (node (ref "J5") (pin "P$6") (pinfunction "VSS_P$6") (pintype "power_in"))
      (node (ref "J6") (pin "1") (pinfunction "1_1") (pintype "passive"))
      (node (ref "J7") (pin "2") (pinfunction "GND_1_2") (pintype "bidirectional"))
      (node (ref "J7") (pin "3") (pinfunction "GND_2_3") (pintype "bidirectional"))
      (node (ref "J8") (pin "3") (pinfunction "3_3") (pintype "passive"))
      (node (ref "J8") (pin "5") (pinfunction "5_5") (pintype "passive"))
      (node (ref "Q6") (pin "1") (pinfunction "G_1") (pintype "bidirectional"))
      (node (ref "R10") (pin "2") (pinfunction "2_2") (pintype "passive"))
      (node (ref "R11") (pin "2") (pinfunction "2_2") (pintype "passive"))
      (node (ref "R12") (pin "2") (pinfunction "2_2") (pintype "passive"))
      (node (ref "R27") (pin "2") (pinfunction "2_2") (pintype "passive"))
      (node (ref "R37") (pin "2") (pinfunction "2_2") (pintype "passive"))
      (node (ref "R38") (pin "2") (pinfunction "2_2") (pintype "passive"))
      (node (ref "R40") (pin "2") (pinfunction "2_2") (pintype "passive"))
      (node (ref "R41") (pin "2") (pinfunction "2_2") (pintype "passive"))
      (node (ref "R6") (pin "2") (pinfunction "2_2") (pintype "passive"))
      (node (ref "R7") (pin "2") (pinfunction "2_2") (pintype "passive"))
      (node (ref "R8") (pin "1") (pinfunction "1_1") (pintype "passive"))
      (node (ref "R9") (pin "2") (pinfunction "2_2") (pintype "passive"))
      (node (ref "U1") (pin "2") (pinfunction "GND_2") (pintype "bidirectional"))
      (node (ref "U1") (pin "EP") (pinfunction "GND_EP") (pintype "bidirectional"))
      (node (ref "U2") (pin "15") (pinfunction "SYSOFF_15") (pintype "input"))
      (node (ref "U2") (pin "17") (pinfunction "EXP_17") (pintype "power_in"))
      (node (ref "U2") (pin "4") (pinfunction "~{CE}_4") (pintype "input"))
      (node (ref "U2") (pin "6") (pinfunction "EN1_6") (pintype "input"))
      (node (ref "U2") (pin "8") (pinfunction "VSS_8") (pintype "power_in"))
      (node (ref "U3") (pin "1") (pinfunction "GND_1") (pintype "power_in"))
      (node (ref "U3") (pin "12") (pinfunction "GND_12") (pintype "power_in"))
      (node (ref "U3") (pin "19") (pinfunction "GND_19") (pintype "power_in"))
      (node (ref "U3") (pin "21") (pinfunction "GND_21") (pintype "power_in"))
      (node (ref "U3") (pin "29") (pinfunction "GND_29") (pintype "power_in"))
      (node (ref "U3") (pin "32") (pinfunction "GND_(SR_PVSS)_32") (pintype "power_in"))
      (node (ref "U3") (pin "33") (pinfunction "GND_(SR_PVSS)_33") (pintype "power_in"))
      (node (ref "U3") (pin "35") (pinfunction "GND_35") (pintype "power_in"))
      (node (ref "U3") (pin "37") (pinfunction "LPO_IN_(32KHZ)_37") (pintype "input"))
      (node (ref "U3") (pin "4") (pinfunction "~{BT_UART_CTS_N}_4") (pintype "input"))
      (node (ref "U3") (pin "40") (pinfunction "GND_40") (pintype "power_in"))
      (node (ref "U3") (pin "42") (pinfunction "GND_42") (pintype "power_in"))
      (node (ref "U3") (pin "43") (pinfunction "GND_43") (pintype "power_in"))
      (node (ref "U3") (pin "44") (pinfunction "GND_44") (pintype "power_in"))
      (node (ref "U3") (pin "45") (pinfunction "GND_45") (pintype "power_in"))
      (node (ref "U3") (pin "46") (pinfunction "GND_46") (pintype "power_in"))
      (node (ref "Y2") (pin "2") (pinfunction "NC_1_2") (pintype "bidirectional"))
      (node (ref "Y2") (pin "4") (pinfunction "NC_2_4") (pintype "bidirectional"))
    )
    (net (code "174") (name "Net-(ANT1-FEED)") (class "Default")
      (node (ref "ANT1") (pin "1") (pinfunction "FEED_1") (pintype "input"))
      (node (ref "C78") (pin "1") (pinfunction "1_1") (pintype "bidirectional"))
      (node (ref "L7") (pin "1") (pinfunction "1_1") (pintype "passive"))
    )
    (net (code "175") (name "Net-(C110-Pad2)") (class "Default")
      (node (ref "C110") (pin "2") (pinfunction "2_2") (pintype "passive"))
      (node (ref "J1") (pin "S1") (pinfunction "SHELL_GND_S1") (pintype "power_in"))
      (node (ref "J1") (pin "S2") (pinfunction "SHELL_GND_S2") (pintype "power_in"))
      (node (ref "J1") (pin "S3") (pinfunction "SHELL_GND_S3") (pintype "power_in"))
      (node (ref "J1") (pin "S4") (pinfunction "SHELL_GND_S4") (pintype "power_in"))
      (node (ref "R41") (pin "1") (pinfunction "1_1") (pintype "passive"))
    )
    (net (code "176") (name "Net-(CN1-2)") (class "Default")
      (node (ref "C8") (pin "2") (pinfunction "2_2") (pintype "passive"))
      (node (ref "CN1") (pin "1") (pinfunction "2_1") (pintype "passive"))
      (node (ref "D2") (pin "1") (pinfunction "1_1") (pintype "bidirectional"))
      (node (ref "U2") (pin "2") (pinfunction "BAT_2_2") (pintype "bidirectional"))
      (node (ref "U2") (pin "3") (pinfunction "BAT_3_3") (pintype "bidirectional"))
    )
    (net (code "177") (name "Net-(D1-BLUE)") (class "Default")
      (node (ref "D1") (pin "1") (pinfunction "BLUE_1") (pintype "passive"))
      (node (ref "R5") (pin "2") (pinfunction "2_2") (pintype "passive"))
    )
    (net (code "178") (name "Net-(D3-BLUE)") (class "Default")
      (node (ref "D3") (pin "1") (pinfunction "BLUE_1") (pintype "passive"))
      (node (ref "R19") (pin "2") (pinfunction "2_2") (pintype "passive"))
    )
    (net (code "179") (name "Net-(D3-GREEN)") (class "Default")
      (node (ref "D3") (pin "2") (pinfunction "GREEN_2") (pintype "passive"))
      (node (ref "R20") (pin "2") (pinfunction "2_2") (pintype "passive"))
    )
    (net (code "180") (name "Net-(D3-RED)") (class "Default")
      (node (ref "D3") (pin "3") (pinfunction "RED_3") (pintype "passive"))
      (node (ref "R21") (pin "2") (pinfunction "2_2") (pintype "passive"))
    )
    (net (code "181") (name "Net-(FL1-D+_1)") (class "Default")
      (node (ref "FL1") (pin "3") (pinfunction "D+_1_3") (pintype "bidirectional"))
      (node (ref "J1") (pin "A7") (pinfunction "DN1_A7") (pintype "bidirectional"))
      (node (ref "J1") (pin "B7") (pinfunction "DN2_B7") (pintype "bidirectional"))
    )
    (net (code "182") (name "Net-(FL1-D-_1)") (class "Default")
      (node (ref "FL1") (pin "2") (pinfunction "D-_1_2") (pintype "bidirectional"))
      (node (ref "J1") (pin "A6") (pinfunction "DP1_A6") (pintype "bidirectional"))
      (node (ref "J1") (pin "B6") (pinfunction "DP2_B6") (pintype "bidirectional"))
    )
    (net (code "183") (name "Net-(FL1-ID)") (class "Default")
      (node (ref "FL1") (pin "4") (pinfunction "ID_4") (pintype "bidirectional"))
      (node (ref "J1") (pin "A4_B9") (pinfunction "VBUS_A4_B9") (pintype "power_in"))
      (node (ref "J1") (pin "B4_A9") (pinfunction "VBUS_B4_A9") (pintype "power_in"))
      (node (ref "L1") (pin "1") (pinfunction "1_1") (pintype "passive"))
    )
    (net (code "184") (name "Net-(FL2-OUTPUT_1)") (class "Default")
      (node (ref "FL2") (pin "12") (pinfunction "OUTPUT_1_12") (pintype "bidirectional"))
      (node (ref "J2") (pin "8") (pinfunction "8_8") (pintype "passive"))
    )
    (net (code "185") (name "Net-(FL2-OUTPUT_2)") (class "Default")
      (node (ref "FL2") (pin "11") (pinfunction "OUTPUT_2_11") (pintype "bidirectional"))
      (node (ref "J2") (pin "7") (pinfunction "7_7") (pintype "passive"))
    )
    (net (code "186") (name "Net-(FL2-OUTPUT_3)") (class "Default")
      (node (ref "FL2") (pin "10") (pinfunction "OUTPUT_3_10") (pintype "bidirectional"))
      (node (ref "J2") (pin "6") (pinfunction "6_6") (pintype "passive"))
    )
    (net (code "187") (name "Net-(FL2-OUTPUT_4)") (class "Default")
      (node (ref "FL2") (pin "9") (pinfunction "OUTPUT_4_9") (pintype "bidirectional"))
      (node (ref "J2") (pin "5") (pinfunction "5_5") (pintype "passive"))
    )
    (net (code "188") (name "Net-(FL2-OUTPUT_5)") (class "Default")
      (node (ref "FL2") (pin "8") (pinfunction "OUTPUT_5_8") (pintype "bidirectional"))
      (node (ref "J2") (pin "4") (pinfunction "4_4") (pintype "passive"))
    )
    (net (code "189") (name "Net-(FL2-OUTPUT_6)") (class "Default")
      (node (ref "FL2") (pin "7") (pinfunction "OUTPUT_6_7") (pintype "bidirectional"))
      (node (ref "J2") (pin "3") (pinfunction "3_3") (pintype "passive"))
    )
    (net (code "190") (name "Net-(FL4-OUTPUT_1)") (class "Default")
      (node (ref "FL4") (pin "12") (pinfunction "OUTPUT_1_12") (pintype "bidirectional"))
      (node (ref "J2") (pin "2") (pinfunction "2_2") (pintype "passive"))
    )
    (net (code "191") (name "Net-(FL5-OUTPUT_6)") (class "Default")
      (node (ref "FL5") (pin "7") (pinfunction "OUTPUT_6_7") (pintype "bidirectional"))
      (node (ref "J8") (pin "9") (pinfunction "9_9") (pintype "passive"))
    )
    (net (code "192") (name "Net-(IC1-ST)") (class "Default")
      (node (ref "IC1") (pin "8") (pinfunction "ST_8") (pintype "bidirectional"))
      (node (ref "R5") (pin "1") (pinfunction "1_1") (pintype "passive"))
    )
    (net (code "193") (name "Net-(IC1-VIN2)") (class "Default")
      (node (ref "C5") (pin "2") (pinfunction "2_2") (pintype "passive"))
      (node (ref "IC1") (pin "6") (pinfunction "VIN2_6") (pintype "bidirectional"))
      (node (ref "Q6") (pin "2") (pinfunction "S_2") (pintype "bidirectional"))
    )
    (net (code "194") (name "Net-(IC2-EN)") (class "Default")
      (node (ref "IC2") (pin "5") (pinfunction "EN_5") (pintype "bidirectional"))
      (node (ref "Q1") (pin "3") (pinfunction "D_3") (pintype "bidirectional"))
      (node (ref "R3") (pin "1") (pinfunction "1_1") (pintype "passive"))
    )
    (net (code "195") (name "Net-(IC2-FB)") (class "Default")
      (node (ref "IC2") (pin "1") (pinfunction "FB_1") (pintype "bidirectional"))
      (node (ref "R2") (pin "1") (pinfunction "1_1") (pintype "passive"))
      (node (ref "R8") (pin "2") (pinfunction "2_2") (pintype "passive"))
    )
    (net (code "196") (name "Net-(IC2-SW)") (class "Default")
      (node (ref "IC2") (pin "4") (pinfunction "SW_4") (pintype "bidirectional"))
      (node (ref "L2") (pin "1") (pinfunction "1_1") (pintype "passive"))
    )
    (net (code "197") (name "Net-(IC9-LED0_{slash}_ANEN_SPEED)") (class "Default")
      (node (ref "IC9") (pin "23") (pinfunction "LED0_/_ANEN_SPEED_23") (pintype "bidirectional"))
      (node (ref "R35") (pin "1") (pinfunction "1_1") (pintype "passive"))
    )
    (net (code "198") (name "Net-(IC9-REXT)") (class "Default")
      (node (ref "IC9") (pin "9") (pinfunction "REXT_9") (pintype "bidirectional"))
      (node (ref "R38") (pin "1") (pinfunction "1_1") (pintype "passive"))
    )
    (net (code "199") (name "Net-(IC9-VDDA_3.3)") (class "Default")
      (node (ref "C81") (pin "2") (pinfunction "2_2") (pintype "passive"))
      (node (ref "C82") (pin "1") (pinfunction "1_1") (pintype "passive"))
      (node (ref "C85") (pin "1") (pinfunction "1_1") (pintype "passive"))
      (node (ref "IC9") (pin "2") (pinfunction "VDDA_3.3_2") (pintype "bidirectional"))
      (node (ref "L8") (pin "1") (pinfunction "1_1") (pintype "passive"))
    )
    (net (code "200") (name "Net-(IC9-VDD_1.2)") (class "Default")
      (node (ref "C83") (pin "2") (pinfunction "2_2") (pintype "passive"))
      (node (ref "C84") (pin "1") (pinfunction "1_1") (pintype "passive"))
      (node (ref "IC9") (pin "1") (pinfunction "VDD_1.2_1") (pintype "bidirectional"))
    )
    (net (code "201") (name "Net-(J1-CC1)") (class "Default")
      (node (ref "J1") (pin "A5") (pinfunction "CC1_A5") (pintype "bidirectional"))
      (node (ref "R6") (pin "1") (pinfunction "1_1") (pintype "passive"))
    )
    (net (code "202") (name "Net-(J1-CC2)") (class "Default")
      (node (ref "J1") (pin "B5") (pinfunction "CC2_B5") (pintype "bidirectional"))
      (node (ref "R7") (pin "1") (pinfunction "1_1") (pintype "passive"))
    )
    (net (code "203") (name "Net-(J7-SIGNAL)") (class "Default")
      (node (ref "C77") (pin "1") (pinfunction "1_1") (pintype "bidirectional"))
      (node (ref "J7") (pin "1") (pinfunction "SIGNAL_1") (pintype "bidirectional"))
      (node (ref "L7") (pin "2") (pinfunction "2_2") (pintype "passive"))
      (node (ref "U3") (pin "41") (pinfunction "ANT_41") (pintype "passive"))
    )
    (net (code "204") (name "Net-(U2-ILIM)") (class "Default")
      (node (ref "R10") (pin "1") (pinfunction "1_1") (pintype "passive"))
      (node (ref "U2") (pin "12") (pinfunction "ILIM_12") (pintype "input"))
    )
    (net (code "205") (name "Net-(U2-ISET)") (class "Default")
      (node (ref "R12") (pin "1") (pinfunction "1_1") (pintype "passive"))
      (node (ref "U2") (pin "16") (pinfunction "ISET_16") (pintype "bidirectional"))
    )
    (net (code "206") (name "Net-(U2-TMR)") (class "Default")
      (node (ref "R11") (pin "1") (pinfunction "1_1") (pintype "passive"))
      (node (ref "U2") (pin "14") (pinfunction "TMR_14") (pintype "input"))
    )
    (net (code "207") (name "Net-(U2-TS)") (class "Default")
      (node (ref "R9") (pin "1") (pinfunction "1_1") (pintype "passive"))
      (node (ref "U2") (pin "1") (pinfunction "TS_1") (pintype "input"))
    )
    (net (code "208") (name "Net-(U2-~{CHG})") (class "Default")
      (node (ref "R1") (pin "1") (pinfunction "1_1") (pintype "passive"))
      (node (ref "U2") (pin "9") (pinfunction "~{CHG}_9") (pintype "output"))
    )
    (net (code "209") (name "Net-(U2-~{PGOOD})") (class "Default")
      (node (ref "R4") (pin "1") (pinfunction "1_1") (pintype "passive"))
      (node (ref "U2") (pin "7") (pinfunction "~{PGOOD}_7") (pintype "output"))
    )
    (net (code "210") (name "Net-(U3-SR_VLX)") (class "Default")
      (node (ref "L9") (pin "1") (pinfunction "1_1") (pintype "passive"))
      (node (ref "U3") (pin "34") (pinfunction "SR_VLX_34") (pintype "output"))
    )
    (net (code "211") (name "Net-(U3-VIN_LDO)") (class "Default")
      (node (ref "C74") (pin "1") (pinfunction "1_1") (pintype "passive"))
      (node (ref "C91") (pin "2") (pinfunction "2_2") (pintype "passive"))
      (node (ref "L9") (pin "2") (pinfunction "2_2") (pintype "passive"))
      (node (ref "U3") (pin "31") (pinfunction "VIN_LDO_31") (pintype "power_in"))
    )
    (net (code "212") (name "RAW") (class "Default")
      (node (ref "C1") (pin "2") (pinfunction "2_2") (pintype "passive"))
      (node (ref "C4") (pin "2") (pinfunction "2_2") (pintype "passive"))
      (node (ref "C6") (pin "1") (pinfunction "1_1") (pintype "passive"))
      (node (ref "D1") (pin "4") (pinfunction "ANODE_4") (pintype "passive"))
      (node (ref "D5") (pin "1") (pinfunction "1_1") (pintype "bidirectional"))
      (node (ref "IC1") (pin "2") (pinfunction "VOUT_1_2") (pintype "bidirectional"))
      (node (ref "IC1") (pin "7") (pinfunction "VOUT_2_7") (pintype "bidirectional"))
      (node (ref "IC2") (pin "3") (pinfunction "VIN_3") (pintype "bidirectional"))
      (node (ref "J3") (pin "2") (pinfunction "2_2") (pintype "passive"))
      (node (ref "Q1") (pin "1") (pinfunction "G_1") (pintype "bidirectional"))
      (node (ref "Q2") (pin "1") (pinfunction "G_1") (pintype "bidirectional"))
      (node (ref "Q3") (pin "1") (pinfunction "G_1") (pintype "bidirectional"))
      (node (ref "R22") (pin "2") (pinfunction "2_2") (pintype "passive"))
      (node (ref "R23") (pin "2") (pinfunction "2_2") (pintype "passive"))
      (node (ref "R3") (pin "2") (pinfunction "2_2") (pintype "passive"))
      (node (ref "U1") (pin "3") (pinfunction "EN_3") (pintype "bidirectional"))
      (node (ref "U1") (pin "4") (pinfunction "VIN_4") (pintype "bidirectional"))
    )
    (net (code "213") (name "VBUS") (class "Default")
      (node (ref "C88") (pin "1") (pinfunction "1_1") (pintype "passive"))
      (node (ref "C9") (pin "2") (pinfunction "2_2") (pintype "passive"))
      (node (ref "C95") (pin "2") (pinfunction "2_2") (pintype "passive"))
      (node (ref "FL1") (pin "1") (pinfunction "VBUS_1") (pintype "bidirectional"))
      (node (ref "IC8") (pin "N6") (pinfunction "USB_OTG1_VBUS_N6") (pintype "bidirectional"))
      (node (ref "L1") (pin "2") (pinfunction "2_2") (pintype "passive"))
      (node (ref "U2") (pin "13") (pinfunction "IN_13") (pintype "input"))
    )
    (net (code "214") (name "VCC") (class "Default")
      (node (ref "C108") (pin "2") (pinfunction "2_2") (pintype "passive"))
      (node (ref "C109") (pin "1") (pinfunction "1_1") (pintype "passive"))
      (node (ref "C11") (pin "2") (pinfunction "2_2") (pintype "passive"))
      (node (ref "C12") (pin "1") (pinfunction "1_1") (pintype "passive"))
      (node (ref "C13") (pin "1") (pinfunction "1_1") (pintype "passive"))
      (node (ref "C14") (pin "1") (pinfunction "1_1") (pintype "passive"))
      (node (ref "C15") (pin "1") (pinfunction "1_1") (pintype "passive"))
      (node (ref "C16") (pin "1") (pinfunction "1_1") (pintype "passive"))
      (node (ref "C17") (pin "2") (pinfunction "2_2") (pintype "passive"))
      (node (ref "C18") (pin "2") (pinfunction "2_2") (pintype "passive"))
      (node (ref "C19") (pin "1") (pinfunction "1_1") (pintype "passive"))
      (node (ref "C20") (pin "1") (pinfunction "1_1") (pintype "passive"))
      (node (ref "C21") (pin "2") (pinfunction "2_2") (pintype "passive"))
      (node (ref "C22") (pin "1") (pinfunction "1_1") (pintype "passive"))
      (node (ref "C23") (pin "2") (pinfunction "2_2") (pintype "passive"))
      (node (ref "C24") (pin "1") (pinfunction "1_1") (pintype "passive"))
      (node (ref "C25") (pin "2") (pinfunction "2_2") (pintype "passive"))
      (node (ref "C26") (pin "1") (pinfunction "1_1") (pintype "passive"))
      (node (ref "C27") (pin "2") (pinfunction "2_2") (pintype "passive"))
      (node (ref "C28") (pin "1") (pinfunction "1_1") (pintype "passive"))
      (node (ref "C29") (pin "1") (pinfunction "1_1") (pintype "passive"))
      (node (ref "C30") (pin "1") (pinfunction "1_1") (pintype "passive"))
      (node (ref "C31") (pin "2") (pinfunction "2_2") (pintype "passive"))
      (node (ref "C32") (pin "1") (pinfunction "1_1") (pintype "passive"))
      (node (ref "C33") (pin "2") (pinfunction "2_2") (pintype "passive"))
      (node (ref "C35") (pin "2") (pinfunction "2_2") (pintype "passive"))
      (node (ref "C36") (pin "1") (pinfunction "1_1") (pintype "passive"))
      (node (ref "C37") (pin "1") (pinfunction "1_1") (pintype "passive"))
      (node (ref "C39") (pin "2") (pinfunction "2_2") (pintype "passive"))
      (node (ref "C40") (pin "2") (pinfunction "2_2") (pintype "passive"))
      (node (ref "C41") (pin "2") (pinfunction "2_2") (pintype "passive"))
      (node (ref "C42") (pin "2") (pinfunction "2_2") (pintype "passive"))
      (node (ref "C43") (pin "1") (pinfunction "1_1") (pintype "passive"))
      (node (ref "C44") (pin "2") (pinfunction "2_2") (pintype "passive"))
      (node (ref "C50") (pin "1") (pinfunction "1_1") (pintype "passive"))
      (node (ref "C53") (pin "1") (pinfunction "1_1") (pintype "passive"))
      (node (ref "C54") (pin "1") (pinfunction "1_1") (pintype "passive"))
      (node (ref "C55") (pin "1") (pinfunction "1_1") (pintype "passive"))
      (node (ref "C56") (pin "1") (pinfunction "1_1") (pintype "passive"))
      (node (ref "C57") (pin "2") (pinfunction "2_2") (pintype "passive"))
      (node (ref "C58") (pin "2") (pinfunction "2_2") (pintype "passive"))
      (node (ref "C64") (pin "1") (pinfunction "1_1") (pintype "passive"))
      (node (ref "C66") (pin "2") (pinfunction "2_2") (pintype "passive"))
      (node (ref "C67") (pin "1") (pinfunction "1_1") (pintype "passive"))
      (node (ref "C68") (pin "2") (pinfunction "2_2") (pintype "passive"))
      (node (ref "C7") (pin "1") (pinfunction "1_1") (pintype "passive"))
      (node (ref "C75") (pin "1") (pinfunction "1_1") (pintype "passive"))
      (node (ref "C76") (pin "1") (pinfunction "1_1") (pintype "passive"))
      (node (ref "C86") (pin "2") (pinfunction "2_2") (pintype "passive"))
      (node (ref "C89") (pin "1") (pinfunction "1_1") (pintype "passive"))
      (node (ref "C90") (pin "2") (pinfunction "2_2") (pintype "passive"))
      (node (ref "C92") (pin "2") (pinfunction "2_2") (pintype "passive"))
      (node (ref "C93") (pin "2") (pinfunction "2_2") (pintype "passive"))
      (node (ref "C96") (pin "1") (pinfunction "1_1") (pintype "passive"))
      (node (ref "C99") (pin "2") (pinfunction "2_2") (pintype "passive"))
      (node (ref "D10") (pin "1") (pinfunction "1_1") (pintype "bidirectional"))
      (node (ref "D3") (pin "4") (pinfunction "ANODE_4") (pintype "passive"))
      (node (ref "D4") (pin "1") (pinfunction "1_1") (pintype "bidirectional"))
      (node (ref "D6") (pin "1") (pinfunction "1_1") (pintype "bidirectional"))
      (node (ref "IC2") (pin "6") (pinfunction "OUT_6") (pintype "bidirectional"))
      (node (ref "IC3") (pin "A7") (pinfunction "VDDQ_1_A7") (pintype "bidirectional"))
      (node (ref "IC3") (pin "A9") (pinfunction "VDD_1_A9") (pintype "bidirectional"))
      (node (ref "IC3") (pin "B3") (pinfunction "VDDQ_2_B3") (pintype "bidirectional"))
      (node (ref "IC3") (pin "C7") (pinfunction "VDDQ_3_C7") (pintype "bidirectional"))
      (node (ref "IC3") (pin "D3") (pinfunction "VDDQ_4_D3") (pintype "bidirectional"))
      (node (ref "IC3") (pin "E7") (pinfunction "VDD_2_E7") (pintype "bidirectional"))
      (node (ref "IC3") (pin "J9") (pinfunction "VDD_3_J9") (pintype "bidirectional"))
      (node (ref "IC4") (pin "8") (pinfunction "VCC_8") (pintype "bidirectional"))
      (node (ref "IC5") (pin "8") (pinfunction "VCC_8") (pintype "bidirectional"))
      (node (ref "IC6") (pin "8") (pinfunction "VCC_8") (pintype "bidirectional"))
      (node (ref "IC7") (pin "6") (pinfunction "VDD_6") (pintype "bidirectional"))
      (node (ref "IC8") (pin "E6") (pinfunction "NVCC_EMC_1_E6") (pintype "bidirectional"))
      (node (ref "IC8") (pin "E9") (pinfunction "NVCC_GPIO_1_E9") (pintype "bidirectional"))
      (node (ref "IC8") (pin "F10") (pinfunction "NVCC_GPIO_2_F10") (pintype "bidirectional"))
      (node (ref "IC8") (pin "F5") (pinfunction "NVCC_EMC_2_F5") (pintype "bidirectional"))
      (node (ref "IC8") (pin "J10") (pinfunction "NVCC_GPIO_3_J10") (pintype "bidirectional"))
      (node (ref "IC8") (pin "J6") (pinfunction "NVCC_SD0_J6") (pintype "bidirectional"))
      (node (ref "IC8") (pin "K4") (pinfunction "DCDC_IN_Q_K4") (pintype "bidirectional"))
      (node (ref "IC8") (pin "K5") (pinfunction "NVCC_SD1_K5") (pintype "bidirectional"))
      (node (ref "IC8") (pin "L1") (pinfunction "DCDC_IN_1_L1") (pintype "bidirectional"))
      (node (ref "IC8") (pin "L2") (pinfunction "DCDC_IN_2_L2") (pintype "bidirectional"))
      (node (ref "IC8") (pin "P12") (pinfunction "VDD_HIGH_IN_P12") (pintype "bidirectional"))
      (node (ref "IC9") (pin "14") (pinfunction "VDDIO_14") (pintype "bidirectional"))
      (node (ref "J2") (pin "1") (pinfunction "1_1") (pintype "passive"))
      (node (ref "J4") (pin "10") (pinfunction "10_10") (pintype "bidirectional"))
      (node (ref "J4") (pin "2") (pinfunction "2_2") (pintype "bidirectional"))
      (node (ref "J4") (pin "20") (pinfunction "20_20") (pintype "bidirectional"))
      (node (ref "J4") (pin "30") (pinfunction "30_30") (pintype "bidirectional"))
      (node (ref "J4") (pin "36") (pinfunction "36_36") (pintype "bidirectional"))
      (node (ref "J5") (pin "P$4") (pinfunction "VDD_P$4") (pintype "power_in"))
      (node (ref "J8") (pin "1") (pinfunction "1_1") (pintype "passive"))
      (node (ref "L2") (pin "2") (pinfunction "2_2") (pintype "passive"))
      (node (ref "L4") (pin "2") (pinfunction "2_2") (pintype "passive"))
      (node (ref "L6") (pin "2") (pinfunction "2_2") (pintype "passive"))
      (node (ref "L8") (pin "2") (pinfunction "2_2") (pintype "passive"))
      (node (ref "Q4") (pin "1") (pinfunction "G_1") (pintype "bidirectional"))
      (node (ref "Q5") (pin "1") (pinfunction "G_1") (pintype "bidirectional"))
      (node (ref "R13") (pin "1") (pinfunction "1_1") (pintype "passive"))
      (node (ref "R14") (pin "1") (pinfunction "1_1") (pintype "passive"))
      (node (ref "R15") (pin "2") (pinfunction "2_2") (pintype "passive"))
      (node (ref "R16") (pin "2") (pinfunction "2_2") (pintype "passive"))
      (node (ref "R17") (pin "2") (pinfunction "2_2") (pintype "passive"))
      (node (ref "R18") (pin "1") (pinfunction "1_1") (pintype "passive"))
      (node (ref "R2") (pin "2") (pinfunction "2_2") (pintype "passive"))
      (node (ref "R24") (pin "2") (pinfunction "2_2") (pintype "passive"))
      (node (ref "R25") (pin "2") (pinfunction "2_2") (pintype "passive"))
      (node (ref "R26") (pin "2") (pinfunction "2_2") (pintype "passive"))
      (node (ref "R28") (pin "2") (pinfunction "2_2") (pintype "passive"))
      (node (ref "R29") (pin "2") (pinfunction "2_2") (pintype "passive"))
      (node (ref "R30") (pin "2") (pinfunction "2_2") (pintype "passive"))
      (node (ref "R31") (pin "2") (pinfunction "2_2") (pintype "passive"))
      (node (ref "R32") (pin "2") (pinfunction "2_2") (pintype "passive"))
      (node (ref "R33") (pin "1") (pinfunction "1_1") (pintype "passive"))
      (node (ref "R34") (pin "2") (pinfunction "2_2") (pintype "passive"))
      (node (ref "R36") (pin "2") (pinfunction "2_2") (pintype "passive"))
      (node (ref "R39") (pin "2") (pinfunction "2_2") (pintype "passive"))
      (node (ref "RN1") (pin "1") (pinfunction "1_1") (pintype "bidirectional"))
      (node (ref "RN1") (pin "2") (pinfunction "2_2") (pintype "bidirectional"))
      (node (ref "RN1") (pin "3") (pinfunction "3_3") (pintype "bidirectional"))
      (node (ref "RN1") (pin "4") (pinfunction "4_4") (pintype "bidirectional"))
      (node (ref "RN1") (pin "5") (pinfunction "5_5") (pintype "bidirectional"))
      (node (ref "RN1") (pin "6") (pinfunction "6_6") (pintype "bidirectional"))
      (node (ref "RN1") (pin "7") (pinfunction "7_7") (pintype "bidirectional"))
      (node (ref "RN1") (pin "8") (pinfunction "8_8") (pintype "bidirectional"))
      (node (ref "RN2") (pin "1") (pinfunction "1_1") (pintype "bidirectional"))
      (node (ref "RN2") (pin "2") (pinfunction "2_2") (pintype "bidirectional"))
      (node (ref "RN2") (pin "3") (pinfunction "3_3") (pintype "bidirectional"))
      (node (ref "RN2") (pin "4") (pinfunction "4_4") (pintype "bidirectional"))
      (node (ref "RN2") (pin "5") (pinfunction "5_5") (pintype "bidirectional"))
      (node (ref "RN2") (pin "6") (pinfunction "6_6") (pintype "bidirectional"))
      (node (ref "RN2") (pin "7") (pinfunction "7_7") (pintype "bidirectional"))
      (node (ref "RN2") (pin "8") (pinfunction "8_8") (pintype "bidirectional"))
      (node (ref "U3") (pin "30") (pinfunction "VBAT_30") (pintype "power_in"))
      (node (ref "U3") (pin "36") (pinfunction "VIO_36") (pintype "power_in"))
    )
    (net (code "215") (name "VIN") (class "Default")
      (node (ref "D7") (pin "1") (pinfunction "1_1") (pintype "bidirectional"))
      (node (ref "J6") (pin "2") (pinfunction "2_2") (pintype "passive"))
      (node (ref "Q6") (pin "3") (pinfunction "D_3") (pintype "bidirectional"))
    )
    (net (code "216") (name "V_BATT") (class "Default")
      (node (ref "C10") (pin "2") (pinfunction "2_2") (pintype "passive"))
      (node (ref "C3") (pin "2") (pinfunction "2_2") (pintype "passive"))
      (node (ref "IC1") (pin "3") (pinfunction "VIN1_3") (pintype "bidirectional"))
      (node (ref "U2") (pin "10") (pinfunction "OUT_10_10") (pintype "output"))
      (node (ref "U2") (pin "11") (pinfunction "OUT_11_11") (pintype "output"))
      (node (ref "U2") (pin "5") (pinfunction "EN2_5") (pintype "input"))
    )
    (net (code "217") (name "unconnected-(ANT1-NC-Pad2)") (class "Default")
      (node (ref "ANT1") (pin "2") (pinfunction "NC_2") (pintype "no_connect"))
    )
    (net (code "218") (name "unconnected-(FL1-Pad9)") (class "Default")
      (node (ref "FL1") (pin "9") (pinfunction "9_9") (pintype "bidirectional"))
    )
    (net (code "219") (name "unconnected-(FL1-Pad10)") (class "Default")
      (node (ref "FL1") (pin "10") (pinfunction "10_10") (pintype "bidirectional"))
    )
    (net (code "220") (name "unconnected-(FL1-Pad11)") (class "Default")
      (node (ref "FL1") (pin "11") (pinfunction "11_11") (pintype "bidirectional"))
    )
    (net (code "221") (name "unconnected-(FL1-Pad12)") (class "Default")
      (node (ref "FL1") (pin "12") (pinfunction "12_12") (pintype "bidirectional"))
    )
    (net (code "222") (name "unconnected-(H1-MOUNT-PadB2,8)") (class "Default")
      (node (ref "H1") (pin "B2,8") (pinfunction "MOUNT_B2,8") (pintype "passive"))
    )
    (net (code "223") (name "unconnected-(H2-MOUNT-PadB2,8)") (class "Default")
      (node (ref "H2") (pin "B2,8") (pinfunction "MOUNT_B2,8") (pintype "passive"))
    )
    (net (code "224") (name "unconnected-(IC3-NC-PadE2)") (class "Default")
      (node (ref "IC3") (pin "E2") (pinfunction "NC_E2") (pintype "no_connect"))
    )
    (net (code "225") (name "unconnected-(IC4-NC_1-Pad1)") (class "Default")
      (node (ref "IC4") (pin "1") (pinfunction "NC_1_1") (pintype "bidirectional"))
    )
    (net (code "226") (name "unconnected-(IC4-NC_2-Pad2)") (class "Default")
      (node (ref "IC4") (pin "2") (pinfunction "NC_2_2") (pintype "bidirectional"))
    )
    (net (code "227") (name "unconnected-(IC4-NC_3-Pad3)") (class "Default")
      (node (ref "IC4") (pin "3") (pinfunction "NC_3_3") (pintype "bidirectional"))
    )
    (net (code "228") (name "unconnected-(IC4-NC_4-Pad7)") (class "Default")
      (node (ref "IC4") (pin "7") (pinfunction "NC_4_7") (pintype "bidirectional"))
    )
    (net (code "229") (name "unconnected-(IC7-NC-Pad2)") (class "Default")
      (node (ref "IC7") (pin "2") (pinfunction "NC_2") (pintype "no_connect"))
    )
    (net (code "230") (name "unconnected-(IC8-CCM_CLK1_N-PadP13)") (class "Default")
      (node (ref "IC8") (pin "P13") (pinfunction "CCM_CLK1_N_P13") (pintype "bidirectional"))
    )
    (net (code "231") (name "unconnected-(IC8-CCM_CLK1_P-PadN13)") (class "Default")
      (node (ref "IC8") (pin "N13") (pinfunction "CCM_CLK1_P_N13") (pintype "bidirectional"))
    )
    (net (code "232") (name "unconnected-(IC8-GPANAIO-PadN10)") (class "Default")
      (node (ref "IC8") (pin "N10") (pinfunction "GPANAIO_N10") (pintype "bidirectional"))
    )
    (net (code "233") (name "unconnected-(IC8-USB_OTG1_CHD_B-PadN12)") (class "Default")
      (node (ref "IC8") (pin "N12") (pinfunction "USB_OTG1_CHD_B_N12") (pintype "bidirectional"))
    )
    (net (code "234") (name "unconnected-(IC8-USB_OTG2_DN-PadN7)") (class "Default")
      (node (ref "IC8") (pin "N7") (pinfunction "USB_OTG2_DN_N7") (pintype "bidirectional"))
    )
    (net (code "235") (name "unconnected-(IC8-USB_OTG2_DP-PadP7)") (class "Default")
      (node (ref "IC8") (pin "P7") (pinfunction "USB_OTG2_DP_P7") (pintype "bidirectional"))
    )
    (net (code "236") (name "unconnected-(IC8-USB_OTG2_VBUS-PadP6)") (class "Default")
      (node (ref "IC8") (pin "P6") (pinfunction "USB_OTG2_VBUS_P6") (pintype "bidirectional"))
    )
    (net (code "237") (name "unconnected-(IC9-REF_CLK-Pad16)") (class "Default")
      (node (ref "IC9") (pin "16") (pinfunction "REF_CLK_16") (pintype "bidirectional"))
    )
    (net (code "238") (name "unconnected-(IC9-XO-Pad7)") (class "Default")
      (node (ref "IC9") (pin "7") (pinfunction "XO_7") (pintype "bidirectional"))
    )
    (net (code "239") (name "unconnected-(J1-SBU1-PadA8)") (class "Default")
      (node (ref "J1") (pin "A8") (pinfunction "SBU1_A8") (pintype "bidirectional"))
    )
    (net (code "240") (name "unconnected-(J1-SBU2-PadB8)") (class "Default")
      (node (ref "J1") (pin "B8") (pinfunction "SBU2_B8") (pintype "bidirectional"))
    )
    (net (code "241") (name "unconnected-(J4-Pad1)") (class "Default")
      (node (ref "J4") (pin "1") (pinfunction "1_1") (pintype "bidirectional"))
    )
    (net (code "242") (name "unconnected-(J4-Pad3)") (class "Default")
      (node (ref "J4") (pin "3") (pinfunction "3_3") (pintype "bidirectional"))
    )
    (net (code "243") (name "unconnected-(J4-Pad6)") (class "Default")
      (node (ref "J4") (pin "6") (pinfunction "6_6") (pintype "bidirectional"))
    )
    (net (code "244") (name "unconnected-(J4-Pad7)") (class "Default")
      (node (ref "J4") (pin "7") (pinfunction "7_7") (pintype "bidirectional"))
    )
    (net (code "245") (name "unconnected-(J4-Pad8)") (class "Default")
      (node (ref "J4") (pin "8") (pinfunction "8_8") (pintype "bidirectional"))
    )
    (net (code "246") (name "unconnected-(J4-Pad9)") (class "Default")
      (node (ref "J4") (pin "9") (pinfunction "9_9") (pintype "bidirectional"))
    )
    (net (code "247") (name "unconnected-(J8-Pad7)") (class "Default")
      (node (ref "J8") (pin "7") (pinfunction "7_7") (pintype "passive"))
    )
    (net (code "248") (name "unconnected-(RN1-Pad15)") (class "Default")
      (node (ref "RN1") (pin "15") (pinfunction "15_15") (pintype "bidirectional"))
    )
    (net (code "249") (name "unconnected-(RN1-Pad16)") (class "Default")
      (node (ref "RN1") (pin "16") (pinfunction "16_16") (pintype "bidirectional"))
    )
    (net (code "250") (name "unconnected-(RN2-Pad9)") (class "Default")
      (node (ref "RN2") (pin "9") (pinfunction "9_9") (pintype "bidirectional"))
    )
    (net (code "251") (name "unconnected-(RN2-Pad10)") (class "Default")
      (node (ref "RN2") (pin "10") (pinfunction "10_10") (pintype "bidirectional"))
    )
    (net (code "252") (name "unconnected-(RN2-Pad11)") (class "Default")
      (node (ref "RN2") (pin "11") (pinfunction "11_11") (pintype "bidirectional"))
    )
    (net (code "253") (name "unconnected-(U3-BT_GPIO_3-Pad6)") (class "Default")
      (node (ref "U3") (pin "6") (pinfunction "BT_GPIO_3_6") (pintype "bidirectional"))
    )
    (net (code "254") (name "unconnected-(U3-BT_GPIO_4-Pad7)") (class "Default")
      (node (ref "U3") (pin "7") (pinfunction "BT_GPIO_4_7") (pintype "bidirectional"))
    )
    (net (code "255") (name "unconnected-(U3-BT_GPIO_5-Pad13)") (class "Default")
      (node (ref "U3") (pin "13") (pinfunction "BT_GPIO_5_13") (pintype "bidirectional"))
    )
    (net (code "256") (name "unconnected-(U3-BT_I2S_DO-Pad16)") (class "Default")
      (node (ref "U3") (pin "16") (pinfunction "BT_I2S_DO_16") (pintype "bidirectional"))
    )
    (net (code "257") (name "unconnected-(U3-BT_PCM_CLK-Pad11)") (class "Default")
      (node (ref "U3") (pin "11") (pinfunction "BT_PCM_CLK_11") (pintype "bidirectional"))
    )
    (net (code "258") (name "unconnected-(U3-BT_PCM_IN-Pad9)") (class "Default")
      (node (ref "U3") (pin "9") (pinfunction "BT_PCM_IN_9") (pintype "input"))
    )
    (net (code "259") (name "unconnected-(U3-BT_PCM_OUT-Pad10)") (class "Default")
      (node (ref "U3") (pin "10") (pinfunction "BT_PCM_OUT_10") (pintype "output"))
    )
    (net (code "260") (name "unconnected-(U3-BT_PCM_SYNC-Pad8)") (class "Default")
      (node (ref "U3") (pin "8") (pinfunction "BT_PCM_SYNC_8") (pintype "bidirectional"))
    )
    (net (code "261") (name "unconnected-(U3-WL_GPIO_1-Pad18)") (class "Default")
      (node (ref "U3") (pin "18") (pinfunction "WL_GPIO_1_18") (pintype "bidirectional"))
    )
    (net (code "262") (name "unconnected-(U3-WL_GPIO_2-Pad17)") (class "Default")
      (node (ref "U3") (pin "17") (pinfunction "WL_GPIO_2_17") (pintype "bidirectional"))
    )
    (net (code "263") (name "unconnected-(U3-WL_GPIO_4-Pad15)") (class "Default")
      (node (ref "U3") (pin "15") (pinfunction "WL_GPIO_4_15") (pintype "bidirectional"))
    )
    (net (code "264") (name "unconnected-(U3-~{BT_UART_RTS_N}-Pad5)") (class "Default")
      (node (ref "U3") (pin "5") (pinfunction "~{BT_UART_RTS_N}_5") (pintype "output"))
    )
  )
)
